# Open-Source_Control_V2_R3.net
KiCad netlist of a schematic drawn in EAGLE
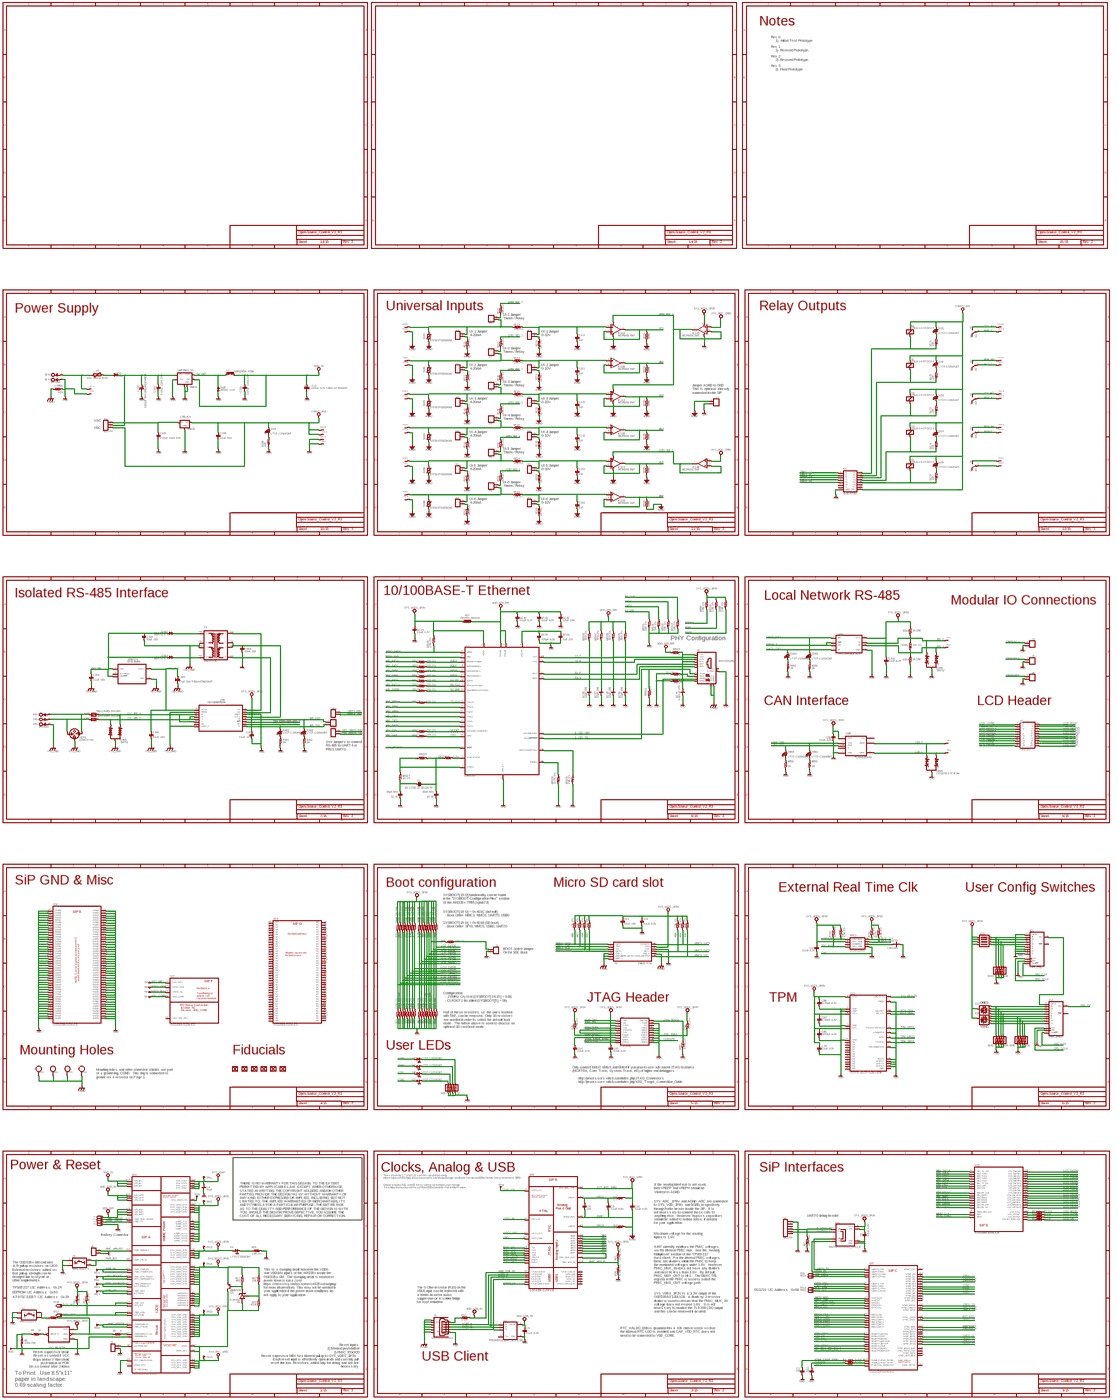
[diagram p0: schematic, sheet 1, overview]
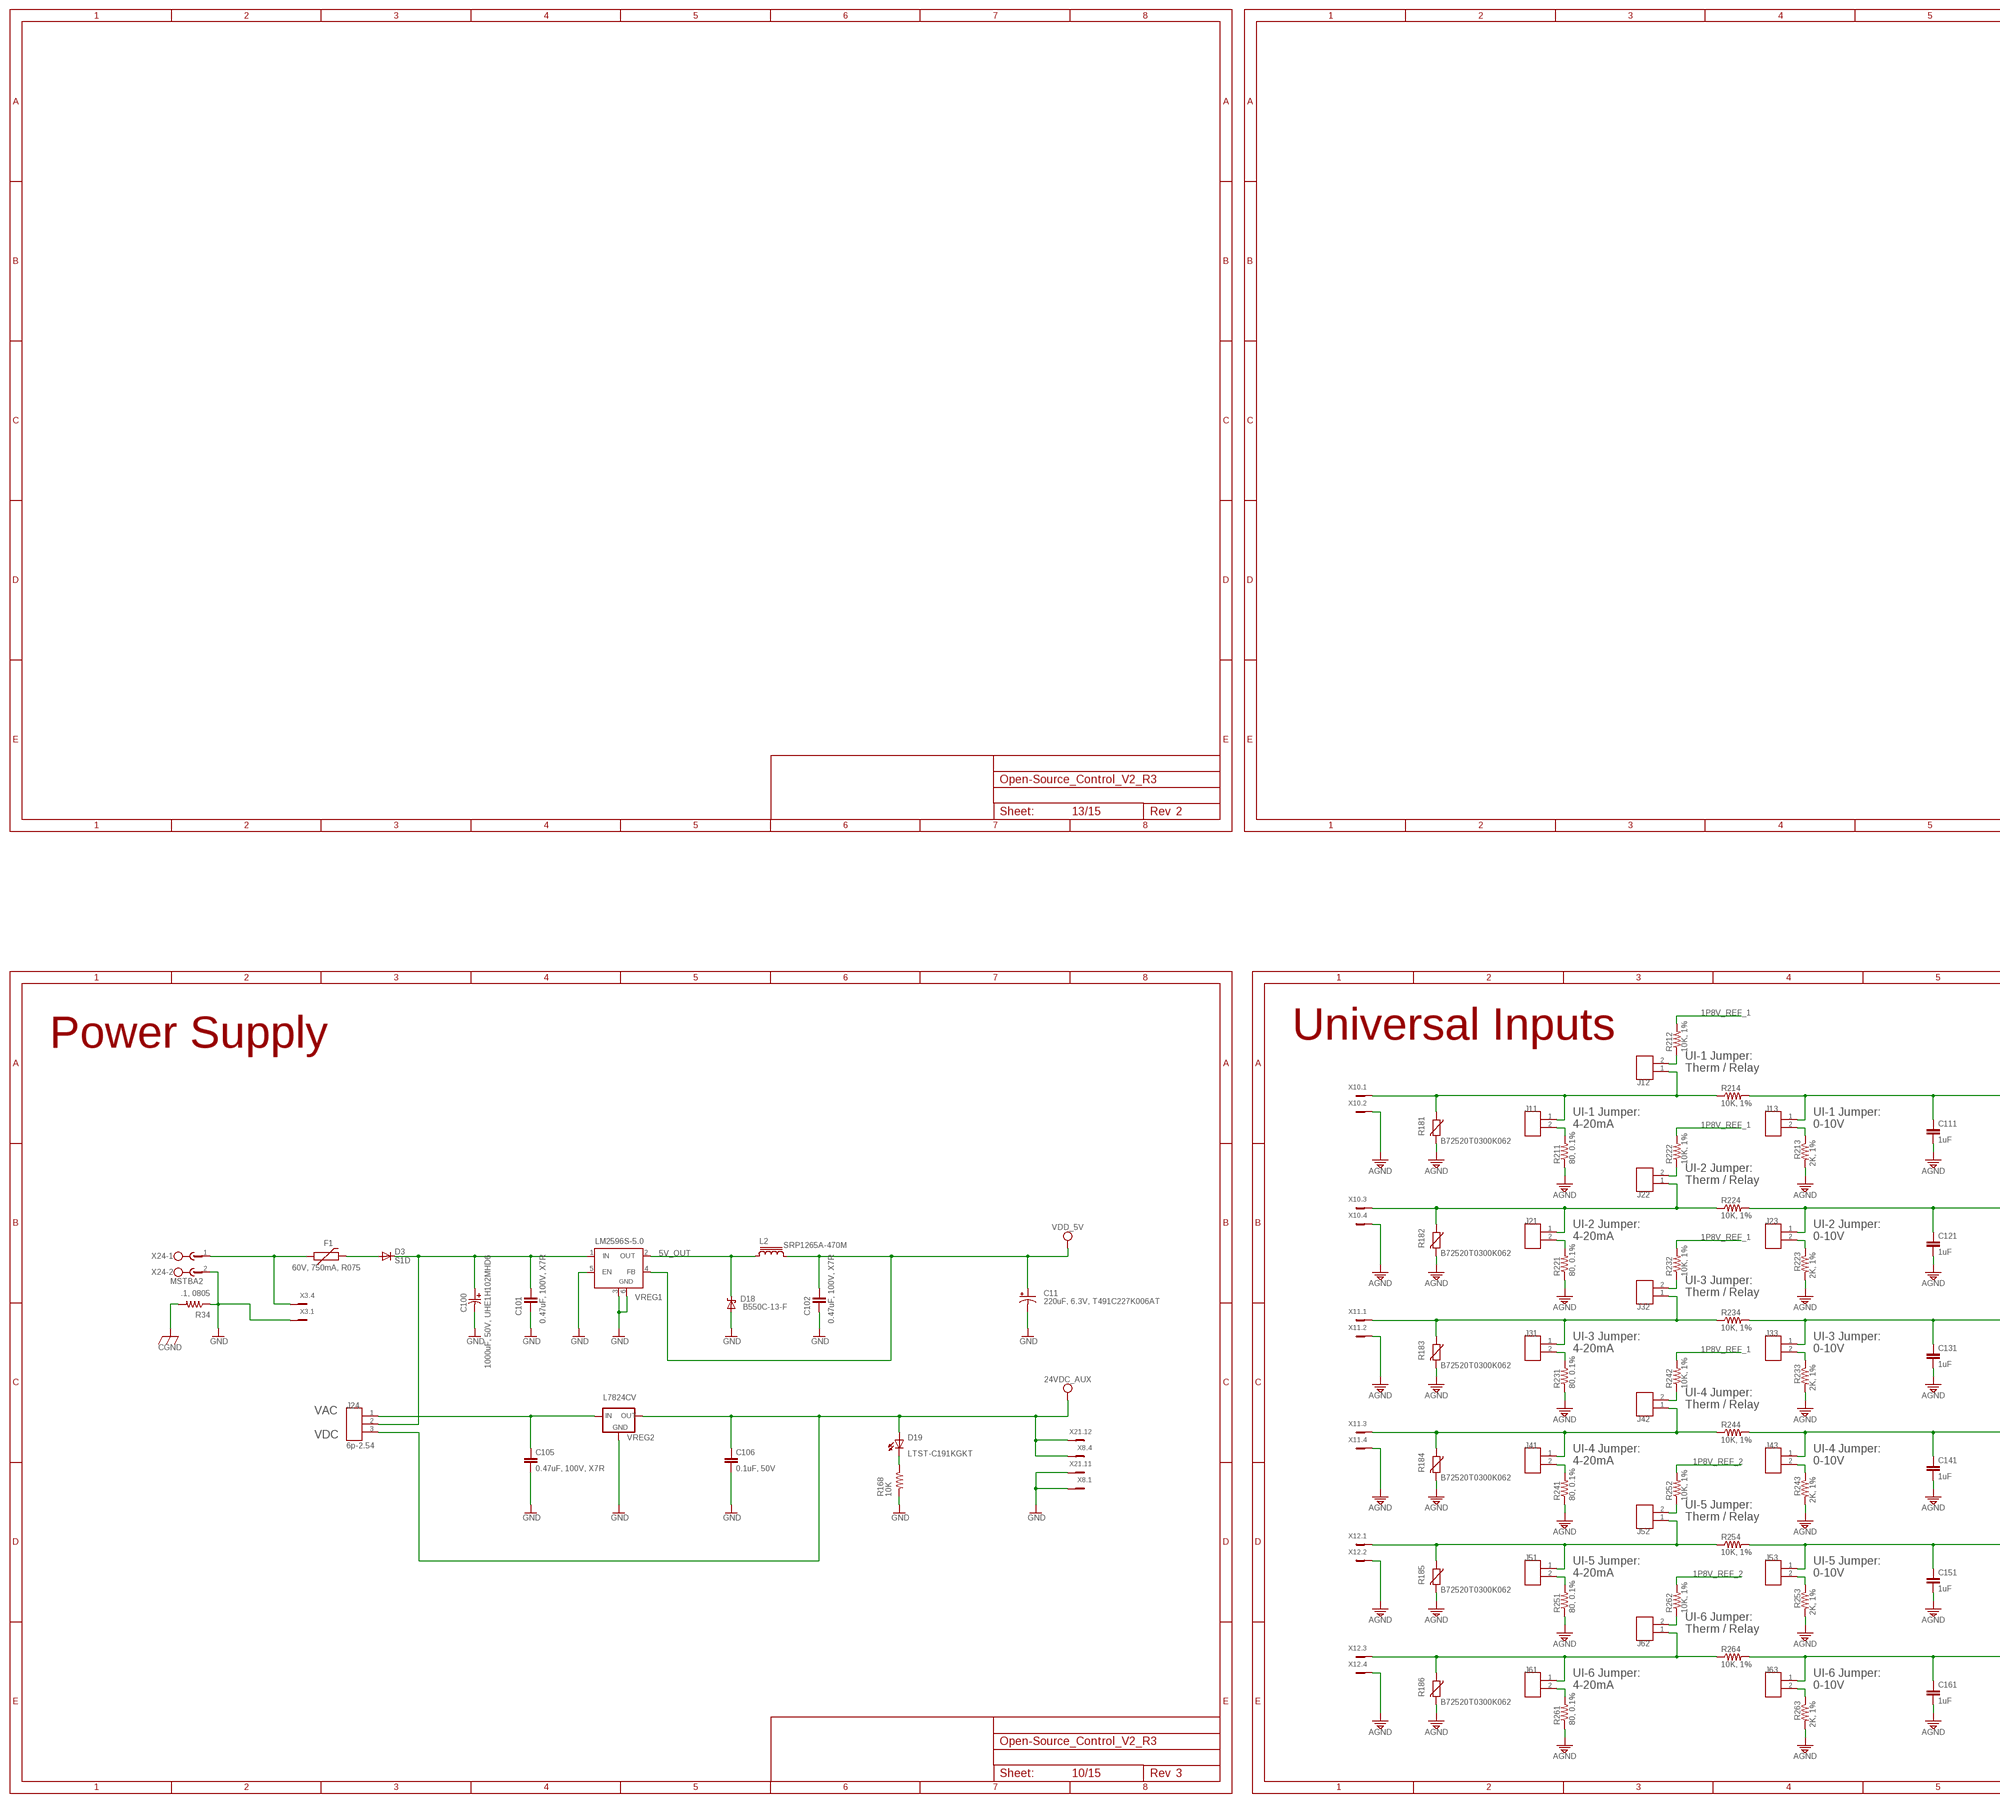
[diagram p1: schematic, sheet 1, part 1 of 6]
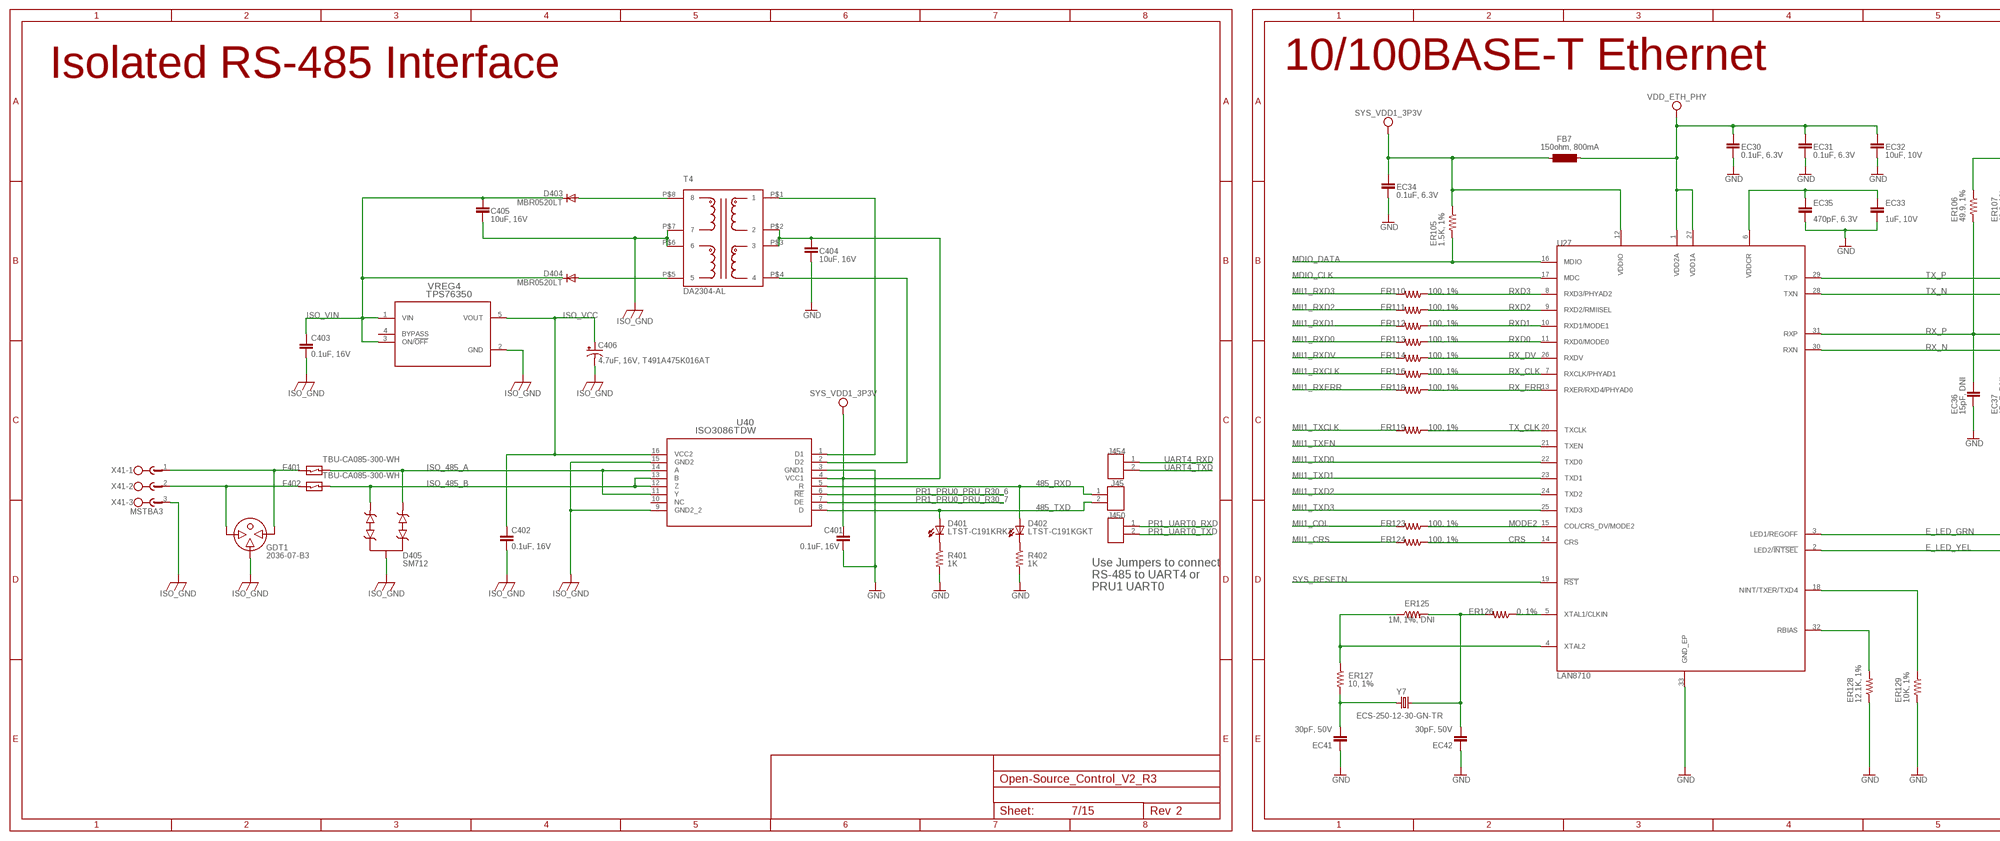
[diagram p2: schematic, sheet 1, part 2 of 6]
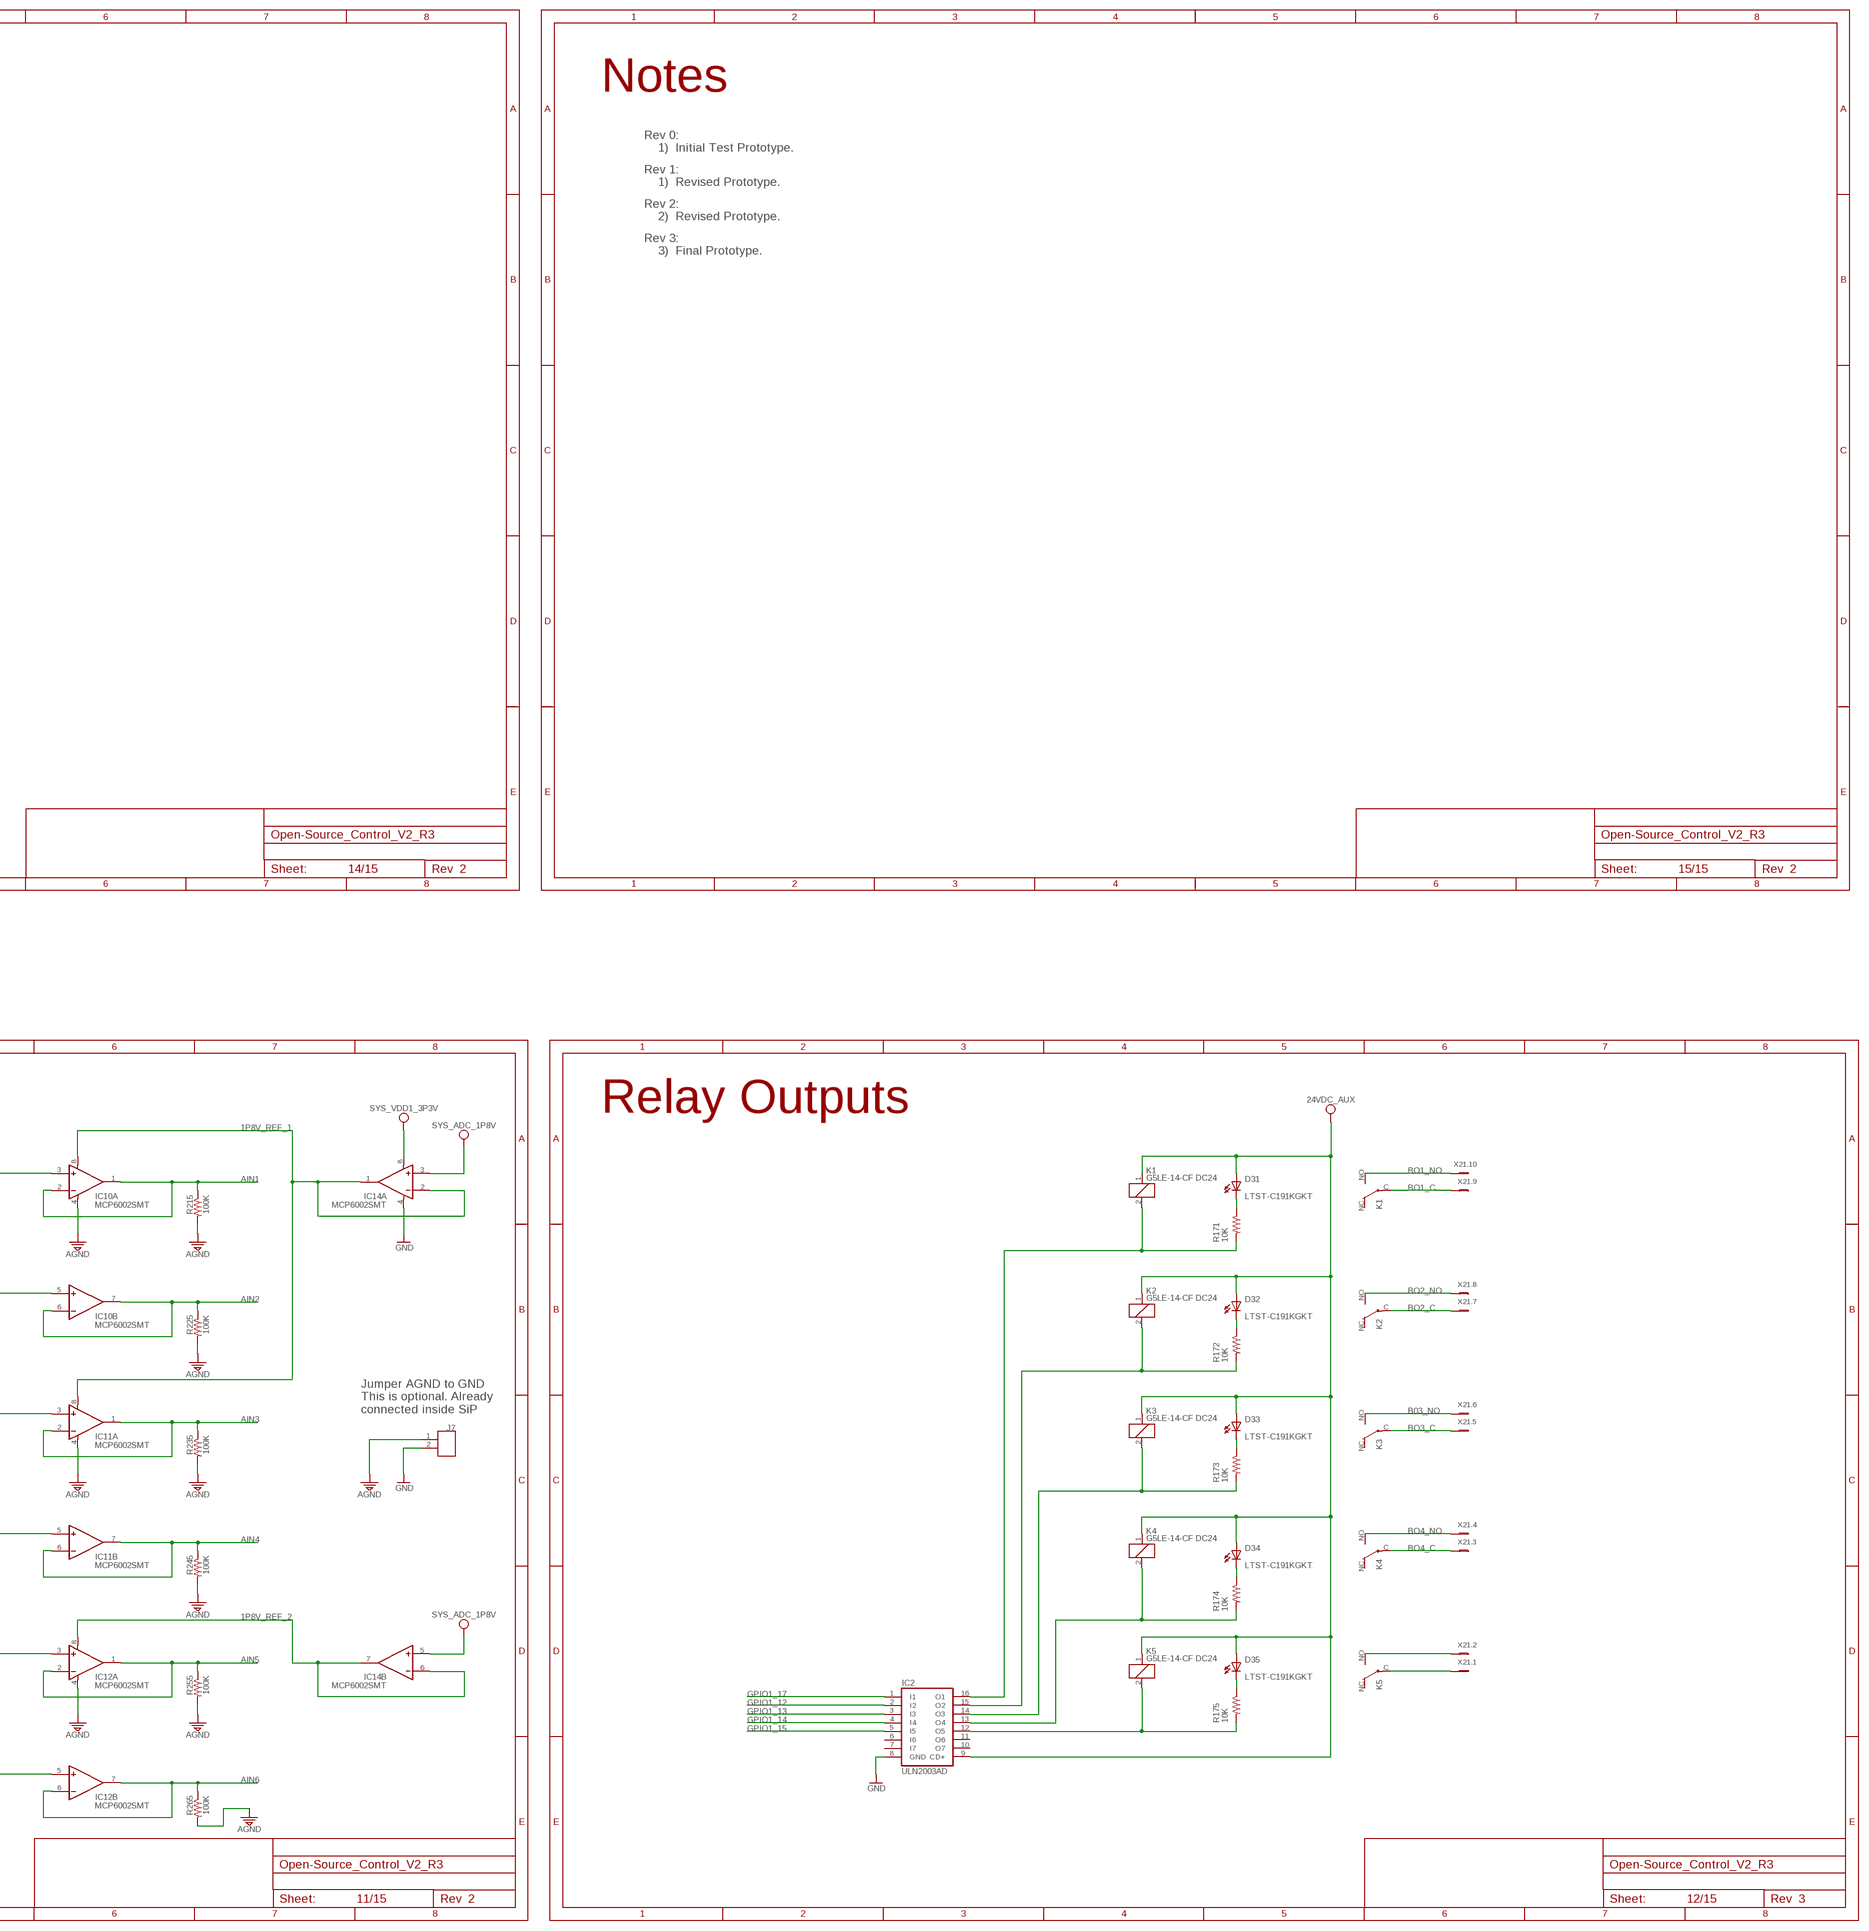
[diagram p3: schematic, sheet 1, part 3 of 6]
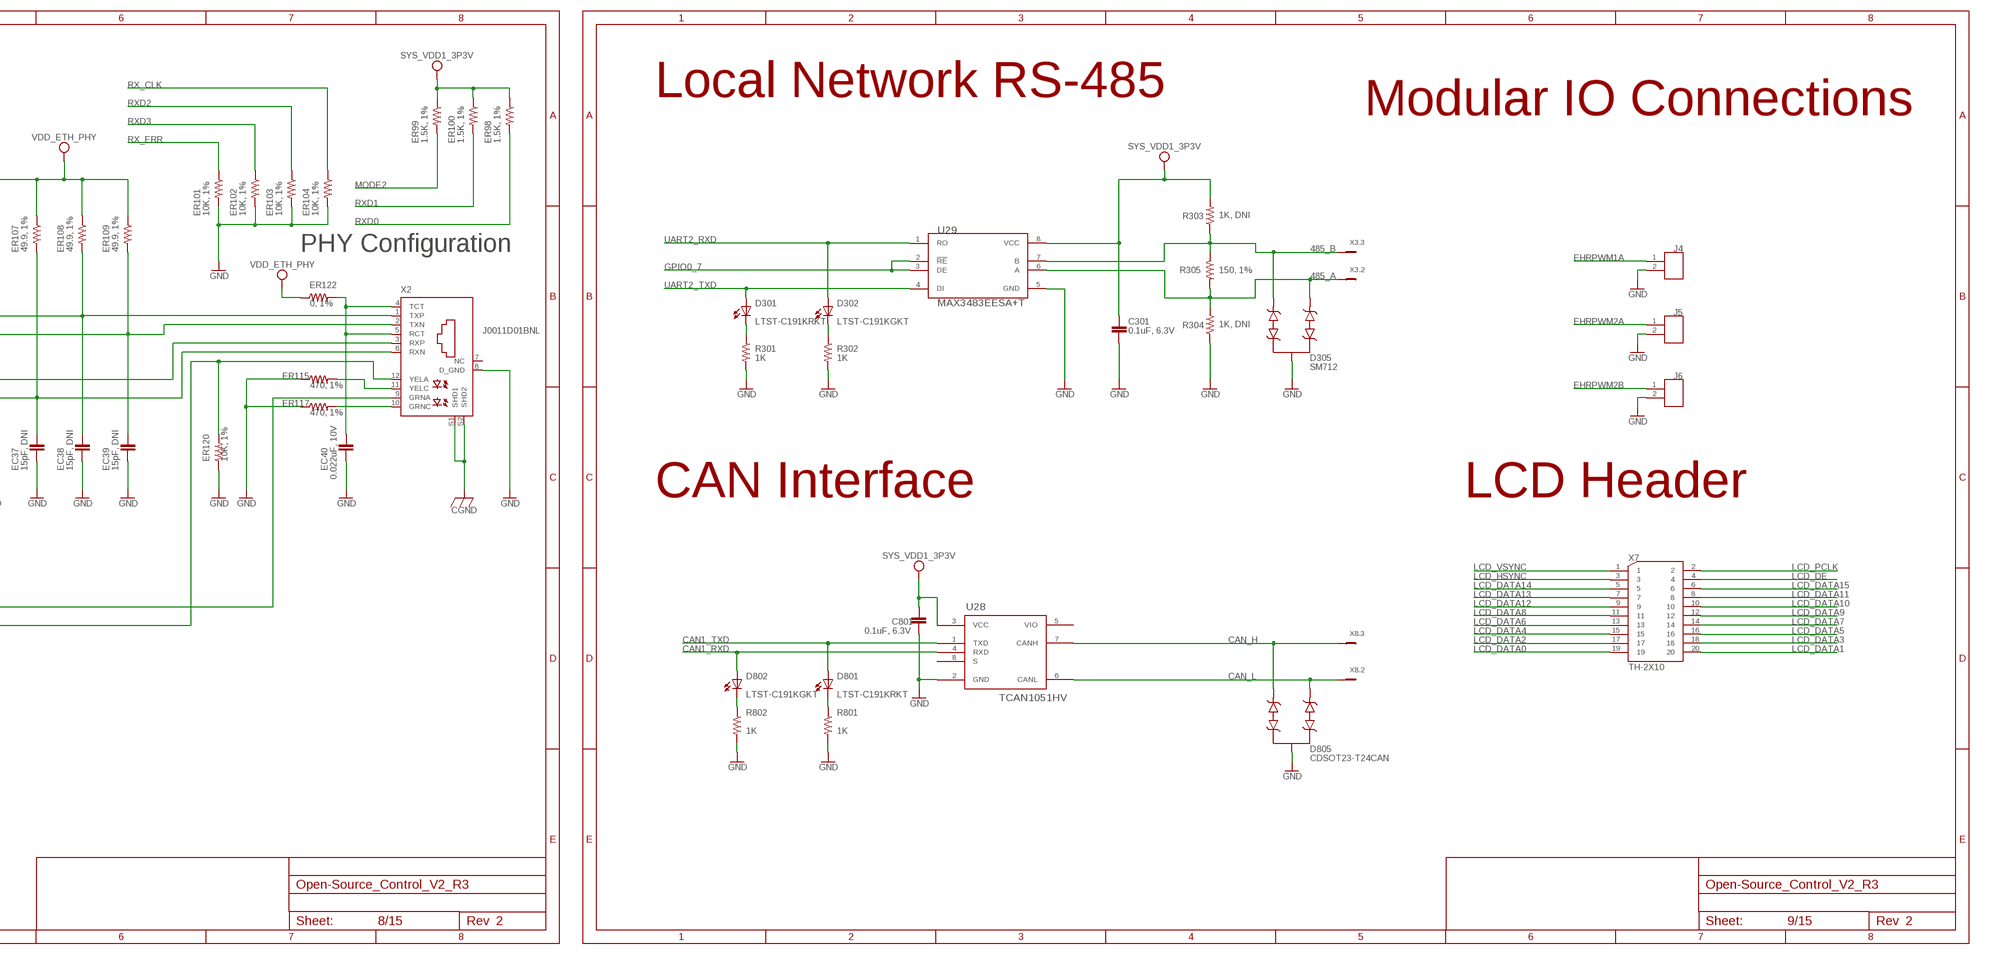
[diagram p4: schematic, sheet 1, part 4 of 6]
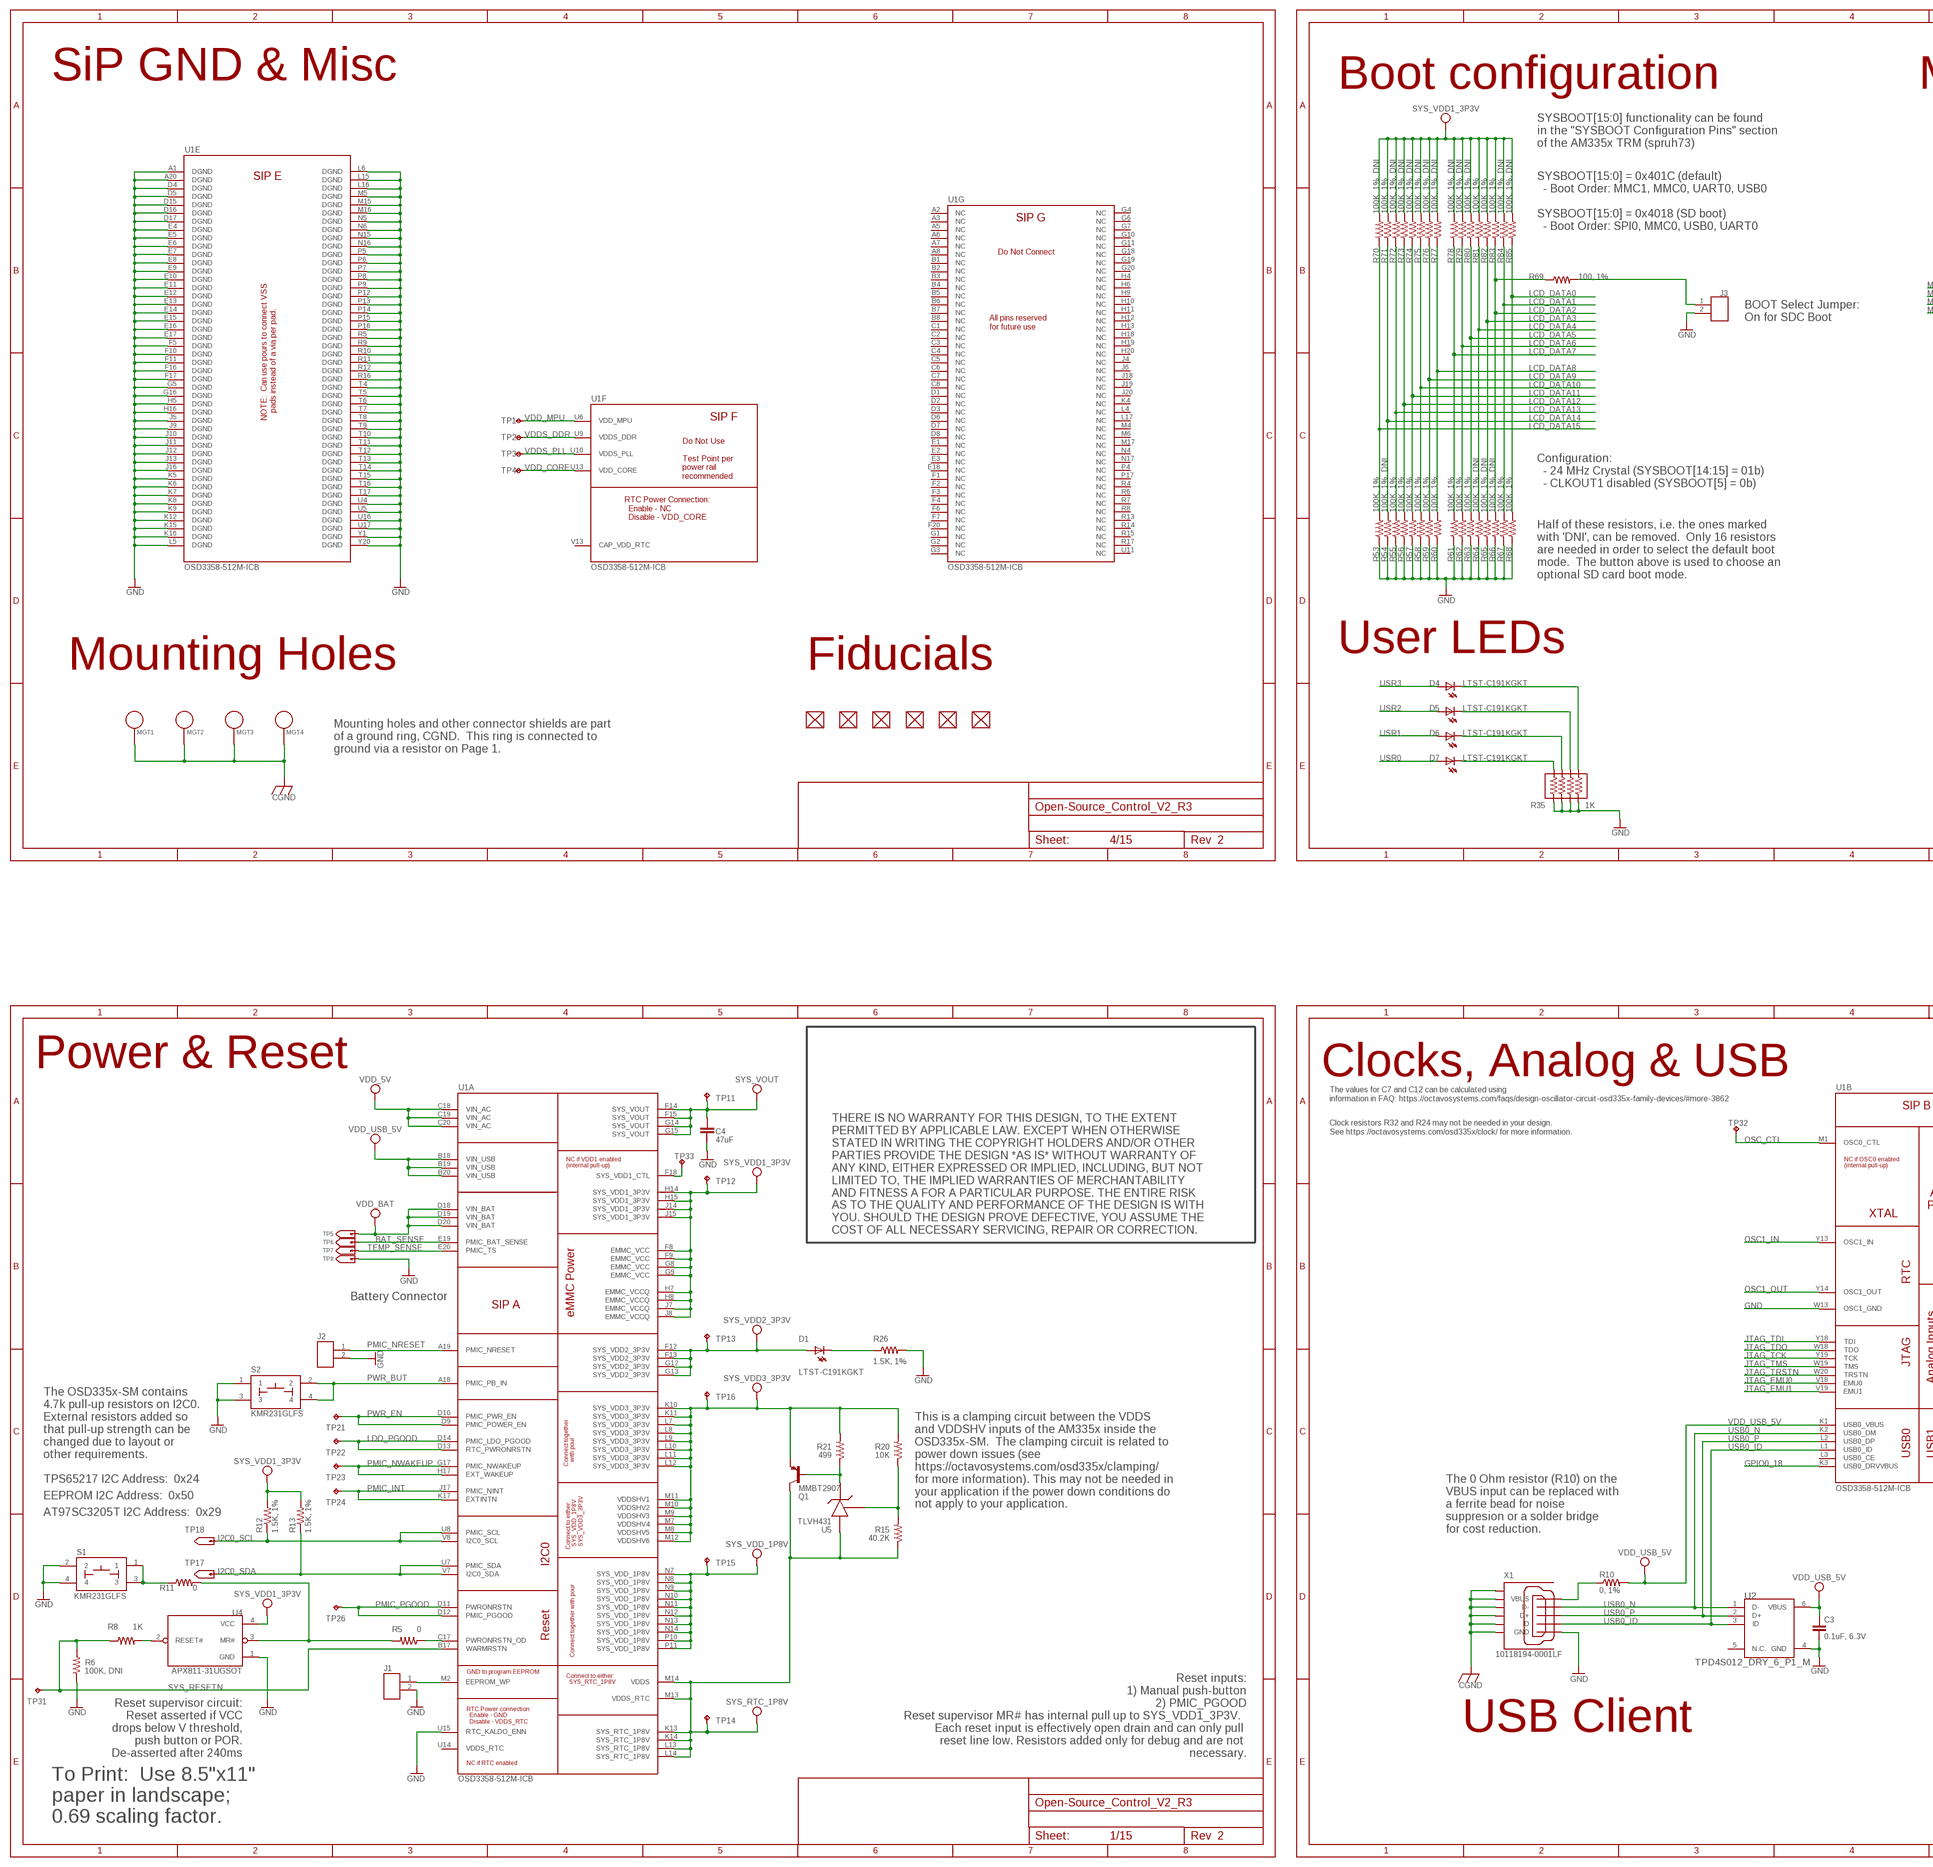
[diagram p5: schematic, sheet 1, part 5 of 6]
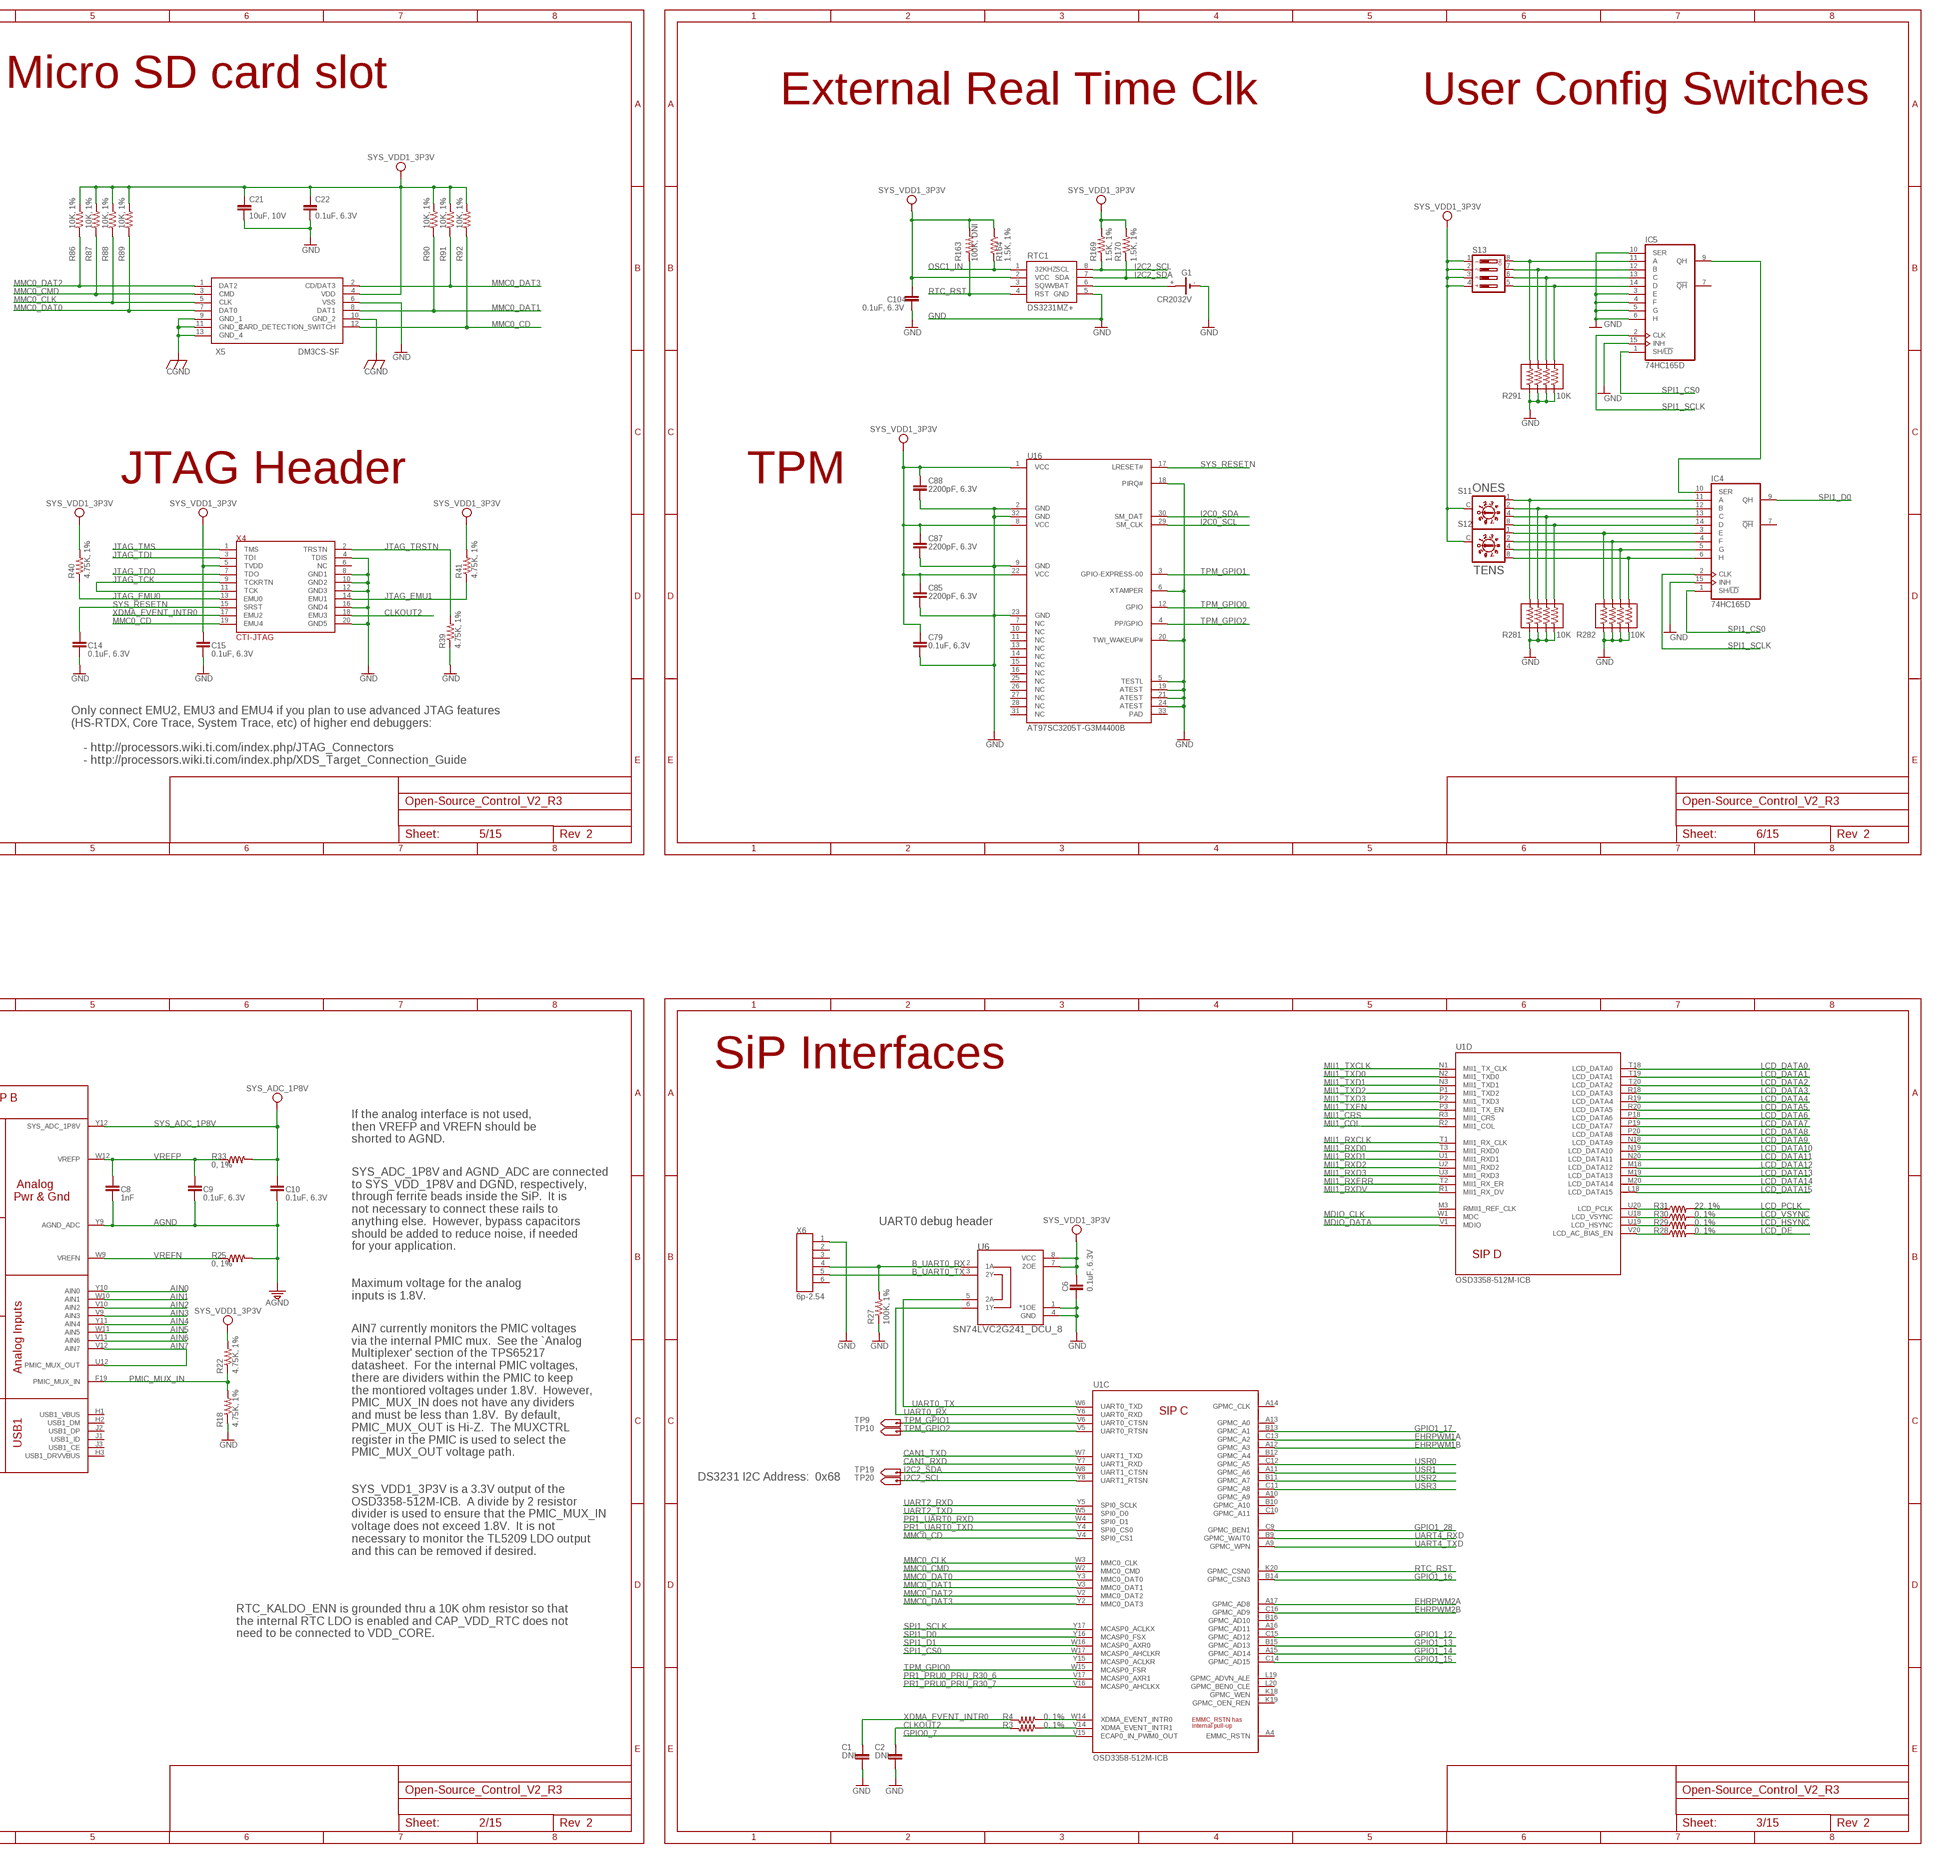
[diagram p6: schematic, sheet 1, part 6 of 6]

(export (version "E")
  (design (tool "Eeschema 10.0.6"))
  (components
    (comp (ref "C1")
      (value "DNI")
      (footprint "eagle-import:C0603")
      (libsource (lib "eagle-import") (part "CC0603"))
    )
    (comp (ref "C2")
      (value "DNI")
      (footprint "eagle-import:C0603")
      (libsource (lib "eagle-import") (part "CC0603"))
    )
    (comp (ref "C3")
      (value "0.1uF, 6.3V")
      (footprint "eagle-import:C0402")
      (libsource (lib "eagle-import") (part "CC0402"))
    )
    (comp (ref "C4")
      (value "47uF")
      (footprint "eagle-import:C0805")
      (libsource (lib "eagle-import") (part "CC0805"))
    )
    (comp (ref "C6")
      (value "0.1uF, 6.3V")
      (footprint "eagle-import:C0402")
      (libsource (lib "eagle-import") (part "CC0402"))
    )
    (comp (ref "C8")
      (value "1nF")
      (footprint "eagle-import:C0402")
      (libsource (lib "eagle-import") (part "CC0402"))
    )
    (comp (ref "C9")
      (value "0.1uF, 6.3V")
      (footprint "eagle-import:C0402")
      (libsource (lib "eagle-import") (part "CC0402"))
    )
    (comp (ref "C10")
      (value "0.1uF, 6.3V")
      (footprint "eagle-import:C0402")
      (libsource (lib "eagle-import") (part "CC0402"))
    )
    (comp (ref "C11")
      (value "220uF, 6.3V, T491C227K006AT")
      (footprint "eagle-import:C_6032-28R")
      (libsource (lib "eagle-import") (part "CPOL-USC/6032-28R"))
    )
    (comp (ref "C14")
      (value "0.1uF, 6.3V")
      (footprint "eagle-import:C0402")
      (libsource (lib "eagle-import") (part "CC0402"))
    )
    (comp (ref "C15")
      (value "0.1uF, 6.3V")
      (footprint "eagle-import:C0402")
      (libsource (lib "eagle-import") (part "CC0402"))
    )
    (comp (ref "C21")
      (value "10uF, 10V")
      (footprint "eagle-import:C0805")
      (libsource (lib "eagle-import") (part "CC0805"))
    )
    (comp (ref "C22")
      (value "0.1uF, 6.3V")
      (footprint "eagle-import:C0402")
      (libsource (lib "eagle-import") (part "CC0402"))
    )
    (comp (ref "C79")
      (value "0.1uF, 6.3V")
      (footprint "eagle-import:C0402")
      (libsource (lib "eagle-import") (part "CC0402"))
    )
    (comp (ref "C85")
      (value "2200pF, 6.3V")
      (footprint "eagle-import:C0402")
      (libsource (lib "eagle-import") (part "CC0402"))
    )
    (comp (ref "C87")
      (value "2200pF, 6.3V")
      (footprint "eagle-import:C0402")
      (libsource (lib "eagle-import") (part "CC0402"))
    )
    (comp (ref "C88")
      (value "2200pF, 6.3V")
      (footprint "eagle-import:C0402")
      (libsource (lib "eagle-import") (part "CC0402"))
    )
    (comp (ref "C100")
      (value "1000uF, 50V, UHE1H102MHD6")
      (footprint "eagle-import:PCAP_16X25-THRU-ELECT")
      (fields (field (name "MANUFACTURER_PART_NUMBER") "UHE1H102MHD6"))
      (libsource (lib "eagle-import") (part "UHE1H102MHD6"))
    )
    (comp (ref "C101")
      (value "0.47uF, 100V, X7R")
      (footprint "eagle-import:1206")
      (libsource (lib "eagle-import") (part "4.7UF-1206-16V-(+80/-20%)"))
    )
    (comp (ref "C102")
      (value "0.47uF, 100V, X7R")
      (footprint "eagle-import:1206")
      (libsource (lib "eagle-import") (part "4.7UF-1206-16V-(+80/-20%)"))
    )
    (comp (ref "C104")
      (value "0.1uF, 6.3V")
      (footprint "eagle-import:C0402")
      (libsource (lib "eagle-import") (part "CC0402"))
    )
    (comp (ref "C105")
      (value "0.47uF, 100V, X7R")
      (footprint "eagle-import:1206")
      (libsource (lib "eagle-import") (part "4.7UF-1206-16V-(+80/-20%)"))
    )
    (comp (ref "C106")
      (value "0.1uF, 50V")
      (footprint "eagle-import:1206")
      (libsource (lib "eagle-import") (part "4.7UF-1206-16V-(+80/-20%)"))
    )
    (comp (ref "C111")
      (value "1uF")
      (footprint "eagle-import:C0805")
      (libsource (lib "eagle-import") (part "CC0805"))
    )
    (comp (ref "C121")
      (value "1uF")
      (footprint "eagle-import:C0805")
      (libsource (lib "eagle-import") (part "CC0805"))
    )
    (comp (ref "C131")
      (value "1uF")
      (footprint "eagle-import:C0805")
      (libsource (lib "eagle-import") (part "CC0805"))
    )
    (comp (ref "C141")
      (value "1uF")
      (footprint "eagle-import:C0805")
      (libsource (lib "eagle-import") (part "CC0805"))
    )
    (comp (ref "C151")
      (value "1uF")
      (footprint "eagle-import:C0805")
      (libsource (lib "eagle-import") (part "CC0805"))
    )
    (comp (ref "C161")
      (value "1uF")
      (footprint "eagle-import:C0805")
      (libsource (lib "eagle-import") (part "CC0805"))
    )
    (comp (ref "C301")
      (value "0.1uF, 6.3V")
      (footprint "eagle-import:C0402")
      (libsource (lib "eagle-import") (part "CC0402"))
    )
    (comp (ref "C401")
      (value "0.1uF, 16V")
      (footprint "eagle-import:C0402")
      (libsource (lib "eagle-import") (part "CC0402"))
    )
    (comp (ref "C402")
      (value "0.1uF, 16V")
      (footprint "eagle-import:C0402")
      (libsource (lib "eagle-import") (part "CC0402"))
    )
    (comp (ref "C403")
      (value "0.1uF, 16V")
      (footprint "eagle-import:C0402")
      (libsource (lib "eagle-import") (part "CC0402"))
    )
    (comp (ref "C404")
      (value "10uF, 16V")
      (footprint "eagle-import:C0805")
      (libsource (lib "eagle-import") (part "CC0805"))
    )
    (comp (ref "C405")
      (value "10uF, 16V")
      (footprint "eagle-import:C0805")
      (libsource (lib "eagle-import") (part "CC0805"))
    )
    (comp (ref "C406")
      (value "4.7uF, 16V, T491A475K016AT")
      (footprint "eagle-import:A_3216-18R")
      (libsource (lib "eagle-import") (part "CPOL-USA/3216-18R"))
    )
    (comp (ref "C801")
      (value "0.1uF, 6.3V")
      (footprint "eagle-import:C0402")
      (libsource (lib "eagle-import") (part "CC0402"))
    )
    (comp (ref "D1")
      (value "LTST-C191KGKT")
      (footprint "eagle-import:EIA-STD")
      (libsource (lib "eagle-import") (part "Open-Source_Control_V2_R2_LTST-C191KGKTLED_EIA-STD"))
    )
    (comp (ref "D3")
      (value "S1D")
      (footprint "eagle-import:SMA")
      (libsource (lib "eagle-import") (part "S1M"))
    )
    (comp (ref "D4")
      (value "LTST-C191KGKT")
      (footprint "eagle-import:EIA-STD")
      (libsource (lib "eagle-import") (part "LTST-C191KGKTLED_EIA-STD"))
    )
    (comp (ref "D5")
      (value "LTST-C191KGKT")
      (footprint "eagle-import:EIA-STD")
      (libsource (lib "eagle-import") (part "LTST-C191KGKTLED_EIA-STD"))
    )
    (comp (ref "D6")
      (value "LTST-C191KGKT")
      (footprint "eagle-import:EIA-STD")
      (libsource (lib "eagle-import") (part "LTST-C191KGKTLED_EIA-STD"))
    )
    (comp (ref "D7")
      (value "LTST-C191KGKT")
      (footprint "eagle-import:EIA-STD")
      (libsource (lib "eagle-import") (part "LTST-C191KGKTLED_EIA-STD"))
    )
    (comp (ref "D18")
      (value "B550C-13-F")
      (footprint "eagle-import:SMC")
      (libsource (lib "eagle-import") (part "B520C-13-F"))
    )
    (comp (ref "D19")
      (value "LTST-C191KGKT")
      (footprint "eagle-import:EIA-STD")
      (libsource (lib "eagle-import") (part "Open-Source_Control_V2_R2_LTST-C191KGKTLED_EIA-STD"))
    )
    (comp (ref "D31")
      (value "LTST-C191KGKT")
      (footprint "eagle-import:EIA-STD")
      (libsource (lib "eagle-import") (part "LTST-C191KGKTLED_EIA-STD"))
    )
    (comp (ref "D32")
      (value "LTST-C191KGKT")
      (footprint "eagle-import:EIA-STD")
      (libsource (lib "eagle-import") (part "LTST-C191KGKTLED_EIA-STD"))
    )
    (comp (ref "D33")
      (value "LTST-C191KGKT")
      (footprint "eagle-import:EIA-STD")
      (libsource (lib "eagle-import") (part "LTST-C191KGKTLED_EIA-STD"))
    )
    (comp (ref "D34")
      (value "LTST-C191KGKT")
      (footprint "eagle-import:EIA-STD")
      (libsource (lib "eagle-import") (part "LTST-C191KGKTLED_EIA-STD"))
    )
    (comp (ref "D35")
      (value "LTST-C191KGKT")
      (footprint "eagle-import:EIA-STD")
      (libsource (lib "eagle-import") (part "LTST-C191KGKTLED_EIA-STD"))
    )
    (comp (ref "D301")
      (value "LTST-C191KRKT")
      (footprint "eagle-import:EIA-STD")
      (libsource (lib "eagle-import") (part "LTST-C191KGKTLED_EIA-STD"))
    )
    (comp (ref "D302")
      (value "LTST-C191KGKT")
      (footprint "eagle-import:EIA-STD")
      (libsource (lib "eagle-import") (part "LTST-C191KRKTLED_EIA-STD"))
    )
    (comp (ref "D305")
      (value "SM712")
      (footprint "eagle-import:SOT23-3")
      (libsource (lib "eagle-import") (part "SM712"))
    )
    (comp (ref "D401")
      (value "LTST-C191KRKT")
      (footprint "eagle-import:EIA-STD")
      (libsource (lib "eagle-import") (part "LTST-C191KRKTLED_EIA-STD"))
    )
    (comp (ref "D402")
      (value "LTST-C191KGKT")
      (footprint "eagle-import:EIA-STD")
      (libsource (lib "eagle-import") (part "LTST-C191KGKTLED_EIA-STD"))
    )
    (comp (ref "D403")
      (value "MBR0520LT")
      (footprint "eagle-import:SOD123")
      (libsource (lib "eagle-import") (part "MBR0520LT"))
    )
    (comp (ref "D404")
      (value "MBR0520LT")
      (footprint "eagle-import:SOD123")
      (libsource (lib "eagle-import") (part "MBR0520LT"))
    )
    (comp (ref "D405")
      (value "SM712")
      (footprint "eagle-import:SOT23-3")
      (libsource (lib "eagle-import") (part "SM712"))
    )
    (comp (ref "D801")
      (value "LTST-C191KRKT")
      (footprint "eagle-import:EIA-STD")
      (libsource (lib "eagle-import") (part "LTST-C191KRKTLED_EIA-STD"))
    )
    (comp (ref "D802")
      (value "LTST-C191KGKT")
      (footprint "eagle-import:EIA-STD")
      (libsource (lib "eagle-import") (part "LTST-C191KGKTLED_EIA-STD"))
    )
    (comp (ref "D805")
      (value "CDSOT23-T24CAN")
      (footprint "eagle-import:SOT23-3")
      (libsource (lib "eagle-import") (part "CDSOT23-T24CAN"))
    )
    (comp (ref "EC30")
      (value "0.1uF, 6.3V")
      (footprint "eagle-import:C0402")
      (libsource (lib "eagle-import") (part "CC0402"))
    )
    (comp (ref "EC31")
      (value "0.1uF, 6.3V")
      (footprint "eagle-import:C0402")
      (libsource (lib "eagle-import") (part "CC0402"))
    )
    (comp (ref "EC32")
      (value "10uF, 10V")
      (footprint "eagle-import:C0805")
      (libsource (lib "eagle-import") (part "CC0805"))
    )
    (comp (ref "EC33")
      (value "1uF, 10V")
      (footprint "eagle-import:C0402")
      (libsource (lib "eagle-import") (part "CC0402"))
    )
    (comp (ref "EC34")
      (value "0.1uF, 6.3V")
      (footprint "eagle-import:C0402")
      (libsource (lib "eagle-import") (part "CC0402"))
    )
    (comp (ref "EC35")
      (value "470pF, 6.3V")
      (footprint "eagle-import:C0402")
      (libsource (lib "eagle-import") (part "CC0402"))
    )
    (comp (ref "EC36")
      (value "15pF, DNI")
      (footprint "eagle-import:C0402")
      (libsource (lib "eagle-import") (part "CC0402"))
    )
    (comp (ref "EC37")
      (value "15pF, DNI")
      (footprint "eagle-import:C0402")
      (libsource (lib "eagle-import") (part "CC0402"))
    )
    (comp (ref "EC38")
      (value "15pF, DNI")
      (footprint "eagle-import:C0402")
      (libsource (lib "eagle-import") (part "CC0402"))
    )
    (comp (ref "EC39")
      (value "15pF, DNI")
      (footprint "eagle-import:C0402")
      (libsource (lib "eagle-import") (part "CC0402"))
    )
    (comp (ref "EC40")
      (value "0.022uF, 10V")
      (footprint "eagle-import:C0402")
      (libsource (lib "eagle-import") (part "CC0402"))
    )
    (comp (ref "EC41")
      (value "30pF, 50V")
      (footprint "eagle-import:C0402")
      (libsource (lib "eagle-import") (part "CC0402"))
    )
    (comp (ref "EC42")
      (value "30pF, 50V")
      (footprint "eagle-import:C0402")
      (libsource (lib "eagle-import") (part "CC0402"))
    )
    (comp (ref "ER98")
      (value "1.5K, 1%")
      (footprint "eagle-import:R0402")
      (libsource (lib "eagle-import") (part "OSD3358-SM-RED Platform_R-US_R0402"))
    )
    (comp (ref "ER99")
      (value "1.5K, 1%")
      (footprint "eagle-import:R0402")
      (libsource (lib "eagle-import") (part "OSD3358-SM-RED Platform_R-US_R0402"))
    )
    (comp (ref "ER100")
      (value "1.5K, 1%")
      (footprint "eagle-import:R0402")
      (libsource (lib "eagle-import") (part "OSD3358-SM-RED Platform_R-US_R0402"))
    )
    (comp (ref "ER101")
      (value "10K, 1%")
      (footprint "eagle-import:R0402")
      (libsource (lib "eagle-import") (part "OSD3358-SM-RED Platform_R-US_R0402"))
    )
    (comp (ref "ER102")
      (value "10K, 1%")
      (footprint "eagle-import:R0402")
      (libsource (lib "eagle-import") (part "OSD3358-SM-RED Platform_R-US_R0402"))
    )
    (comp (ref "ER103")
      (value "10K, 1%")
      (footprint "eagle-import:R0402")
      (libsource (lib "eagle-import") (part "OSD3358-SM-RED Platform_R-US_R0402"))
    )
    (comp (ref "ER104")
      (value "10K, 1%")
      (footprint "eagle-import:R0402")
      (libsource (lib "eagle-import") (part "OSD3358-SM-RED Platform_R-US_R0402"))
    )
    (comp (ref "ER105")
      (value "1.5K, 1%")
      (footprint "eagle-import:R0402")
      (libsource (lib "eagle-import") (part "OSD3358-SM-RED Platform_R-US_R0402"))
    )
    (comp (ref "ER106")
      (value "49.9, 1%")
      (footprint "eagle-import:R0402")
      (libsource (lib "eagle-import") (part "OSD3358-SM-RED Platform_R-US_R0402"))
    )
    (comp (ref "ER107")
      (value "49.9, 1%")
      (footprint "eagle-import:R0402")
      (libsource (lib "eagle-import") (part "OSD3358-SM-RED Platform_R-US_R0402"))
    )
    (comp (ref "ER108")
      (value "49.9, 1%")
      (footprint "eagle-import:R0402")
      (libsource (lib "eagle-import") (part "OSD3358-SM-RED Platform_R-US_R0402"))
    )
    (comp (ref "ER109")
      (value "49.9, 1%")
      (footprint "eagle-import:R0402")
      (libsource (lib "eagle-import") (part "OSD3358-SM-RED Platform_R-US_R0402"))
    )
    (comp (ref "ER110")
      (value "100, 1%")
      (footprint "eagle-import:R0402")
      (libsource (lib "eagle-import") (part "OSD3358-SM-RED Platform_R-US_R0402"))
    )
    (comp (ref "ER111")
      (value "100, 1%")
      (footprint "eagle-import:R0402")
      (libsource (lib "eagle-import") (part "OSD3358-SM-RED Platform_R-US_R0402"))
    )
    (comp (ref "ER112")
      (value "100, 1%")
      (footprint "eagle-import:R0402")
      (libsource (lib "eagle-import") (part "OSD3358-SM-RED Platform_R-US_R0402"))
    )
    (comp (ref "ER113")
      (value "100, 1%")
      (footprint "eagle-import:R0402")
      (libsource (lib "eagle-import") (part "OSD3358-SM-RED Platform_R-US_R0402"))
    )
    (comp (ref "ER114")
      (value "100, 1%")
      (footprint "eagle-import:R0402")
      (libsource (lib "eagle-import") (part "OSD3358-SM-RED Platform_R-US_R0402"))
    )
    (comp (ref "ER115")
      (value "470, 1%")
      (footprint "eagle-import:R0402")
      (libsource (lib "eagle-import") (part "OSD3358-SM-RED Platform_R-US_R0402"))
    )
    (comp (ref "ER116")
      (value "100, 1%")
      (footprint "eagle-import:R0402")
      (libsource (lib "eagle-import") (part "OSD3358-SM-RED Platform_R-US_R0402"))
    )
    (comp (ref "ER117")
      (value "470, 1%")
      (footprint "eagle-import:R0402")
      (libsource (lib "eagle-import") (part "OSD3358-SM-RED Platform_R-US_R0402"))
    )
    (comp (ref "ER118")
      (value "100, 1%")
      (footprint "eagle-import:R0402")
      (libsource (lib "eagle-import") (part "OSD3358-SM-RED Platform_R-US_R0402"))
    )
    (comp (ref "ER119")
      (value "100, 1%")
      (footprint "eagle-import:R0402")
      (libsource (lib "eagle-import") (part "OSD3358-SM-RED Platform_R-US_R0402"))
    )
    (comp (ref "ER120")
      (value "10K, 1%")
      (footprint "eagle-import:R0402")
      (libsource (lib "eagle-import") (part "OSD3358-SM-RED Platform_R-US_R0402"))
    )
    (comp (ref "ER122")
      (value "0, 1%")
      (footprint "eagle-import:R0402")
      (libsource (lib "eagle-import") (part "OSD3358-SM-RED Platform_R-US_R0402"))
    )
    (comp (ref "ER123")
      (value "100, 1%")
      (footprint "eagle-import:R0402")
      (libsource (lib "eagle-import") (part "OSD3358-SM-RED Platform_R-US_R0402"))
    )
    (comp (ref "ER124")
      (value "100, 1%")
      (footprint "eagle-import:R0402")
      (libsource (lib "eagle-import") (part "OSD3358-SM-RED Platform_R-US_R0402"))
    )
    (comp (ref "ER125")
      (value "1M, 1%, DNI")
      (footprint "eagle-import:R0402")
      (libsource (lib "eagle-import") (part "OSD3358-SM-RED Platform_R-US_R0402"))
    )
    (comp (ref "ER126")
      (value "0, 1%")
      (footprint "eagle-import:R0402")
      (libsource (lib "eagle-import") (part "OSD3358-SM-RED Platform_R-US_R0402"))
    )
    (comp (ref "ER127")
      (value "10, 1%")
      (footprint "eagle-import:R0402")
      (libsource (lib "eagle-import") (part "OSD3358-SM-RED Platform_R-US_R0402"))
    )
    (comp (ref "ER128")
      (value "12.1K, 1%")
      (footprint "eagle-import:R0402")
      (libsource (lib "eagle-import") (part "OSD3358-SM-RED Platform_R-US_R0402"))
    )
    (comp (ref "ER129")
      (value "10K, 1%")
      (footprint "eagle-import:R0402")
      (libsource (lib "eagle-import") (part "OSD3358-SM-RED Platform_R-US_R0402"))
    )
    (comp (ref "F1")
      (value "60V, 750mA, R075")
      (footprint "eagle-import:PTH")
      (libsource (lib "eagle-import") (part "PPTC_PTH"))
    )
    (comp (ref "F401")
      (value "TBU-CA085-300-WH")
      (footprint "eagle-import:TBU-CA")
      (libsource (lib "eagle-import") (part "TBU-CA085-300-WH"))
    )
    (comp (ref "F402")
      (value "TBU-CA085-300-WH")
      (footprint "eagle-import:TBU-CA")
      (libsource (lib "eagle-import") (part "TBU-CA085-300-WH"))
    )
    (comp (ref "FB7")
      (value "150ohm, 800mA")
      (footprint "eagle-import:C0805")
      (libsource (lib "eagle-import") (part "BLM21AG151SN1DFB_0805"))
    )
    (comp (ref "FUD1")
      (value "FIDUCIAL")
      (footprint "eagle-import:FIDUCIAL_40MIL")
      (libsource (lib "eagle-import") (part "FIDUCIAL"))
    )
    (comp (ref "FUD2")
      (value "FIDUCIAL")
      (footprint "eagle-import:FIDUCIAL_40MIL")
      (libsource (lib "eagle-import") (part "FIDUCIAL"))
    )
    (comp (ref "FUD3")
      (value "FIDUCIAL")
      (footprint "eagle-import:FIDUCIAL_40MIL")
      (libsource (lib "eagle-import") (part "FIDUCIAL"))
    )
    (comp (ref "FUD4")
      (value "FIDUCIAL")
      (footprint "eagle-import:FIDUCIAL_40MIL")
      (libsource (lib "eagle-import") (part "FIDUCIAL"))
    )
    (comp (ref "FUD5")
      (value "FIDUCIAL")
      (footprint "eagle-import:FIDUCIAL_40MIL")
      (libsource (lib "eagle-import") (part "FIDUCIAL"))
    )
    (comp (ref "FUD6")
      (value "FIDUCIAL")
      (footprint "eagle-import:FIDUCIAL_40MIL")
      (libsource (lib "eagle-import") (part "FIDUCIAL"))
    )
    (comp (ref "G1")
      (value "CR2032V")
      (footprint "eagle-import:CR2032V")
      (libsource (lib "eagle-import") (part "CR2032V"))
    )
    (comp (ref "GDT1")
      (value "2036-07-B3")
      (footprint "eagle-import:2036-XX-B3")
      (libsource (lib "eagle-import") (part "2036-09-B3"))
    )
    (comp (ref "IC2")
      (value "ULN2003AD")
      (footprint "eagle-import:SO16")
      (libsource (lib "eagle-import") (part "ULN2003AD"))
    )
    (comp (ref "IC4")
      (value "74HC165D")
      (footprint "eagle-import:SO16")
      (libsource (lib "eagle-import") (part "74165DHC"))
    )
    (comp (ref "IC5")
      (value "74HC165D")
      (footprint "eagle-import:SO16")
      (libsource (lib "eagle-import") (part "74165DHC"))
    )
    (comp (ref "IC10")
      (value "MCP6002SMT")
      (footprint "eagle-import:SOIC8")
      (libsource (lib "eagle-import") (part "MCP6002SMT"))
    )
    (comp (ref "IC11")
      (value "MCP6002SMT")
      (footprint "eagle-import:SOIC8")
      (libsource (lib "eagle-import") (part "MCP6002SMT"))
    )
    (comp (ref "IC12")
      (value "MCP6002SMT")
      (footprint "eagle-import:SOIC8")
      (libsource (lib "eagle-import") (part "MCP6002SMT"))
    )
    (comp (ref "IC14")
      (value "MCP6002SMT")
      (footprint "eagle-import:SOIC8")
      (libsource (lib "eagle-import") (part "MCP6002SMT"))
    )
    (comp (ref "J1")
      (value "826646-2")
      (footprint "eagle-import:H2-2.54")
      (libsource (lib "eagle-import") (part "826646-2"))
    )
    (comp (ref "J2")
      (value "826646-2")
      (footprint "eagle-import:H2-2.54")
      (libsource (lib "eagle-import") (part "OSD3358-SM-RED Platform_826646-2"))
    )
    (comp (ref "J3")
      (value "826646-2")
      (footprint "eagle-import:H2-2.54")
      (libsource (lib "eagle-import") (part "OSD3358-SM-RED Platform_826646-2"))
    )
    (comp (ref "J4")
      (value "826646-2")
      (footprint "eagle-import:H2-2.54")
      (libsource (lib "eagle-import") (part "OSD3358-SM-RED Platform_826646-2"))
    )
    (comp (ref "J5")
      (value "826646-2")
      (footprint "eagle-import:H2-2.54")
      (libsource (lib "eagle-import") (part "OSD3358-SM-RED Platform_826646-2"))
    )
    (comp (ref "J6")
      (value "826646-2")
      (footprint "eagle-import:H2-2.54")
      (libsource (lib "eagle-import") (part "OSD3358-SM-RED Platform_826646-2"))
    )
    (comp (ref "J7")
      (value "826646-2")
      (footprint "eagle-import:H2-2.54")
      (libsource (lib "eagle-import") (part "OSD3358-SM-RED Platform_826646-2"))
    )
    (comp (ref "J11")
      (value "826646-2")
      (footprint "eagle-import:H2-2.54")
      (libsource (lib "eagle-import") (part "OSD3358-SM-RED Platform_826646-2"))
    )
    (comp (ref "J12")
      (value "826646-2")
      (footprint "eagle-import:H2-2.54")
      (libsource (lib "eagle-import") (part "OSD3358-SM-RED Platform_826646-2"))
    )
    (comp (ref "J13")
      (value "826646-2")
      (footprint "eagle-import:H2-2.54")
      (libsource (lib "eagle-import") (part "OSD3358-SM-RED Platform_826646-2"))
    )
    (comp (ref "J21")
      (value "826646-2")
      (footprint "eagle-import:H2-2.54")
      (libsource (lib "eagle-import") (part "OSD3358-SM-RED Platform_826646-2"))
    )
    (comp (ref "J22")
      (value "826646-2")
      (footprint "eagle-import:H2-2.54")
      (libsource (lib "eagle-import") (part "OSD3358-SM-RED Platform_826646-2"))
    )
    (comp (ref "J23")
      (value "826646-2")
      (footprint "eagle-import:H2-2.54")
      (libsource (lib "eagle-import") (part "OSD3358-SM-RED Platform_826646-2"))
    )
    (comp (ref "J24")
      (value "6p-2.54")
      (footprint "eagle-import:H3-2.54")
      (fields (field (name "MPN") "P125-1106A1BS116A1"))
      (libsource (lib "eagle-import") (part "826646-3"))
    )
    (comp (ref "J31")
      (value "826646-2")
      (footprint "eagle-import:H2-2.54")
      (libsource (lib "eagle-import") (part "OSD3358-SM-RED Platform_826646-2"))
    )
    (comp (ref "J32")
      (value "826646-2")
      (footprint "eagle-import:H2-2.54")
      (libsource (lib "eagle-import") (part "OSD3358-SM-RED Platform_826646-2"))
    )
    (comp (ref "J33")
      (value "826646-2")
      (footprint "eagle-import:H2-2.54")
      (libsource (lib "eagle-import") (part "OSD3358-SM-RED Platform_826646-2"))
    )
    (comp (ref "J41")
      (value "826646-2")
      (footprint "eagle-import:H2-2.54")
      (libsource (lib "eagle-import") (part "OSD3358-SM-RED Platform_826646-2"))
    )
    (comp (ref "J42")
      (value "826646-2")
      (footprint "eagle-import:H2-2.54")
      (libsource (lib "eagle-import") (part "OSD3358-SM-RED Platform_826646-2"))
    )
    (comp (ref "J43")
      (value "826646-2")
      (footprint "eagle-import:H2-2.54")
      (libsource (lib "eagle-import") (part "OSD3358-SM-RED Platform_826646-2"))
    )
    (comp (ref "J45")
      (value "826646-2")
      (footprint "eagle-import:H2-2.54")
      (libsource (lib "eagle-import") (part "OSD3358-SM-RED Platform_826646-2"))
    )
    (comp (ref "J51")
      (value "826646-2")
      (footprint "eagle-import:H2-2.54")
      (libsource (lib "eagle-import") (part "OSD3358-SM-RED Platform_826646-2"))
    )
    (comp (ref "J52")
      (value "826646-2")
      (footprint "eagle-import:H2-2.54")
      (libsource (lib "eagle-import") (part "OSD3358-SM-RED Platform_826646-2"))
    )
    (comp (ref "J53")
      (value "826646-2")
      (footprint "eagle-import:H2-2.54")
      (libsource (lib "eagle-import") (part "OSD3358-SM-RED Platform_826646-2"))
    )
    (comp (ref "J61")
      (value "826646-2")
      (footprint "eagle-import:H2-2.54")
      (libsource (lib "eagle-import") (part "OSD3358-SM-RED Platform_826646-2"))
    )
    (comp (ref "J62")
      (value "826646-2")
      (footprint "eagle-import:H2-2.54")
      (libsource (lib "eagle-import") (part "OSD3358-SM-RED Platform_826646-2"))
    )
    (comp (ref "J63")
      (value "826646-2")
      (footprint "eagle-import:H2-2.54")
      (libsource (lib "eagle-import") (part "OSD3358-SM-RED Platform_826646-2"))
    )
    (comp (ref "J450")
      (value "826646-2")
      (footprint "eagle-import:H2-2.54")
      (libsource (lib "eagle-import") (part "OSD3358-SM-RED Platform_826646-2"))
    )
    (comp (ref "J454")
      (value "826646-2")
      (footprint "eagle-import:H2-2.54")
      (libsource (lib "eagle-import") (part "OSD3358-SM-RED Platform_826646-2"))
    )
    (comp (ref "K1")
      (value "G5LE-14-CF DC24")
      (footprint "eagle-import:JS-M")
      (libsource (lib "eagle-import") (part "G5LE-14-CF"))
    )
    (comp (ref "K2")
      (value "G5LE-14-CF DC24")
      (footprint "eagle-import:JS-M")
      (libsource (lib "eagle-import") (part "G5LE-14-CF"))
    )
    (comp (ref "K3")
      (value "G5LE-14-CF DC24")
      (footprint "eagle-import:JS-M")
      (libsource (lib "eagle-import") (part "G5LE-14-CF"))
    )
    (comp (ref "K4")
      (value "G5LE-14-CF DC24")
      (footprint "eagle-import:JS-M")
      (libsource (lib "eagle-import") (part "G5LE-14-CF"))
    )
    (comp (ref "K5")
      (value "G5LE-14-CF DC24")
      (footprint "eagle-import:JS-M")
      (libsource (lib "eagle-import") (part "G5LE-14-CF"))
    )
    (comp (ref "L2")
      (value "SRP1265A-470M")
      (footprint "eagle-import:SRP1265")
      (libsource (lib "eagle-import") (part "SRP1265"))
    )
    (comp (ref "MGT1")
      (value "MOUNTING_HOLE")
      (footprint "eagle-import:MOUNTING_HOLE")
      (libsource (lib "eagle-import") (part "MOUNTING_HOLE"))
    )
    (comp (ref "MGT2")
      (value "MOUNTING_HOLE")
      (footprint "eagle-import:MOUNTING_HOLE")
      (libsource (lib "eagle-import") (part "MOUNTING_HOLE"))
    )
    (comp (ref "MGT3")
      (value "MOUNTING_HOLE")
      (footprint "eagle-import:MOUNTING_HOLE")
      (libsource (lib "eagle-import") (part "MOUNTING_HOLE"))
    )
    (comp (ref "MGT4")
      (value "MOUNTING_HOLE")
      (footprint "eagle-import:MOUNTING_HOLE")
      (libsource (lib "eagle-import") (part "MOUNTING_HOLE"))
    )
    (comp (ref "Q1")
      (value "MMBT2907")
      (footprint "eagle-import:SOT23-BEC")
      (libsource (lib "eagle-import") (part "MMBT2907SMD"))
    )
    (comp (ref "R3")
      (value "0, 1%")
      (footprint "eagle-import:R0402")
      (libsource (lib "eagle-import") (part "OSD3358-SM-RED Platform_R-US_R0402"))
    )
    (comp (ref "R4")
      (value "0, 1%")
      (footprint "eagle-import:R0402")
      (libsource (lib "eagle-import") (part "OSD3358-SM-RED Platform_R-US_R0402"))
    )
    (comp (ref "R5")
      (value "0")
      (footprint "eagle-import:R0402")
      (libsource (lib "eagle-import") (part "R-US_R0402"))
    )
    (comp (ref "R6")
      (value "100K, DNI")
      (footprint "eagle-import:R0402")
      (libsource (lib "eagle-import") (part "R-US_R0402"))
    )
    (comp (ref "R8")
      (value "1K")
      (footprint "eagle-import:R0402")
      (libsource (lib "eagle-import") (part "R-US_R0402"))
    )
    (comp (ref "R10")
      (value "0, 1%")
      (footprint "eagle-import:R0805")
      (libsource (lib "eagle-import") (part "OSD3358-SM-RED Platform_R-US_R0805"))
    )
    (comp (ref "R11")
      (value "0")
      (footprint "eagle-import:R0402")
      (libsource (lib "eagle-import") (part "R-US_R0402"))
    )
    (comp (ref "R12")
      (value "1.5K, 1%")
      (footprint "eagle-import:R0402")
      (libsource (lib "eagle-import") (part "OSD3358-SM-RED Platform_R-US_R0402"))
    )
    (comp (ref "R13")
      (value "1.5K, 1%")
      (footprint "eagle-import:R0402")
      (libsource (lib "eagle-import") (part "OSD3358-SM-RED Platform_R-US_R0402"))
    )
    (comp (ref "R15")
      (value "40.2K")
      (footprint "eagle-import:R0402")
      (libsource (lib "eagle-import") (part "R-US_R0402"))
    )
    (comp (ref "R18")
      (value "4.75K, 1%")
      (footprint "eagle-import:R0402")
      (libsource (lib "eagle-import") (part "OSD3358-SM-RED Platform_R-US_R0402"))
    )
    (comp (ref "R20")
      (value "10K")
      (footprint "eagle-import:R0402")
      (libsource (lib "eagle-import") (part "R-US_R0402"))
    )
    (comp (ref "R21")
      (value "499")
      (footprint "eagle-import:R0402")
      (libsource (lib "eagle-import") (part "R-US_R0402"))
    )
    (comp (ref "R22")
      (value "4.75K, 1%")
      (footprint "eagle-import:R0402")
      (libsource (lib "eagle-import") (part "OSD3358-SM-RED Platform_R-US_R0402"))
    )
    (comp (ref "R25")
      (value "0, 1%")
      (footprint "eagle-import:R0402")
      (libsource (lib "eagle-import") (part "OSD3358-SM-RED Platform_R-US_R0402"))
    )
    (comp (ref "R26")
      (value "1.5K, 1%")
      (footprint "eagle-import:R0402")
      (libsource (lib "eagle-import") (part "OSD3358-SM-RED Platform_R-US_R0402"))
    )
    (comp (ref "R27")
      (value "100K, 1%")
      (footprint "eagle-import:R0402")
      (libsource (lib "eagle-import") (part "OSD3358-SM-RED Platform_R-US_R0402"))
    )
    (comp (ref "R28")
      (value "0, 1%")
      (footprint "eagle-import:R0402")
      (libsource (lib "eagle-import") (part "OSD3358-SM-RED Platform_R-US_R0402"))
    )
    (comp (ref "R29")
      (value "0, 1%")
      (footprint "eagle-import:R0402")
      (libsource (lib "eagle-import") (part "OSD3358-SM-RED Platform_R-US_R0402"))
    )
    (comp (ref "R30")
      (value "0, 1%")
      (footprint "eagle-import:R0402")
      (libsource (lib "eagle-import") (part "OSD3358-SM-RED Platform_R-US_R0402"))
    )
    (comp (ref "R31")
      (value "22, 1%")
      (footprint "eagle-import:R0402")
      (libsource (lib "eagle-import") (part "OSD3358-SM-RED Platform_R-US_R0402"))
    )
    (comp (ref "R33")
      (value "0, 1%")
      (footprint "eagle-import:R0402")
      (libsource (lib "eagle-import") (part "OSD3358-SM-RED Platform_R-US_R0402"))
    )
    (comp (ref "R34")
      (value ".1, 0805")
      (footprint "eagle-import:R0805")
      (libsource (lib "eagle-import") (part "OSD3358-SM-RED Platform_R-US_R0805"))
    )
    (comp (ref "R35")
      (value "1K")
      (footprint "eagle-import:RN0804")
      (libsource (lib "eagle-import") (part "RESISTOR.NETWORK-(4)"))
    )
    (comp (ref "R39")
      (value "4.75K, 1%")
      (footprint "eagle-import:R0402")
      (libsource (lib "eagle-import") (part "OSD3358-SM-RED Platform_R-US_R0402"))
    )
    (comp (ref "R40")
      (value "4.75K, 1%")
      (footprint "eagle-import:R0402")
      (libsource (lib "eagle-import") (part "OSD3358-SM-RED Platform_R-US_R0402"))
    )
    (comp (ref "R41")
      (value "4.75K, 1%")
      (footprint "eagle-import:R0402")
      (libsource (lib "eagle-import") (part "OSD3358-SM-RED Platform_R-US_R0402"))
    )
    (comp (ref "R53")
      (value "100K, 1%")
      (footprint "eagle-import:R0402")
      (libsource (lib "eagle-import") (part "OSD3358-SM-RED Platform_R-US_R0402"))
    )
    (comp (ref "R54")
      (value "100K, 1%, DNI")
      (footprint "eagle-import:R0402")
      (libsource (lib "eagle-import") (part "OSD3358-SM-RED Platform_R-US_R0402"))
    )
    (comp (ref "R55")
      (value "100K, 1%")
      (footprint "eagle-import:R0402")
      (libsource (lib "eagle-import") (part "OSD3358-SM-RED Platform_R-US_R0402"))
    )
    (comp (ref "R56")
      (value "100K, 1%")
      (footprint "eagle-import:R0402")
      (libsource (lib "eagle-import") (part "OSD3358-SM-RED Platform_R-US_R0402"))
    )
    (comp (ref "R57")
      (value "100K, 1%")
      (footprint "eagle-import:R0402")
      (libsource (lib "eagle-import") (part "OSD3358-SM-RED Platform_R-US_R0402"))
    )
    (comp (ref "R58")
      (value "100K, 1%")
      (footprint "eagle-import:R0402")
      (libsource (lib "eagle-import") (part "OSD3358-SM-RED Platform_R-US_R0402"))
    )
    (comp (ref "R59")
      (value "100K, 1%")
      (footprint "eagle-import:R0402")
      (libsource (lib "eagle-import") (part "OSD3358-SM-RED Platform_R-US_R0402"))
    )
    (comp (ref "R60")
      (value "100K, 1%")
      (footprint "eagle-import:R0402")
      (libsource (lib "eagle-import") (part "OSD3358-SM-RED Platform_R-US_R0402"))
    )
    (comp (ref "R61")
      (value "100K, 1%")
      (footprint "eagle-import:R0402")
      (libsource (lib "eagle-import") (part "OSD3358-SM-RED Platform_R-US_R0402"))
    )
    (comp (ref "R62")
      (value "100K, 1%")
      (footprint "eagle-import:R0402")
      (libsource (lib "eagle-import") (part "OSD3358-SM-RED Platform_R-US_R0402"))
    )
    (comp (ref "R63")
      (value "100K, 1%")
      (footprint "eagle-import:R0402")
      (libsource (lib "eagle-import") (part "OSD3358-SM-RED Platform_R-US_R0402"))
    )
    (comp (ref "R64")
      (value "100K, 1%, DNI")
      (footprint "eagle-import:R0402")
      (libsource (lib "eagle-import") (part "OSD3358-SM-RED Platform_R-US_R0402"))
    )
    (comp (ref "R65")
      (value "100K, 1%, DNI")
      (footprint "eagle-import:R0402")
      (libsource (lib "eagle-import") (part "OSD3358-SM-RED Platform_R-US_R0402"))
    )
    (comp (ref "R66")
      (value "100K, 1%, DNI")
      (footprint "eagle-import:R0402")
      (libsource (lib "eagle-import") (part "OSD3358-SM-RED Platform_R-US_R0402"))
    )
    (comp (ref "R67")
      (value "100K, 1%")
      (footprint "eagle-import:R0402")
      (libsource (lib "eagle-import") (part "OSD3358-SM-RED Platform_R-US_R0402"))
    )
    (comp (ref "R68")
      (value "100K, 1%")
      (footprint "eagle-import:R0402")
      (libsource (lib "eagle-import") (part "OSD3358-SM-RED Platform_R-US_R0402"))
    )
    (comp (ref "R69")
      (value "100, 1%")
      (footprint "eagle-import:R0402")
      (libsource (lib "eagle-import") (part "OSD3358-SM-RED Platform_R-US_R0402"))
    )
    (comp (ref "R70")
      (value "100K, 1%, DNI")
      (footprint "eagle-import:R0402")
      (libsource (lib "eagle-import") (part "OSD3358-SM-RED Platform_R-US_R0402"))
    )
    (comp (ref "R71")
      (value "100K, 1%")
      (footprint "eagle-import:R0402")
      (libsource (lib "eagle-import") (part "OSD3358-SM-RED Platform_R-US_R0402"))
    )
    (comp (ref "R72")
      (value "100K, 1%, DNI")
      (footprint "eagle-import:R0402")
      (libsource (lib "eagle-import") (part "OSD3358-SM-RED Platform_R-US_R0402"))
    )
    (comp (ref "R73")
      (value "100K, 1%, DNI")
      (footprint "eagle-import:R0402")
      (libsource (lib "eagle-import") (part "OSD3358-SM-RED Platform_R-US_R0402"))
    )
    (comp (ref "R74")
      (value "100K, 1%, DNI")
      (footprint "eagle-import:R0402")
      (libsource (lib "eagle-import") (part "OSD3358-SM-RED Platform_R-US_R0402"))
    )
    (comp (ref "R75")
      (value "100K, 1%, DNI")
      (footprint "eagle-import:R0402")
      (libsource (lib "eagle-import") (part "OSD3358-SM-RED Platform_R-US_R0402"))
    )
    (comp (ref "R76")
      (value "100K, 1%, DNI")
      (footprint "eagle-import:R0402")
      (libsource (lib "eagle-import") (part "OSD3358-SM-RED Platform_R-US_R0402"))
    )
    (comp (ref "R77")
      (value "100K, 1%, DNI")
      (footprint "eagle-import:R0402")
      (libsource (lib "eagle-import") (part "OSD3358-SM-RED Platform_R-US_R0402"))
    )
    (comp (ref "R78")
      (value "100K, 1%, DNI")
      (footprint "eagle-import:R0402")
      (libsource (lib "eagle-import") (part "OSD3358-SM-RED Platform_R-US_R0402"))
    )
    (comp (ref "R79")
      (value "100K, 1%, DNI")
      (footprint "eagle-import:R0402")
      (libsource (lib "eagle-import") (part "OSD3358-SM-RED Platform_R-US_R0402"))
    )
    (comp (ref "R80")
      (value "100K, 1%, DNI")
      (footprint "eagle-import:R0402")
      (libsource (lib "eagle-import") (part "OSD3358-SM-RED Platform_R-US_R0402"))
    )
    (comp (ref "R81")
      (value "100K, 1%")
      (footprint "eagle-import:R0402")
      (libsource (lib "eagle-import") (part "OSD3358-SM-RED Platform_R-US_R0402"))
    )
    (comp (ref "R82")
      (value "100K, 1%")
      (footprint "eagle-import:R0402")
      (libsource (lib "eagle-import") (part "OSD3358-SM-RED Platform_R-US_R0402"))
    )
    (comp (ref "R83")
      (value "100K, 1%")
      (footprint "eagle-import:R0402")
      (libsource (lib "eagle-import") (part "OSD3358-SM-RED Platform_R-US_R0402"))
    )
    (comp (ref "R84")
      (value "100K, 1%, DNI")
      (footprint "eagle-import:R0402")
      (libsource (lib "eagle-import") (part "OSD3358-SM-RED Platform_R-US_R0402"))
    )
    (comp (ref "R85")
      (value "100K, 1%, DNI")
      (footprint "eagle-import:R0402")
      (libsource (lib "eagle-import") (part "OSD3358-SM-RED Platform_R-US_R0402"))
    )
    (comp (ref "R86")
      (value "10K, 1%")
      (footprint "eagle-import:R0402")
      (libsource (lib "eagle-import") (part "OSD3358-SM-RED Platform_R-US_R0402"))
    )
    (comp (ref "R87")
      (value "10K, 1%")
      (footprint "eagle-import:R0402")
      (libsource (lib "eagle-import") (part "OSD3358-SM-RED Platform_R-US_R0402"))
    )
    (comp (ref "R88")
      (value "10K, 1%")
      (footprint "eagle-import:R0402")
      (libsource (lib "eagle-import") (part "OSD3358-SM-RED Platform_R-US_R0402"))
    )
    (comp (ref "R89")
      (value "10K, 1%")
      (footprint "eagle-import:R0402")
      (libsource (lib "eagle-import") (part "OSD3358-SM-RED Platform_R-US_R0402"))
    )
    (comp (ref "R90")
      (value "10K, 1%")
      (footprint "eagle-import:R0402")
      (libsource (lib "eagle-import") (part "OSD3358-SM-RED Platform_R-US_R0402"))
    )
    (comp (ref "R91")
      (value "10K, 1%")
      (footprint "eagle-import:R0402")
      (libsource (lib "eagle-import") (part "OSD3358-SM-RED Platform_R-US_R0402"))
    )
    (comp (ref "R92")
      (value "10K, 1%")
      (footprint "eagle-import:R0402")
      (libsource (lib "eagle-import") (part "OSD3358-SM-RED Platform_R-US_R0402"))
    )
    (comp (ref "R163")
      (value "100K, DNI")
      (footprint "eagle-import:R0402")
      (libsource (lib "eagle-import") (part "OSD3358-SM-RED Platform_R-US_R0402"))
    )
    (comp (ref "R164")
      (value "1.5K, 1%")
      (footprint "eagle-import:R0402")
      (libsource (lib "eagle-import") (part "OSD3358-SM-RED Platform_R-US_R0402"))
    )
    (comp (ref "R168")
      (value "10K")
      (footprint "eagle-import:R0402")
      (libsource (lib "eagle-import") (part "OSD3358-SM-RED Platform_R-US_R0402"))
    )
    (comp (ref "R169")
      (value "1.5K, 1%")
      (footprint "eagle-import:R0402")
      (libsource (lib "eagle-import") (part "OSD3358-SM-RED Platform_R-US_R0402"))
    )
    (comp (ref "R170")
      (value "1.5K, 1%")
      (footprint "eagle-import:R0402")
      (libsource (lib "eagle-import") (part "OSD3358-SM-RED Platform_R-US_R0402"))
    )
    (comp (ref "R171")
      (value "10K")
      (footprint "eagle-import:R0402")
      (libsource (lib "eagle-import") (part "OSD3358-SM-RED Platform_R-US_R0402"))
    )
    (comp (ref "R172")
      (value "10K")
      (footprint "eagle-import:R0402")
      (libsource (lib "eagle-import") (part "OSD3358-SM-RED Platform_R-US_R0402"))
    )
    (comp (ref "R173")
      (value "10K")
      (footprint "eagle-import:R0402")
      (libsource (lib "eagle-import") (part "OSD3358-SM-RED Platform_R-US_R0402"))
    )
    (comp (ref "R174")
      (value "10K")
      (footprint "eagle-import:R0402")
      (libsource (lib "eagle-import") (part "OSD3358-SM-RED Platform_R-US_R0402"))
    )
    (comp (ref "R175")
      (value "10K")
      (footprint "eagle-import:R0402")
      (libsource (lib "eagle-import") (part "OSD3358-SM-RED Platform_R-US_R0402"))
    )
    (comp (ref "R181")
      (value "B72520T0300K062")
      (footprint "eagle-import:CT_CN1206")
      (libsource (lib "eagle-import") (part "VARISTORCN1206"))
    )
    (comp (ref "R182")
      (value "B72520T0300K062")
      (footprint "eagle-import:CT_CN1206")
      (libsource (lib "eagle-import") (part "VARISTORCN1206"))
    )
    (comp (ref "R183")
      (value "B72520T0300K062")
      (footprint "eagle-import:CT_CN1206")
      (libsource (lib "eagle-import") (part "VARISTORCN1206"))
    )
    (comp (ref "R184")
      (value "B72520T0300K062")
      (footprint "eagle-import:CT_CN1206")
      (libsource (lib "eagle-import") (part "VARISTORCN1206"))
    )
    (comp (ref "R185")
      (value "B72520T0300K062")
      (footprint "eagle-import:CT_CN1206")
      (libsource (lib "eagle-import") (part "VARISTORCN1206"))
    )
    (comp (ref "R186")
      (value "B72520T0300K062")
      (footprint "eagle-import:CT_CN1206")
      (libsource (lib "eagle-import") (part "VARISTORCN1206"))
    )
    (comp (ref "R211")
      (value "80, 0.1%")
      (footprint "eagle-import:0309_12")
      (libsource (lib "eagle-import") (part "resistor_348_R-US_0309/12"))
    )
    (comp (ref "R212")
      (value "10K, 1%")
      (footprint "eagle-import:R0805")
      (libsource (lib "eagle-import") (part "OSD3358-SM-RED Platform_R-US_R0805"))
    )
    (comp (ref "R213")
      (value "2K, 1%")
      (footprint "eagle-import:R0805")
      (libsource (lib "eagle-import") (part "OSD3358-SM-RED Platform_R-US_R0805"))
    )
    (comp (ref "R214")
      (value "10K, 1%")
      (footprint "eagle-import:R0805")
      (libsource (lib "eagle-import") (part "OSD3358-SM-RED Platform_R-US_R0805"))
    )
    (comp (ref "R215")
      (value "100K")
      (footprint "eagle-import:R0805")
      (libsource (lib "eagle-import") (part "OSD3358-SM-RED Platform_R-US_R0805"))
    )
    (comp (ref "R221")
      (value "80, 0.1%")
      (footprint "eagle-import:0309_12")
      (libsource (lib "eagle-import") (part "resistor_348_R-US_0309/12"))
    )
    (comp (ref "R222")
      (value "10K, 1%")
      (footprint "eagle-import:R0805")
      (libsource (lib "eagle-import") (part "OSD3358-SM-RED Platform_R-US_R0805"))
    )
    (comp (ref "R223")
      (value "2K, 1%")
      (footprint "eagle-import:R0805")
      (libsource (lib "eagle-import") (part "OSD3358-SM-RED Platform_R-US_R0805"))
    )
    (comp (ref "R224")
      (value "10K, 1%")
      (footprint "eagle-import:R0805")
      (libsource (lib "eagle-import") (part "OSD3358-SM-RED Platform_R-US_R0805"))
    )
    (comp (ref "R225")
      (value "100K")
      (footprint "eagle-import:R0805")
      (libsource (lib "eagle-import") (part "OSD3358-SM-RED Platform_R-US_R0805"))
    )
    (comp (ref "R231")
      (value "80, 0.1%")
      (footprint "eagle-import:0309_12")
      (libsource (lib "eagle-import") (part "resistor_348_R-US_0309/12"))
    )
    (comp (ref "R232")
      (value "10K, 1%")
      (footprint "eagle-import:R0805")
      (libsource (lib "eagle-import") (part "OSD3358-SM-RED Platform_R-US_R0805"))
    )
    (comp (ref "R233")
      (value "2K, 1%")
      (footprint "eagle-import:R0805")
      (libsource (lib "eagle-import") (part "OSD3358-SM-RED Platform_R-US_R0805"))
    )
    (comp (ref "R234")
      (value "10K, 1%")
      (footprint "eagle-import:R0805")
      (libsource (lib "eagle-import") (part "OSD3358-SM-RED Platform_R-US_R0805"))
    )
    (comp (ref "R235")
      (value "100K")
      (footprint "eagle-import:R0805")
      (libsource (lib "eagle-import") (part "OSD3358-SM-RED Platform_R-US_R0805"))
    )
    (comp (ref "R241")
      (value "80, 0.1%")
      (footprint "eagle-import:0309_12")
      (libsource (lib "eagle-import") (part "resistor_348_R-US_0309/12"))
    )
    (comp (ref "R242")
      (value "10K, 1%")
      (footprint "eagle-import:R0805")
      (libsource (lib "eagle-import") (part "OSD3358-SM-RED Platform_R-US_R0805"))
    )
    (comp (ref "R243")
      (value "2K, 1%")
      (footprint "eagle-import:R0805")
      (libsource (lib "eagle-import") (part "OSD3358-SM-RED Platform_R-US_R0805"))
    )
    (comp (ref "R244")
      (value "10K, 1%")
      (footprint "eagle-import:R0805")
      (libsource (lib "eagle-import") (part "OSD3358-SM-RED Platform_R-US_R0805"))
    )
    (comp (ref "R245")
      (value "100K")
      (footprint "eagle-import:R0805")
      (libsource (lib "eagle-import") (part "OSD3358-SM-RED Platform_R-US_R0805"))
    )
    (comp (ref "R251")
      (value "80, 0.1%")
      (footprint "eagle-import:0309_12")
      (libsource (lib "eagle-import") (part "resistor_348_R-US_0309/12"))
    )
    (comp (ref "R252")
      (value "10K, 1%")
      (footprint "eagle-import:R0805")
      (libsource (lib "eagle-import") (part "OSD3358-SM-RED Platform_R-US_R0805"))
    )
    (comp (ref "R253")
      (value "2K, 1%")
      (footprint "eagle-import:R0805")
      (libsource (lib "eagle-import") (part "OSD3358-SM-RED Platform_R-US_R0805"))
    )
    (comp (ref "R254")
      (value "10K, 1%")
      (footprint "eagle-import:R0805")
      (libsource (lib "eagle-import") (part "OSD3358-SM-RED Platform_R-US_R0805"))
    )
    (comp (ref "R255")
      (value "100K")
      (footprint "eagle-import:R0805")
      (libsource (lib "eagle-import") (part "OSD3358-SM-RED Platform_R-US_R0805"))
    )
    (comp (ref "R261")
      (value "80, 0.1%")
      (footprint "eagle-import:0309_12")
      (libsource (lib "eagle-import") (part "resistor_348_R-US_0309/12"))
    )
    (comp (ref "R262")
      (value "10K, 1%")
      (footprint "eagle-import:R0805")
      (libsource (lib "eagle-import") (part "OSD3358-SM-RED Platform_R-US_R0805"))
    )
    (comp (ref "R263")
      (value "2K, 1%")
      (footprint "eagle-import:R0805")
      (libsource (lib "eagle-import") (part "OSD3358-SM-RED Platform_R-US_R0805"))
    )
    (comp (ref "R264")
      (value "10K, 1%")
      (footprint "eagle-import:R0805")
      (libsource (lib "eagle-import") (part "OSD3358-SM-RED Platform_R-US_R0805"))
    )
    (comp (ref "R265")
      (value "100K")
      (footprint "eagle-import:R0805")
      (libsource (lib "eagle-import") (part "OSD3358-SM-RED Platform_R-US_R0805"))
    )
    (comp (ref "R281")
      (value "10K")
      (footprint "eagle-import:RN0804")
      (libsource (lib "eagle-import") (part "RESISTOR.NETWORK-(4)"))
    )
    (comp (ref "R282")
      (value "10K")
      (footprint "eagle-import:RN0804")
      (libsource (lib "eagle-import") (part "RESISTOR.NETWORK-(4)"))
    )
    (comp (ref "R291")
      (value "10K")
      (footprint "eagle-import:RN0804")
      (libsource (lib "eagle-import") (part "RESISTOR.NETWORK-(4)"))
    )
    (comp (ref "R301")
      (value "1K")
      (footprint "eagle-import:R0402")
      (libsource (lib "eagle-import") (part "OSD3358-SM-RED Platform_R-US_R0402"))
    )
    (comp (ref "R302")
      (value "1K")
      (footprint "eagle-import:R0402")
      (libsource (lib "eagle-import") (part "OSD3358-SM-RED Platform_R-US_R0402"))
    )
    (comp (ref "R303")
      (value "1K, DNI")
      (footprint "eagle-import:R0402")
      (libsource (lib "eagle-import") (part "OSD3358-SM-RED Platform_R-US_R0402"))
    )
    (comp (ref "R304")
      (value "1K, DNI")
      (footprint "eagle-import:R0402")
      (libsource (lib "eagle-import") (part "OSD3358-SM-RED Platform_R-US_R0402"))
    )
    (comp (ref "R305")
      (value "150, 1%")
      (footprint "eagle-import:R0805")
      (libsource (lib "eagle-import") (part "OSD3358-SM-RED Platform_R-US_R0805"))
    )
    (comp (ref "R401")
      (value "1K")
      (footprint "eagle-import:R0402")
      (libsource (lib "eagle-import") (part "OSD3358-SM-RED Platform_R-US_R0402"))
    )
    (comp (ref "R402")
      (value "1K")
      (footprint "eagle-import:R0402")
      (libsource (lib "eagle-import") (part "OSD3358-SM-RED Platform_R-US_R0402"))
    )
    (comp (ref "R801")
      (value "1K")
      (footprint "eagle-import:R0402")
      (libsource (lib "eagle-import") (part "OSD3358-SM-RED Platform_R-US_R0402"))
    )
    (comp (ref "R802")
      (value "1K")
      (footprint "eagle-import:R0402")
      (libsource (lib "eagle-import") (part "OSD3358-SM-RED Platform_R-US_R0402"))
    )
    (comp (ref "RTC1")
      (value "DS3231MZ+")
      (footprint "eagle-import:SO08")
      (libsource (lib "eagle-import") (part "DS3231M"))
    )
    (comp (ref "S1")
      (value "KMR231GLFS")
      (footprint "eagle-import:SW4SMD_63X161LS")
      (libsource (lib "eagle-import") (part "KMR231GLFS"))
    )
    (comp (ref "S2")
      (value "KMR231GLFS")
      (footprint "eagle-import:SW4SMD_63X161LS")
      (libsource (lib "eagle-import") (part "OSD3358-SM-RED Platform_KMR231GLFS"))
    )
    (comp (ref "S11")
      (value "P101")
      (footprint "eagle-import:P101")
      (libsource (lib "eagle-import") (part "P101"))
    )
    (comp (ref "S12")
      (value "P101")
      (footprint "eagle-import:P101")
      (libsource (lib "eagle-import") (part "P101"))
    )
    (comp (ref "S13")
      (value "DS04")
      (footprint "eagle-import:DS-04")
      (libsource (lib "eagle-import") (part "DS04"))
    )
    (comp (ref "T4")
      (value "DA2304-AL")
      (footprint "eagle-import:DA230X-AL")
      (libsource (lib "eagle-import") (part "DA2304-AL"))
    )
    (comp (ref "TP1")
      (value "TPB0,65")
      (footprint "eagle-import:TP_B0,65")
      (libsource (lib "eagle-import") (part "OSD3358-SM-RED Platform_TPB0,65"))
    )
    (comp (ref "TP2")
      (value "TPB0,65")
      (footprint "eagle-import:TP_B0,65")
      (libsource (lib "eagle-import") (part "OSD3358-SM-RED Platform_TPB0,65"))
    )
    (comp (ref "TP3")
      (value "TPB0,65")
      (footprint "eagle-import:TP_B0,65")
      (libsource (lib "eagle-import") (part "OSD3358-SM-RED Platform_TPB0,65"))
    )
    (comp (ref "TP4")
      (value "TPB0,65")
      (footprint "eagle-import:TP_B0,65")
      (libsource (lib "eagle-import") (part "OSD3358-SM-RED Platform_TPB0,65"))
    )
    (comp (ref "TP5")
      (value "TESTPAD/W_HOLE_1X1")
      (footprint "eagle-import:TESTPAD_W_HOLE_1X1")
      (libsource (lib "eagle-import") (part "TESTPAD/W_HOLE_1X1"))
    )
    (comp (ref "TP6")
      (value "TESTPAD/W_HOLE_1X1")
      (footprint "eagle-import:TESTPAD_W_HOLE_1X1")
      (libsource (lib "eagle-import") (part "TESTPAD/W_HOLE_1X1"))
    )
    (comp (ref "TP7")
      (value "TESTPAD/W_HOLE_1X1")
      (footprint "eagle-import:TESTPAD_W_HOLE_1X1")
      (libsource (lib "eagle-import") (part "TESTPAD/W_HOLE_1X1"))
    )
    (comp (ref "TP8")
      (value "TESTPAD/W_HOLE_1X1")
      (footprint "eagle-import:TESTPAD_W_HOLE_1X1")
      (libsource (lib "eagle-import") (part "TESTPAD/W_HOLE_1X1"))
    )
    (comp (ref "TP9")
      (value "TESTPAD/W_HOLE_1X1")
      (footprint "eagle-import:TESTPAD_W_HOLE_1X1")
      (libsource (lib "eagle-import") (part "TESTPAD/W_HOLE_1X1"))
    )
    (comp (ref "TP10")
      (value "TESTPAD/W_HOLE_1X1")
      (footprint "eagle-import:TESTPAD_W_HOLE_1X1")
      (libsource (lib "eagle-import") (part "TESTPAD/W_HOLE_1X1"))
    )
    (comp (ref "TP11")
      (value "TPB0,65")
      (footprint "eagle-import:TP_B0,65")
      (libsource (lib "eagle-import") (part "OSD3358-SM-RED Platform_TPB0,65"))
    )
    (comp (ref "TP12")
      (value "TPB0,65")
      (footprint "eagle-import:TP_B0,65")
      (libsource (lib "eagle-import") (part "OSD3358-SM-RED Platform_TPB0,65"))
    )
    (comp (ref "TP13")
      (value "TPB0,65")
      (footprint "eagle-import:TP_B0,65")
      (libsource (lib "eagle-import") (part "OSD3358-SM-RED Platform_TPB0,65"))
    )
    (comp (ref "TP14")
      (value "TPB0,65")
      (footprint "eagle-import:TP_B0,65")
      (libsource (lib "eagle-import") (part "OSD3358-SM-RED Platform_TPB0,65"))
    )
    (comp (ref "TP15")
      (value "TPB0,65")
      (footprint "eagle-import:TP_B0,65")
      (libsource (lib "eagle-import") (part "OSD3358-SM-RED Platform_TPB0,65"))
    )
    (comp (ref "TP16")
      (value "TPB0,65")
      (footprint "eagle-import:TP_B0,65")
      (libsource (lib "eagle-import") (part "OSD3358-SM-RED Platform_TPB0,65"))
    )
    (comp (ref "TP17")
      (value "TESTPAD/W_HOLE_1X1")
      (footprint "eagle-import:TESTPAD_W_HOLE_1X1")
      (libsource (lib "eagle-import") (part "TESTPAD/W_HOLE_1X1"))
    )
    (comp (ref "TP18")
      (value "TESTPAD/W_HOLE_1X1")
      (footprint "eagle-import:TESTPAD_W_HOLE_1X1")
      (libsource (lib "eagle-import") (part "TESTPAD/W_HOLE_1X1"))
    )
    (comp (ref "TP19")
      (value "TESTPAD/W_HOLE_1X1")
      (footprint "eagle-import:TESTPAD_W_HOLE_1X1")
      (libsource (lib "eagle-import") (part "TESTPAD/W_HOLE_1X1"))
    )
    (comp (ref "TP20")
      (value "TESTPAD/W_HOLE_1X1")
      (footprint "eagle-import:TESTPAD_W_HOLE_1X1")
      (libsource (lib "eagle-import") (part "TESTPAD/W_HOLE_1X1"))
    )
    (comp (ref "TP21")
      (value "TPB0,65")
      (footprint "eagle-import:TP_B0,65")
      (libsource (lib "eagle-import") (part "OSD3358-SM-RED Platform_TPB0,65"))
    )
    (comp (ref "TP22")
      (value "TPB0,65")
      (footprint "eagle-import:TP_B0,65")
      (libsource (lib "eagle-import") (part "OSD3358-SM-RED Platform_TPB0,65"))
    )
    (comp (ref "TP23")
      (value "TPB0,65")
      (footprint "eagle-import:TP_B0,65")
      (libsource (lib "eagle-import") (part "OSD3358-SM-RED Platform_TPB0,65"))
    )
    (comp (ref "TP24")
      (value "TPB0,65")
      (footprint "eagle-import:TP_B0,65")
      (libsource (lib "eagle-import") (part "OSD3358-SM-RED Platform_TPB0,65"))
    )
    (comp (ref "TP26")
      (value "TPB0,65")
      (footprint "eagle-import:TP_B0,65")
      (libsource (lib "eagle-import") (part "TPB0,65"))
    )
    (comp (ref "TP31")
      (value "TPB0,65")
      (footprint "eagle-import:TP_B0,65")
      (libsource (lib "eagle-import") (part "TPB0,65"))
    )
    (comp (ref "TP32")
      (value "TPB0,65")
      (footprint "eagle-import:TP_B0,65")
      (libsource (lib "eagle-import") (part "OSD3358-SM-RED Platform_TPB0,65"))
    )
    (comp (ref "TP33")
      (value "TPB0,65")
      (footprint "eagle-import:TP_B0,65")
      (libsource (lib "eagle-import") (part "OSD3358-SM-RED Platform_TPB0,65"))
    )
    (comp (ref "U1")
      (value "OSD3358-512M-ICB")
      (footprint "eagle-import:OSD335X-BGA-400")
      (libsource (lib "eagle-import") (part "OSD3358-512M-ICB"))
    )
    (comp (ref "U2")
      (value "TPD4S012_DRY_6_P1_M")
      (footprint "eagle-import:DRY6")
      (fields
        (field (name "GENERIC_PART_NUMBER") "TPD4S012")
        (field (name "MANUFACTURER") "Texas Instruments")
        (field (name "MANUFACTURER_PART_NUMBER") "tpd4s012_dry_6")
      )
      (libsource (lib "eagle-import") (part "TPD4S012_DRY_6_P1_M"))
    )
    (comp (ref "U4")
      (value "APX811-31UGSOT")
      (footprint "eagle-import:SOT143-R")
      (libsource (lib "eagle-import") (part "APX811-31UGSOT"))
    )
    (comp (ref "U5")
      (value "TLVH431")
      (footprint "eagle-import:SOT23-3")
      (libsource (lib "eagle-import") (part "TLVH431"))
    )
    (comp (ref "U6")
      (value "SN74LVC2G241_DCU_8")
      (footprint "eagle-import:DCU8")
      (fields
        (field (name "GENERIC_PART_NUMBER") "SN74LVC2G241")
        (field (name "MANUFACTURER") "Texas Instruments")
        (field (name "MANUFACTURER_PART_NUMBER") "sn74lvc2g241_dcu_8")
      )
      (libsource (lib "eagle-import") (part "SN74LVC2G241_DCU_8"))
    )
    (comp (ref "U16")
      (value "AT97SC3205T-G3M4400B")
      (footprint "eagle-import:QFN32-0.4-4X4MM")
      (libsource (lib "eagle-import") (part "AT97SC3205T-G3M4400B"))
    )
    (comp (ref "U27")
      (value "LAN8710")
      (footprint "eagle-import:LAN8710A-QFN32")
      (libsource (lib "eagle-import") (part "LAN8710"))
    )
    (comp (ref "U28")
      (value "TCAN1051HV")
      (footprint "eagle-import:BEAGLEBONE_BLUE_D8")
      (fields
        (field (name "MANUFACTURER") "Texas Instruments")
        (field (name "MANUFACTURER_PART_NUMBER") "TCAN1051HVD")
      )
      (libsource (lib "eagle-import") (part "TCAN1051HV"))
    )
    (comp (ref "U29")
      (value "MAX3483EESA+T")
      (footprint "eagle-import:21-0041B_8")
      (libsource (lib "eagle-import") (part "MAX3483EESA+T"))
    )
    (comp (ref "U40")
      (value "ISO3086TDW")
      (footprint "eagle-import:DW16")
      (libsource (lib "eagle-import") (part "ISO3086TDW"))
    )
    (comp (ref "VREG1")
      (value "LM2596S-5.0")
      (footprint "eagle-import:TO263-5")
      (libsource (lib "eagle-import") (part "LM2596S"))
    )
    (comp (ref "VREG2")
      (value "L7824CV")
      (footprint "eagle-import:78XXL")
      (libsource (lib "eagle-import") (part "78XXL"))
    )
    (comp (ref "VREG4")
      (value "TPS76350")
      (footprint "eagle-import:DBV5")
      (fields (field (name "MANUFACTURER_PART_NUMBER") "LP2985A33DBVR"))
      (libsource (lib "eagle-import") (part "LP2985A-33DBVR"))
    )
    (comp (ref "X1")
      (value "10118194-0001LF")
      (footprint "eagle-import:10118194-0001LF(MICRO-USB-B-AMPHENOL-FCI)")
      (libsource (lib "eagle-import") (part "10118194-0001LF"))
    )
    (comp (ref "X2")
      (value "J0011D01BNL")
      (footprint "eagle-import:J0011D01BNL")
      (libsource (lib "eagle-import") (part "J0011D01BNL"))
    )
    (comp (ref "X3")
      (value "MC4")
      (footprint "eagle-import:MC4")
      (libsource (lib "eagle-import") (part "MC4"))
    )
    (comp (ref "X4")
      (value "CTI-JTAG")
      (footprint "eagle-import:CTI-JTAG")
      (libsource (lib "eagle-import") (part "CTI-JTAG"))
    )
    (comp (ref "X5")
      (value "DM3CS-SF")
      (footprint "eagle-import:DM3CS-SF")
      (fields (field (name "MOUSER_PART_NUMBER") "798-DM3CSSF"))
      (libsource (lib "eagle-import") (part "DM3CS-SF"))
    )
    (comp (ref "X6")
      (value "6p-2.54")
      (footprint "eagle-import:H6-2.54")
      (fields (field (name "MPN") "P125-1106A1BS116A1"))
      (libsource (lib "eagle-import") (part "826646-6"))
    )
    (comp (ref "X7")
      (value "TH-2X10")
      (footprint "eagle-import:H2X10-2.54")
      (libsource (lib "eagle-import") (part "TH-2X10"))
    )
    (comp (ref "X8")
      (value "MC4")
      (footprint "eagle-import:MC4")
      (libsource (lib "eagle-import") (part "MC4"))
    )
    (comp (ref "X10")
      (value "MC4")
      (footprint "eagle-import:MC4")
      (libsource (lib "eagle-import") (part "MC4"))
    )
    (comp (ref "X11")
      (value "MC4")
      (footprint "eagle-import:MC4")
      (libsource (lib "eagle-import") (part "MC4"))
    )
    (comp (ref "X12")
      (value "MC4")
      (footprint "eagle-import:MC4")
      (libsource (lib "eagle-import") (part "MC4"))
    )
    (comp (ref "X21")
      (value "MC12")
      (footprint "eagle-import:MC12")
      (libsource (lib "eagle-import") (part "MC12"))
    )
    (comp (ref "X24")
      (value "MSTBA2")
      (footprint "eagle-import:MSTBA2")
      (fields (field (name "MF") "FARNELL") (field (name "MPN") "1757242"))
      (libsource (lib "eagle-import") (part "MSTBA2"))
    )
    (comp (ref "X41")
      (value "MSTBA3")
      (footprint "eagle-import:MSTBA3")
      (fields (field (name "MF") "FARNELL") (field (name "MPN") "1757255"))
      (libsource (lib "eagle-import") (part "MSTBA3"))
    )
    (comp (ref "Y7")
      (value "ECS-250-12-30-GN-TR")
      (footprint "eagle-import:XTAL_2-SMD(5X3.2MM)")
      (libsource (lib "eagle-import") (part "CRYSTAL-2-SMD"))
    )
  )
  (nets
    (net (code "1") (name "/1P8V_REF_1") (class "Default")
      (node (ref "IC10") (pin "8") (pinfunction "V+_8") (pintype "power_in"))
      (node (ref "IC11") (pin "8") (pinfunction "V+_8") (pintype "power_in"))
      (node (ref "IC14") (pin "1") (pinfunction "OUT_1") (pintype "output"))
      (node (ref "IC14") (pin "2") (pinfunction "-IN_2") (pintype "input"))
      (node (ref "R212") (pin "2") (pinfunction "2_2") (pintype "passive"))
      (node (ref "R222") (pin "2") (pinfunction "2_2") (pintype "passive"))
      (node (ref "R232") (pin "2") (pinfunction "2_2") (pintype "passive"))
      (node (ref "R242") (pin "2") (pinfunction "2_2") (pintype "passive"))
    )
    (net (code "2") (name "/1P8V_REF_2") (class "Default")
      (node (ref "IC12") (pin "8") (pinfunction "V+_8") (pintype "power_in"))
      (node (ref "IC14") (pin "6") (pinfunction "-IN_6") (pintype "input"))
      (node (ref "IC14") (pin "7") (pinfunction "OUT_7") (pintype "output"))
      (node (ref "R252") (pin "2") (pinfunction "2_2") (pintype "passive"))
      (node (ref "R262") (pin "2") (pinfunction "2_2") (pintype "passive"))
    )
    (net (code "3") (name "/5V_OUT") (class "Default")
      (node (ref "D18") (pin "C") (pinfunction "C_C") (pintype "passive"))
      (node (ref "L2") (pin "1") (pinfunction "1_1") (pintype "passive"))
      (node (ref "VREG1") (pin "2") (pinfunction "OUT_2") (pintype "output"))
    )
    (net (code "4") (name "/485_A") (class "Default")
      (node (ref "D305") (pin "1") (pinfunction "1_1") (pintype "passive"))
      (node (ref "R304") (pin "2") (pinfunction "2_2") (pintype "passive"))
      (node (ref "R305") (pin "2") (pinfunction "2_2") (pintype "passive"))
      (node (ref "U29") (pin "6") (pinfunction "A_6") (pintype "bidirectional"))
      (node (ref "X3") (pin "2") (pinfunction "SK_2") (pintype "passive"))
    )
    (net (code "5") (name "/485_B") (class "Default")
      (node (ref "D305") (pin "2") (pinfunction "2_2") (pintype "passive"))
      (node (ref "R303") (pin "1") (pinfunction "1_1") (pintype "passive"))
      (node (ref "R305") (pin "1") (pinfunction "1_1") (pintype "passive"))
      (node (ref "U29") (pin "7") (pinfunction "B_7") (pintype "bidirectional"))
      (node (ref "X3") (pin "3") (pinfunction "SK_3") (pintype "passive"))
    )
    (net (code "6") (name "/485_RXD") (class "Default")
      (node (ref "D402") (pin "1") (pinfunction "A_1") (pintype "passive"))
      (node (ref "J45") (pin "1") (pinfunction "1_1") (pintype "bidirectional"))
      (node (ref "U40") (pin "5") (pinfunction "R_5") (pintype "passive"))
    )
    (net (code "7") (name "/485_TXD") (class "Default")
      (node (ref "D401") (pin "1") (pinfunction "A_1") (pintype "passive"))
      (node (ref "J45") (pin "2") (pinfunction "2_2") (pintype "bidirectional"))
      (node (ref "U40") (pin "8") (pinfunction "D_8") (pintype "passive"))
    )
    (net (code "8") (name "/AIN0") (class "Default")
      (node (ref "U1") (pin "Y10") (pinfunction "AIN0_Y10") (pintype "bidirectional"))
    )
    (net (code "9") (name "/AIN1") (class "Default")
      (node (ref "IC10") (pin "1") (pinfunction "OUT_1") (pintype "output"))
      (node (ref "IC10") (pin "2") (pinfunction "-IN_2") (pintype "input"))
      (node (ref "R215") (pin "1") (pinfunction "1_1") (pintype "passive"))
      (node (ref "U1") (pin "W10") (pinfunction "AIN1_W10") (pintype "bidirectional"))
    )
    (net (code "10") (name "/AIN2") (class "Default")
      (node (ref "IC10") (pin "6") (pinfunction "-IN_6") (pintype "input"))
      (node (ref "IC10") (pin "7") (pinfunction "OUT_7") (pintype "output"))
      (node (ref "R225") (pin "1") (pinfunction "1_1") (pintype "passive"))
      (node (ref "U1") (pin "V10") (pinfunction "AIN2_V10") (pintype "bidirectional"))
    )
    (net (code "11") (name "/AIN3") (class "Default")
      (node (ref "IC11") (pin "1") (pinfunction "OUT_1") (pintype "output"))
      (node (ref "IC11") (pin "2") (pinfunction "-IN_2") (pintype "input"))
      (node (ref "R235") (pin "1") (pinfunction "1_1") (pintype "passive"))
      (node (ref "U1") (pin "V9") (pinfunction "AIN3_V9") (pintype "bidirectional"))
    )
    (net (code "12") (name "/AIN4") (class "Default")
      (node (ref "IC11") (pin "6") (pinfunction "-IN_6") (pintype "input"))
      (node (ref "IC11") (pin "7") (pinfunction "OUT_7") (pintype "output"))
      (node (ref "R245") (pin "1") (pinfunction "1_1") (pintype "passive"))
      (node (ref "U1") (pin "Y11") (pinfunction "AIN4_Y11") (pintype "bidirectional"))
    )
    (net (code "13") (name "/AIN5") (class "Default")
      (node (ref "IC12") (pin "1") (pinfunction "OUT_1") (pintype "output"))
      (node (ref "IC12") (pin "2") (pinfunction "-IN_2") (pintype "input"))
      (node (ref "R255") (pin "1") (pinfunction "1_1") (pintype "passive"))
      (node (ref "U1") (pin "W11") (pinfunction "AIN5_W11") (pintype "bidirectional"))
    )
    (net (code "14") (name "/AIN6") (class "Default")
      (node (ref "IC12") (pin "6") (pinfunction "-IN_6") (pintype "input"))
      (node (ref "IC12") (pin "7") (pinfunction "OUT_7") (pintype "output"))
      (node (ref "R265") (pin "1") (pinfunction "1_1") (pintype "passive"))
      (node (ref "U1") (pin "V11") (pinfunction "AIN6_V11") (pintype "bidirectional"))
    )
    (net (code "15") (name "/AIN7") (class "Default")
      (node (ref "U1") (pin "U12") (pinfunction "PMIC_MUX_OUT_U12") (pintype "bidirectional"))
      (node (ref "U1") (pin "V12") (pinfunction "AIN7_V12") (pintype "bidirectional"))
    )
    (net (code "16") (name "/B03_NO") (class "Default")
      (node (ref "K3") (pin "NO") (pinfunction "S_NO") (pintype "passive"))
      (node (ref "X21") (pin "6") (pinfunction "SK_6") (pintype "passive"))
    )
    (net (code "17") (name "/BAT_SENSE") (class "Default")
      (node (ref "TP6") (pin "P$1") (pinfunction "TP_P$1") (pintype "bidirectional"))
      (node (ref "U1") (pin "E19") (pinfunction "PMIC_BAT_SENSE_E19") (pintype "bidirectional"))
    )
    (net (code "18") (name "/BO1_C") (class "Default")
      (node (ref "K1") (pin "C") (pinfunction "P_C") (pintype "passive"))
      (node (ref "X21") (pin "9") (pinfunction "SK_9") (pintype "passive"))
    )
    (net (code "19") (name "/BO1_NO") (class "Default")
      (node (ref "K1") (pin "NO") (pinfunction "S_NO") (pintype "passive"))
      (node (ref "X21") (pin "10") (pinfunction "SK_10") (pintype "passive"))
    )
    (net (code "20") (name "/BO2_C") (class "Default")
      (node (ref "K2") (pin "C") (pinfunction "P_C") (pintype "passive"))
      (node (ref "X21") (pin "7") (pinfunction "SK_7") (pintype "passive"))
    )
    (net (code "21") (name "/BO2_NO") (class "Default")
      (node (ref "K2") (pin "NO") (pinfunction "S_NO") (pintype "passive"))
      (node (ref "X21") (pin "8") (pinfunction "SK_8") (pintype "passive"))
    )
    (net (code "22") (name "/BO3_C") (class "Default")
      (node (ref "K3") (pin "C") (pinfunction "P_C") (pintype "passive"))
      (node (ref "X21") (pin "5") (pinfunction "SK_5") (pintype "passive"))
    )
    (net (code "23") (name "/BO4_C") (class "Default")
      (node (ref "K4") (pin "C") (pinfunction "P_C") (pintype "passive"))
      (node (ref "X21") (pin "3") (pinfunction "SK_3") (pintype "passive"))
    )
    (net (code "24") (name "/BO4_NO") (class "Default")
      (node (ref "K4") (pin "NO") (pinfunction "S_NO") (pintype "passive"))
      (node (ref "X21") (pin "4") (pinfunction "SK_4") (pintype "passive"))
    )
    (net (code "25") (name "/B_UART0_RX") (class "Default")
      (node (ref "R27") (pin "2") (pinfunction "2_2") (pintype "passive"))
      (node (ref "U6") (pin "2") (pinfunction "1A_2") (pintype "input"))
      (node (ref "X6") (pin "4") (pinfunction "4_4") (pintype "bidirectional"))
    )
    (net (code "26") (name "/B_UART0_TX") (class "Default")
      (node (ref "U6") (pin "3") (pinfunction "2Y_3") (pintype "output"))
      (node (ref "X6") (pin "5") (pinfunction "5_5") (pintype "bidirectional"))
    )
    (net (code "27") (name "/CAN1_RXD") (class "Default")
      (node (ref "D802") (pin "1") (pinfunction "A_1") (pintype "passive"))
      (node (ref "U1") (pin "Y7") (pinfunction "UART1_RXD_Y7") (pintype "bidirectional"))
      (node (ref "U28") (pin "4") (pinfunction "RXD_4") (pintype "output"))
    )
    (net (code "28") (name "/CAN1_TXD") (class "Default")
      (node (ref "D801") (pin "1") (pinfunction "A_1") (pintype "passive"))
      (node (ref "U1") (pin "W7") (pinfunction "UART1_TXD_W7") (pintype "bidirectional"))
      (node (ref "U28") (pin "1") (pinfunction "TXD_1") (pintype "input"))
    )
    (net (code "29") (name "/CAN_H") (class "Default")
      (node (ref "D805") (pin "2") (pinfunction "2_2") (pintype "passive"))
      (node (ref "U28") (pin "7") (pinfunction "CANH_7") (pintype "bidirectional"))
      (node (ref "X8") (pin "3") (pinfunction "SK_3") (pintype "passive"))
    )
    (net (code "30") (name "/CAN_L") (class "Default")
      (node (ref "D805") (pin "1") (pinfunction "1_1") (pintype "passive"))
      (node (ref "U28") (pin "6") (pinfunction "CANL_6") (pintype "bidirectional"))
      (node (ref "X8") (pin "2") (pinfunction "SK_2") (pintype "passive"))
    )
    (net (code "31") (name "/CLKOUT2") (class "Default")
      (node (ref "C2") (pin "2") (pinfunction "2_2") (pintype "passive"))
      (node (ref "R3") (pin "2") (pinfunction "2_2") (pintype "passive"))
      (node (ref "X4") (pin "18") (pinfunction "EMU3_18") (pintype "bidirectional"))
    )
    (net (code "32") (name "/CRS") (class "Default")
      (node (ref "ER124") (pin "1") (pinfunction "1_1") (pintype "passive"))
      (node (ref "U27") (pin "14") (pinfunction "CRS_14") (pintype "bidirectional"))
    )
    (net (code "33") (name "/EHRPWM1A") (class "Default")
      (node (ref "J4") (pin "1") (pinfunction "1_1") (pintype "bidirectional"))
      (node (ref "U1") (pin "C13") (pinfunction "GPMC_A2_C13") (pintype "bidirectional"))
    )
    (net (code "34") (name "/EHRPWM1B") (class "Default")
      (node (ref "U1") (pin "A12") (pinfunction "GPMC_A3_A12") (pintype "bidirectional"))
    )
    (net (code "35") (name "/EHRPWM2A") (class "Default")
      (node (ref "J5") (pin "1") (pinfunction "1_1") (pintype "bidirectional"))
      (node (ref "U1") (pin "A17") (pinfunction "GPMC_AD8_A17") (pintype "bidirectional"))
    )
    (net (code "36") (name "/EHRPWM2B") (class "Default")
      (node (ref "J6") (pin "1") (pinfunction "1_1") (pintype "bidirectional"))
      (node (ref "U1") (pin "C16") (pinfunction "GPMC_AD9_C16") (pintype "bidirectional"))
    )
    (net (code "37") (name "/E_LED_GRN") (class "Default")
      (node (ref "U27") (pin "3") (pinfunction "LED1/REGOFF_3") (pintype "bidirectional"))
      (node (ref "X2") (pin "9") (pinfunction "GRNA_9") (pintype "passive"))
    )
    (net (code "38") (name "/E_LED_YEL") (class "Default")
      (node (ref "ER120") (pin "2") (pinfunction "2_2") (pintype "passive"))
      (node (ref "U27") (pin "2") (pinfunction "LED2/~{INTSEL}_2") (pintype "bidirectional"))
      (node (ref "X2") (pin "12") (pinfunction "YELA_12") (pintype "passive"))
    )
    (net (code "39") (name "/GPIO0_7") (class "Default")
      (node (ref "U1") (pin "V15") (pinfunction "ECAP0_IN_PWM0_OUT_V15") (pintype "bidirectional"))
      (node (ref "U29") (pin "2") (pinfunction "~{RE}_2") (pintype "input"))
      (node (ref "U29") (pin "3") (pinfunction "DE_3") (pintype "input"))
    )
    (net (code "40") (name "/GPIO0_18") (class "Default")
      (node (ref "U1") (pin "K3") (pinfunction "USB0_DRVVBUS_K3") (pintype "bidirectional"))
    )
    (net (code "41") (name "/GPIO1_12") (class "Default")
      (node (ref "IC2") (pin "2") (pinfunction "I2_2") (pintype "input"))
      (node (ref "U1") (pin "C15") (pinfunction "GPMC_AD12_C15") (pintype "bidirectional"))
    )
    (net (code "42") (name "/GPIO1_13") (class "Default")
      (node (ref "IC2") (pin "3") (pinfunction "I3_3") (pintype "input"))
      (node (ref "U1") (pin "B15") (pinfunction "GPMC_AD13_B15") (pintype "bidirectional"))
    )
    (net (code "43") (name "/GPIO1_14") (class "Default")
      (node (ref "IC2") (pin "4") (pinfunction "I4_4") (pintype "input"))
      (node (ref "U1") (pin "A15") (pinfunction "GPMC_AD14_A15") (pintype "bidirectional"))
    )
    (net (code "44") (name "/GPIO1_15") (class "Default")
      (node (ref "IC2") (pin "5") (pinfunction "I5_5") (pintype "input"))
      (node (ref "U1") (pin "C14") (pinfunction "GPMC_AD15_C14") (pintype "bidirectional"))
    )
    (net (code "45") (name "/GPIO1_16") (class "Default")
      (node (ref "U1") (pin "B14") (pinfunction "GPMC_CSN3_B14") (pintype "bidirectional"))
    )
    (net (code "46") (name "/GPIO1_17") (class "Default")
      (node (ref "IC2") (pin "1") (pinfunction "I1_1") (pintype "input"))
      (node (ref "U1") (pin "B13") (pinfunction "GPMC_A1_B13") (pintype "bidirectional"))
    )
    (net (code "47") (name "/GPIO1_28") (class "Default")
      (node (ref "U1") (pin "C9") (pinfunction "GPMC_BEN1_C9") (pintype "bidirectional"))
    )
    (net (code "48") (name "/I2C0_SCL") (class "Default")
      (node (ref "R12") (pin "1") (pinfunction "1_1") (pintype "passive"))
      (node (ref "TP18") (pin "P$1") (pinfunction "TP_P$1") (pintype "bidirectional"))
      (node (ref "U1") (pin "U8") (pinfunction "PMIC_SCL_U8") (pintype "bidirectional"))
      (node (ref "U1") (pin "V8") (pinfunction "I2C0_SCL_V8") (pintype "bidirectional"))
      (node (ref "U16") (pin "29") (pinfunction "SM_CLK_29") (pintype "bidirectional"))
    )
    (net (code "49") (name "/I2C0_SDA") (class "Default")
      (node (ref "R13") (pin "1") (pinfunction "1_1") (pintype "passive"))
      (node (ref "TP17") (pin "P$1") (pinfunction "TP_P$1") (pintype "bidirectional"))
      (node (ref "U1") (pin "U7") (pinfunction "PMIC_SDA_U7") (pintype "bidirectional"))
      (node (ref "U1") (pin "V7") (pinfunction "I2C0_SDA_V7") (pintype "bidirectional"))
      (node (ref "U16") (pin "30") (pinfunction "SM_DAT_30") (pintype "bidirectional"))
    )
    (net (code "50") (name "/I2C2_SCL") (class "Default")
      (node (ref "R169") (pin "1") (pinfunction "1_1") (pintype "passive"))
      (node (ref "RTC1") (pin "8") (pinfunction "SCL_8") (pintype "bidirectional"))
      (node (ref "TP20") (pin "P$1") (pinfunction "TP_P$1") (pintype "bidirectional"))
      (node (ref "U1") (pin "Y8") (pinfunction "UART1_RTSN_Y8") (pintype "bidirectional"))
    )
    (net (code "51") (name "/I2C2_SDA") (class "Default")
      (node (ref "R170") (pin "1") (pinfunction "1_1") (pintype "passive"))
      (node (ref "RTC1") (pin "7") (pinfunction "SDA_7") (pintype "bidirectional"))
      (node (ref "TP19") (pin "P$1") (pinfunction "TP_P$1") (pintype "bidirectional"))
      (node (ref "U1") (pin "W8") (pinfunction "UART1_CTSN_W8") (pintype "bidirectional"))
    )
    (net (code "52") (name "/ISO_485_A") (class "Default")
      (node (ref "D405") (pin "1") (pinfunction "1_1") (pintype "passive"))
      (node (ref "F401") (pin "3") (pinfunction "3_3") (pintype "passive"))
      (node (ref "U40") (pin "11") (pinfunction "Y_11") (pintype "passive"))
      (node (ref "U40") (pin "14") (pinfunction "A_14") (pintype "passive"))
    )
    (net (code "53") (name "/ISO_485_B") (class "Default")
      (node (ref "D405") (pin "2") (pinfunction "2_2") (pintype "passive"))
      (node (ref "F402") (pin "3") (pinfunction "3_3") (pintype "passive"))
      (node (ref "U40") (pin "12") (pinfunction "Z_12") (pintype "passive"))
      (node (ref "U40") (pin "13") (pinfunction "B_13") (pintype "passive"))
    )
    (net (code "54") (name "/ISO_VCC") (class "Default")
      (node (ref "C402") (pin "1") (pinfunction "1_1") (pintype "passive"))
      (node (ref "C406") (pin "+") (pinfunction "+_+") (pintype "passive"))
      (node (ref "U40") (pin "16") (pinfunction "VCC2_16") (pintype "power_in"))
      (node (ref "VREG4") (pin "5") (pinfunction "VOUT_5") (pintype "output"))
    )
    (net (code "55") (name "/ISO_VIN") (class "Default")
      (node (ref "C403") (pin "1") (pinfunction "1_1") (pintype "passive"))
      (node (ref "C405") (pin "1") (pinfunction "1_1") (pintype "passive"))
      (node (ref "D403") (pin "C") (pinfunction "C_C") (pintype "passive"))
      (node (ref "D404") (pin "C") (pinfunction "C_C") (pintype "passive"))
      (node (ref "VREG4") (pin "1") (pinfunction "VIN_1") (pintype "input"))
      (node (ref "VREG4") (pin "3") (pinfunction "ON/~{OFF}_3") (pintype "passive"))
    )
    (net (code "56") (name "/JTAG_EMU0") (class "Default")
      (node (ref "R40") (pin "1") (pinfunction "1_1") (pintype "passive"))
      (node (ref "U1") (pin "V18") (pinfunction "EMU0_V18") (pintype "bidirectional"))
      (node (ref "X4") (pin "13") (pinfunction "EMU0_13") (pintype "bidirectional"))
    )
    (net (code "57") (name "/JTAG_EMU1") (class "Default")
      (node (ref "R41") (pin "1") (pinfunction "1_1") (pintype "passive"))
      (node (ref "U1") (pin "V19") (pinfunction "EMU1_V19") (pintype "bidirectional"))
      (node (ref "X4") (pin "14") (pinfunction "EMU1_14") (pintype "bidirectional"))
    )
    (net (code "58") (name "/JTAG_TCK") (class "Default")
      (node (ref "U1") (pin "Y19") (pinfunction "TCK_Y19") (pintype "bidirectional"))
      (node (ref "X4") (pin "11") (pinfunction "TCK_11") (pintype "bidirectional"))
      (node (ref "X4") (pin "9") (pinfunction "TCKRTN_9") (pintype "bidirectional"))
    )
    (net (code "59") (name "/JTAG_TDI") (class "Default")
      (node (ref "U1") (pin "Y18") (pinfunction "TDI_Y18") (pintype "bidirectional"))
      (node (ref "X4") (pin "3") (pinfunction "TDI_3") (pintype "bidirectional"))
    )
    (net (code "60") (name "/JTAG_TDO") (class "Default")
      (node (ref "U1") (pin "W18") (pinfunction "TDO_W18") (pintype "bidirectional"))
      (node (ref "X4") (pin "7") (pinfunction "TDO_7") (pintype "bidirectional"))
    )
    (net (code "61") (name "/JTAG_TMS") (class "Default")
      (node (ref "U1") (pin "W19") (pinfunction "TMS_W19") (pintype "bidirectional"))
      (node (ref "X4") (pin "1") (pinfunction "TMS_1") (pintype "bidirectional"))
    )
    (net (code "62") (name "/JTAG_TRSTN") (class "Default")
      (node (ref "R39") (pin "2") (pinfunction "2_2") (pintype "passive"))
      (node (ref "U1") (pin "W20") (pinfunction "TRSTN_W20") (pintype "bidirectional"))
      (node (ref "X4") (pin "2") (pinfunction "TRSTN_2") (pintype "bidirectional"))
    )
    (net (code "63") (name "/LCD_DATA0") (class "Default")
      (node (ref "R68") (pin "2") (pinfunction "2_2") (pintype "passive"))
      (node (ref "R85") (pin "1") (pinfunction "1_1") (pintype "passive"))
      (node (ref "U1") (pin "T18") (pinfunction "LCD_DATA0_T18") (pintype "bidirectional"))
      (node (ref "X7") (pin "19") (pinfunction "19_19") (pintype "bidirectional"))
    )
    (net (code "64") (name "/LCD_DATA1") (class "Default")
      (node (ref "R67") (pin "2") (pinfunction "2_2") (pintype "passive"))
      (node (ref "R84") (pin "1") (pinfunction "1_1") (pintype "passive"))
      (node (ref "U1") (pin "T19") (pinfunction "LCD_DATA1_T19") (pintype "bidirectional"))
      (node (ref "X7") (pin "20") (pinfunction "20_20") (pintype "bidirectional"))
    )
    (net (code "65") (name "/LCD_DATA2") (class "Default")
      (node (ref "R66") (pin "2") (pinfunction "2_2") (pintype "passive"))
      (node (ref "R69") (pin "1") (pinfunction "1_1") (pintype "passive"))
      (node (ref "R83") (pin "1") (pinfunction "1_1") (pintype "passive"))
      (node (ref "U1") (pin "T20") (pinfunction "LCD_DATA2_T20") (pintype "bidirectional"))
      (node (ref "X7") (pin "17") (pinfunction "17_17") (pintype "bidirectional"))
    )
    (net (code "66") (name "/LCD_DATA3") (class "Default")
      (node (ref "R65") (pin "2") (pinfunction "2_2") (pintype "passive"))
      (node (ref "R82") (pin "1") (pinfunction "1_1") (pintype "passive"))
      (node (ref "U1") (pin "R18") (pinfunction "LCD_DATA3_R18") (pintype "bidirectional"))
      (node (ref "X7") (pin "18") (pinfunction "18_18") (pintype "bidirectional"))
    )
    (net (code "67") (name "/LCD_DATA4") (class "Default")
      (node (ref "R64") (pin "2") (pinfunction "2_2") (pintype "passive"))
      (node (ref "R81") (pin "1") (pinfunction "1_1") (pintype "passive"))
      (node (ref "U1") (pin "R19") (pinfunction "LCD_DATA4_R19") (pintype "bidirectional"))
      (node (ref "X7") (pin "15") (pinfunction "15_15") (pintype "bidirectional"))
    )
    (net (code "68") (name "/LCD_DATA5") (class "Default")
      (node (ref "R63") (pin "2") (pinfunction "2_2") (pintype "passive"))
      (node (ref "R80") (pin "1") (pinfunction "1_1") (pintype "passive"))
      (node (ref "U1") (pin "R20") (pinfunction "LCD_DATA5_R20") (pintype "bidirectional"))
      (node (ref "X7") (pin "16") (pinfunction "16_16") (pintype "bidirectional"))
    )
    (net (code "69") (name "/LCD_DATA6") (class "Default")
      (node (ref "R62") (pin "2") (pinfunction "2_2") (pintype "passive"))
      (node (ref "R79") (pin "1") (pinfunction "1_1") (pintype "passive"))
      (node (ref "U1") (pin "P18") (pinfunction "LCD_DATA6_P18") (pintype "bidirectional"))
      (node (ref "X7") (pin "13") (pinfunction "13_13") (pintype "bidirectional"))
    )
    (net (code "70") (name "/LCD_DATA7") (class "Default")
      (node (ref "R61") (pin "2") (pinfunction "2_2") (pintype "passive"))
      (node (ref "R78") (pin "1") (pinfunction "1_1") (pintype "passive"))
      (node (ref "U1") (pin "P19") (pinfunction "LCD_DATA7_P19") (pintype "bidirectional"))
      (node (ref "X7") (pin "14") (pinfunction "14_14") (pintype "bidirectional"))
    )
    (net (code "71") (name "/LCD_DATA8") (class "Default")
      (node (ref "R60") (pin "2") (pinfunction "2_2") (pintype "passive"))
      (node (ref "R77") (pin "1") (pinfunction "1_1") (pintype "passive"))
      (node (ref "U1") (pin "P20") (pinfunction "LCD_DATA8_P20") (pintype "bidirectional"))
      (node (ref "X7") (pin "11") (pinfunction "11_11") (pintype "bidirectional"))
    )
    (net (code "72") (name "/LCD_DATA9") (class "Default")
      (node (ref "R59") (pin "2") (pinfunction "2_2") (pintype "passive"))
      (node (ref "R76") (pin "1") (pinfunction "1_1") (pintype "passive"))
      (node (ref "U1") (pin "N18") (pinfunction "LCD_DATA9_N18") (pintype "bidirectional"))
      (node (ref "X7") (pin "12") (pinfunction "12_12") (pintype "bidirectional"))
    )
    (net (code "73") (name "/LCD_DATA10") (class "Default")
      (node (ref "R58") (pin "2") (pinfunction "2_2") (pintype "passive"))
      (node (ref "R75") (pin "1") (pinfunction "1_1") (pintype "passive"))
      (node (ref "U1") (pin "N19") (pinfunction "LCD_DATA10_N19") (pintype "bidirectional"))
      (node (ref "X7") (pin "10") (pinfunction "10_10") (pintype "bidirectional"))
    )
    (net (code "74") (name "/LCD_DATA11") (class "Default")
      (node (ref "R57") (pin "2") (pinfunction "2_2") (pintype "passive"))
      (node (ref "R74") (pin "1") (pinfunction "1_1") (pintype "passive"))
      (node (ref "U1") (pin "N20") (pinfunction "LCD_DATA11_N20") (pintype "bidirectional"))
      (node (ref "X7") (pin "8") (pinfunction "8_8") (pintype "bidirectional"))
    )
    (net (code "75") (name "/LCD_DATA12") (class "Default")
      (node (ref "R56") (pin "2") (pinfunction "2_2") (pintype "passive"))
      (node (ref "R73") (pin "1") (pinfunction "1_1") (pintype "passive"))
      (node (ref "U1") (pin "M18") (pinfunction "LCD_DATA12_M18") (pintype "bidirectional"))
      (node (ref "X7") (pin "9") (pinfunction "9_9") (pintype "bidirectional"))
    )
    (net (code "76") (name "/LCD_DATA13") (class "Default")
      (node (ref "R55") (pin "2") (pinfunction "2_2") (pintype "passive"))
      (node (ref "R72") (pin "1") (pinfunction "1_1") (pintype "passive"))
      (node (ref "U1") (pin "M19") (pinfunction "LCD_DATA13_M19") (pintype "bidirectional"))
      (node (ref "X7") (pin "7") (pinfunction "7_7") (pintype "bidirectional"))
    )
    (net (code "77") (name "/LCD_DATA14") (class "Default")
      (node (ref "R54") (pin "2") (pinfunction "2_2") (pintype "passive"))
      (node (ref "R71") (pin "1") (pinfunction "1_1") (pintype "passive"))
      (node (ref "U1") (pin "M20") (pinfunction "LCD_DATA14_M20") (pintype "bidirectional"))
      (node (ref "X7") (pin "5") (pinfunction "5_5") (pintype "bidirectional"))
    )
    (net (code "78") (name "/LCD_DATA15") (class "Default")
      (node (ref "R53") (pin "2") (pinfunction "2_2") (pintype "passive"))
      (node (ref "R70") (pin "1") (pinfunction "1_1") (pintype "passive"))
      (node (ref "U1") (pin "L18") (pinfunction "LCD_DATA15_L18") (pintype "bidirectional"))
      (node (ref "X7") (pin "6") (pinfunction "6_6") (pintype "bidirectional"))
    )
    (net (code "79") (name "/LCD_DE") (class "Default")
      (node (ref "R28") (pin "2") (pinfunction "2_2") (pintype "passive"))
      (node (ref "X7") (pin "4") (pinfunction "4_4") (pintype "bidirectional"))
    )
    (net (code "80") (name "/LCD_HSYNC") (class "Default")
      (node (ref "R29") (pin "2") (pinfunction "2_2") (pintype "passive"))
      (node (ref "X7") (pin "3") (pinfunction "3_3") (pintype "bidirectional"))
    )
    (net (code "81") (name "/LCD_PCLK") (class "Default")
      (node (ref "R31") (pin "2") (pinfunction "2_2") (pintype "passive"))
      (node (ref "X7") (pin "2") (pinfunction "2_2") (pintype "bidirectional"))
    )
    (net (code "82") (name "/LCD_VSYNC") (class "Default")
      (node (ref "R30") (pin "2") (pinfunction "2_2") (pintype "passive"))
      (node (ref "X7") (pin "1") (pinfunction "1_1") (pintype "bidirectional"))
    )
    (net (code "83") (name "/LDO_PGOOD") (class "Default")
      (node (ref "TP22") (pin "TP") (pinfunction "TP_TP") (pintype "input"))
      (node (ref "U1") (pin "D13") (pinfunction "RTC_PWRONRSTN_D13") (pintype "bidirectional"))
      (node (ref "U1") (pin "D14") (pinfunction "PMIC_LDO_PGOOD_D14") (pintype "output"))
    )
    (net (code "84") (name "/MDIO_CLK") (class "Default")
      (node (ref "U1") (pin "W1") (pinfunction "MDC_W1") (pintype "bidirectional"))
      (node (ref "U27") (pin "17") (pinfunction "MDC_17") (pintype "input"))
    )
    (net (code "85") (name "/MDIO_DATA") (class "Default")
      (node (ref "ER105") (pin "2") (pinfunction "2_2") (pintype "passive"))
      (node (ref "U1") (pin "V1") (pinfunction "MDIO_V1") (pintype "bidirectional"))
      (node (ref "U27") (pin "16") (pinfunction "MDIO_16") (pintype "bidirectional"))
    )
    (net (code "86") (name "/MII1_COL") (class "Default")
      (node (ref "ER123") (pin "2") (pinfunction "2_2") (pintype "passive"))
      (node (ref "U1") (pin "R2") (pinfunction "MII1_COL_R2") (pintype "bidirectional"))
    )
    (net (code "87") (name "/MII1_CRS") (class "Default")
      (node (ref "ER124") (pin "2") (pinfunction "2_2") (pintype "passive"))
      (node (ref "U1") (pin "R3") (pinfunction "MII1_CRS_R3") (pintype "bidirectional"))
    )
    (net (code "88") (name "/MII1_RXCLK") (class "Default")
      (node (ref "ER116") (pin "2") (pinfunction "2_2") (pintype "passive"))
      (node (ref "U1") (pin "T1") (pinfunction "MII1_RX_CLK_T1") (pintype "bidirectional"))
    )
    (net (code "89") (name "/MII1_RXD0") (class "Default")
      (node (ref "ER113") (pin "2") (pinfunction "2_2") (pintype "passive"))
      (node (ref "U1") (pin "T3") (pinfunction "MII1_RXD0_T3") (pintype "bidirectional"))
    )
    (net (code "90") (name "/MII1_RXD1") (class "Default")
      (node (ref "ER112") (pin "2") (pinfunction "2_2") (pintype "passive"))
      (node (ref "U1") (pin "U1") (pinfunction "MII1_RXD1_U1") (pintype "bidirectional"))
    )
    (net (code "91") (name "/MII1_RXD2") (class "Default")
      (node (ref "ER111") (pin "2") (pinfunction "2_2") (pintype "passive"))
      (node (ref "U1") (pin "U2") (pinfunction "MII1_RXD2_U2") (pintype "bidirectional"))
    )
    (net (code "92") (name "/MII1_RXD3") (class "Default")
      (node (ref "ER110") (pin "2") (pinfunction "2_2") (pintype "passive"))
      (node (ref "U1") (pin "U3") (pinfunction "MII1_RXD3_U3") (pintype "bidirectional"))
    )
    (net (code "93") (name "/MII1_RXDV") (class "Default")
      (node (ref "ER114") (pin "2") (pinfunction "2_2") (pintype "passive"))
      (node (ref "U1") (pin "R1") (pinfunction "MII1_RX_DV_R1") (pintype "bidirectional"))
    )
    (net (code "94") (name "/MII1_RXERR") (class "Default")
      (node (ref "ER118") (pin "2") (pinfunction "2_2") (pintype "passive"))
      (node (ref "U1") (pin "T2") (pinfunction "MII1_RX_ER_T2") (pintype "bidirectional"))
    )
    (net (code "95") (name "/MII1_TXCLK") (class "Default")
      (node (ref "ER119") (pin "2") (pinfunction "2_2") (pintype "passive"))
      (node (ref "U1") (pin "N1") (pinfunction "MII1_TX_CLK_N1") (pintype "bidirectional"))
    )
    (net (code "96") (name "/MII1_TXD0") (class "Default")
      (node (ref "U1") (pin "N2") (pinfunction "MII1_TXD0_N2") (pintype "bidirectional"))
      (node (ref "U27") (pin "22") (pinfunction "TXD0_22") (pintype "input"))
    )
    (net (code "97") (name "/MII1_TXD1") (class "Default")
      (node (ref "U1") (pin "N3") (pinfunction "MII1_TXD1_N3") (pintype "bidirectional"))
      (node (ref "U27") (pin "23") (pinfunction "TXD1_23") (pintype "input"))
    )
    (net (code "98") (name "/MII1_TXD2") (class "Default")
      (node (ref "U1") (pin "P1") (pinfunction "MII1_TXD2_P1") (pintype "bidirectional"))
      (node (ref "U27") (pin "24") (pinfunction "TXD2_24") (pintype "input"))
    )
    (net (code "99") (name "/MII1_TXD3") (class "Default")
      (node (ref "U1") (pin "P2") (pinfunction "MII1_TXD3_P2") (pintype "bidirectional"))
      (node (ref "U27") (pin "25") (pinfunction "TXD3_25") (pintype "input"))
    )
    (net (code "100") (name "/MII1_TXEN") (class "Default")
      (node (ref "U1") (pin "P3") (pinfunction "MII1_TX_EN_P3") (pintype "bidirectional"))
      (node (ref "U27") (pin "21") (pinfunction "TXEN_21") (pintype "input"))
    )
    (net (code "101") (name "/MMC0_CD") (class "Default")
      (node (ref "R92") (pin "1") (pinfunction "1_1") (pintype "passive"))
      (node (ref "U1") (pin "V4") (pinfunction "SPI0_CS1_V4") (pintype "bidirectional"))
      (node (ref "X4") (pin "19") (pinfunction "EMU4_19") (pintype "bidirectional"))
      (node (ref "X5") (pin "12") (pinfunction "CARD_DETECTION_SWITCH_12") (pintype "bidirectional"))
    )
    (net (code "102") (name "/MMC0_CLK") (class "Default")
      (node (ref "R88") (pin "1") (pinfunction "1_1") (pintype "passive"))
      (node (ref "U1") (pin "W3") (pinfunction "MMC0_CLK_W3") (pintype "bidirectional"))
      (node (ref "X5") (pin "5") (pinfunction "CLK_5") (pintype "bidirectional"))
    )
    (net (code "103") (name "/MMC0_CMD") (class "Default")
      (node (ref "R87") (pin "1") (pinfunction "1_1") (pintype "passive"))
      (node (ref "U1") (pin "W2") (pinfunction "MMC0_CMD_W2") (pintype "bidirectional"))
      (node (ref "X5") (pin "3") (pinfunction "CMD_3") (pintype "bidirectional"))
    )
    (net (code "104") (name "/MMC0_DAT0") (class "Default")
      (node (ref "R89") (pin "1") (pinfunction "1_1") (pintype "passive"))
      (node (ref "U1") (pin "Y3") (pinfunction "MMC0_DAT0_Y3") (pintype "bidirectional"))
      (node (ref "X5") (pin "7") (pinfunction "DAT0_7") (pintype "bidirectional"))
    )
    (net (code "105") (name "/MMC0_DAT1") (class "Default")
      (node (ref "R90") (pin "1") (pinfunction "1_1") (pintype "passive"))
      (node (ref "U1") (pin "V3") (pinfunction "MMC0_DAT1_V3") (pintype "bidirectional"))
      (node (ref "X5") (pin "8") (pinfunction "DAT1_8") (pintype "bidirectional"))
    )
    (net (code "106") (name "/MMC0_DAT2") (class "Default")
      (node (ref "R86") (pin "1") (pinfunction "1_1") (pintype "passive"))
      (node (ref "U1") (pin "V2") (pinfunction "MMC0_DAT2_V2") (pintype "bidirectional"))
      (node (ref "X5") (pin "1") (pinfunction "DAT2_1") (pintype "bidirectional"))
    )
    (net (code "107") (name "/MMC0_DAT3") (class "Default")
      (node (ref "R91") (pin "1") (pinfunction "1_1") (pintype "passive"))
      (node (ref "U1") (pin "Y2") (pinfunction "MMC0_DAT3_Y2") (pintype "bidirectional"))
      (node (ref "X5") (pin "2") (pinfunction "CD/DAT3_2") (pintype "bidirectional"))
    )
    (net (code "108") (name "/MODE2") (class "Default")
      (node (ref "ER123") (pin "1") (pinfunction "1_1") (pintype "passive"))
      (node (ref "ER99") (pin "2") (pinfunction "2_2") (pintype "passive"))
      (node (ref "U27") (pin "15") (pinfunction "COL/CRS_DV/MODE2_15") (pintype "bidirectional"))
    )
    (net (code "109") (name "/OSC1_IN") (class "Default")
      (node (ref "R164") (pin "2") (pinfunction "2_2") (pintype "passive"))
      (node (ref "RTC1") (pin "1") (pinfunction "32KHZ_1") (pintype "output"))
      (node (ref "U1") (pin "Y13") (pinfunction "OSC1_IN_Y13") (pintype "bidirectional"))
    )
    (net (code "110") (name "/OSC1_OUT") (class "Default")
      (node (ref "U1") (pin "Y14") (pinfunction "OSC1_OUT_Y14") (pintype "bidirectional"))
    )
    (net (code "111") (name "/OSC_CTL") (class "Default")
      (node (ref "TP32") (pin "TP") (pinfunction "TP_TP") (pintype "input"))
      (node (ref "U1") (pin "M1") (pinfunction "OSC0_CTL_M1") (pintype "bidirectional"))
    )
    (net (code "112") (name "/PMIC_INT") (class "Default")
      (node (ref "TP24") (pin "TP") (pinfunction "TP_TP") (pintype "input"))
      (node (ref "U1") (pin "J17") (pinfunction "PMIC_NINT_J17") (pintype "output"))
      (node (ref "U1") (pin "K17") (pinfunction "EXTINTN_K17") (pintype "bidirectional"))
    )
    (net (code "113") (name "/PMIC_MUX_IN") (class "Default")
      (node (ref "R18") (pin "2") (pinfunction "2_2") (pintype "passive"))
      (node (ref "R22") (pin "1") (pinfunction "1_1") (pintype "passive"))
      (node (ref "U1") (pin "F19") (pinfunction "PMIC_MUX_IN_F19") (pintype "bidirectional"))
    )
    (net (code "114") (name "/PMIC_NRESET") (class "Default")
      (node (ref "J2") (pin "1") (pinfunction "1_1") (pintype "bidirectional"))
      (node (ref "U1") (pin "A19") (pinfunction "PMIC_NRESET_A19") (pintype "bidirectional"))
    )
    (net (code "115") (name "/PMIC_NWAKEUP") (class "Default")
      (node (ref "TP23") (pin "TP") (pinfunction "TP_TP") (pintype "input"))
      (node (ref "U1") (pin "G17") (pinfunction "PMIC_NWAKEUP_G17") (pintype "output"))
      (node (ref "U1") (pin "H17") (pinfunction "EXT_WAKEUP_H17") (pintype "bidirectional"))
    )
    (net (code "116") (name "/PMIC_PGOOD") (class "Default")
      (node (ref "TP26") (pin "TP") (pinfunction "TP_TP") (pintype "input"))
      (node (ref "U1") (pin "D11") (pinfunction "PWRONRSTN_D11") (pintype "bidirectional"))
      (node (ref "U1") (pin "D12") (pinfunction "PMIC_PGOOD_D12") (pintype "output"))
    )
    (net (code "117") (name "/PR1_PRU0_PRU_R30_6") (class "Default")
      (node (ref "U1") (pin "V17") (pinfunction "MCASP0_AXR1_V17") (pintype "bidirectional"))
      (node (ref "U40") (pin "6") (pinfunction "~{RE}_6") (pintype "passive"))
    )
    (net (code "118") (name "/PR1_PRU0_PRU_R30_7") (class "Default")
      (node (ref "U1") (pin "V16") (pinfunction "MCASP0_AHCLKX_V16") (pintype "bidirectional"))
      (node (ref "U40") (pin "7") (pinfunction "DE_7") (pintype "passive"))
    )
    (net (code "119") (name "/PR1_UART0_RXD") (class "Default")
      (node (ref "J450") (pin "1") (pinfunction "1_1") (pintype "bidirectional"))
      (node (ref "U1") (pin "W4") (pinfunction "SPI0_D1_W4") (pintype "bidirectional"))
    )
    (net (code "120") (name "/PR1_UART0_TXD") (class "Default")
      (node (ref "J450") (pin "2") (pinfunction "2_2") (pintype "bidirectional"))
      (node (ref "U1") (pin "Y4") (pinfunction "SPI0_CS0_Y4") (pintype "bidirectional"))
    )
    (net (code "121") (name "/PWR_BUT") (class "Default")
      (node (ref "S2") (pin "2") (pinfunction "2_2") (pintype "bidirectional"))
      (node (ref "S2") (pin "4") (pinfunction "4_4") (pintype "bidirectional"))
      (node (ref "U1") (pin "A18") (pinfunction "PMIC_PB_IN_A18") (pintype "bidirectional"))
    )
    (net (code "122") (name "/PWR_EN") (class "Default")
      (node (ref "TP21") (pin "TP") (pinfunction "TP_TP") (pintype "input"))
      (node (ref "U1") (pin "D10") (pinfunction "PMIC_PWR_EN_D10") (pintype "input"))
      (node (ref "U1") (pin "D9") (pinfunction "PMIC_POWER_EN_D9") (pintype "output"))
    )
    (net (code "123") (name "/RTC_RST") (class "Default")
      (node (ref "R163") (pin "1") (pinfunction "1_1") (pintype "passive"))
      (node (ref "RTC1") (pin "4") (pinfunction "RST_4") (pintype "bidirectional"))
      (node (ref "U1") (pin "K20") (pinfunction "GPMC_CSN0_K20") (pintype "bidirectional"))
    )
    (net (code "124") (name "/RXD0") (class "Default")
      (node (ref "ER113") (pin "1") (pinfunction "1_1") (pintype "passive"))
      (node (ref "ER98") (pin "2") (pinfunction "2_2") (pintype "passive"))
      (node (ref "U27") (pin "11") (pinfunction "RXD0/MODE0_11") (pintype "bidirectional"))
    )
    (net (code "125") (name "/RXD1") (class "Default")
      (node (ref "ER100") (pin "2") (pinfunction "2_2") (pintype "passive"))
      (node (ref "ER112") (pin "1") (pinfunction "1_1") (pintype "passive"))
      (node (ref "U27") (pin "10") (pinfunction "RXD1/MODE1_10") (pintype "bidirectional"))
    )
    (net (code "126") (name "/RXD2") (class "Default")
      (node (ref "ER103") (pin "1") (pinfunction "1_1") (pintype "passive"))
      (node (ref "ER111") (pin "1") (pinfunction "1_1") (pintype "passive"))
      (node (ref "U27") (pin "9") (pinfunction "RXD2/RMIISEL_9") (pintype "bidirectional"))
    )
    (net (code "127") (name "/RXD3") (class "Default")
      (node (ref "ER102") (pin "1") (pinfunction "1_1") (pintype "passive"))
      (node (ref "ER110") (pin "1") (pinfunction "1_1") (pintype "passive"))
      (node (ref "U27") (pin "8") (pinfunction "RXD3/PHYAD2_8") (pintype "bidirectional"))
    )
    (net (code "128") (name "/RX_CLK") (class "Default")
      (node (ref "ER104") (pin "1") (pinfunction "1_1") (pintype "passive"))
      (node (ref "ER116") (pin "1") (pinfunction "1_1") (pintype "passive"))
      (node (ref "U27") (pin "7") (pinfunction "RXCLK/PHYAD1_7") (pintype "bidirectional"))
    )
    (net (code "129") (name "/RX_DV") (class "Default")
      (node (ref "ER114") (pin "1") (pinfunction "1_1") (pintype "passive"))
      (node (ref "U27") (pin "26") (pinfunction "RXDV_26") (pintype "bidirectional"))
    )
    (net (code "130") (name "/RX_ERR") (class "Default")
      (node (ref "ER101") (pin "1") (pinfunction "1_1") (pintype "passive"))
      (node (ref "ER118") (pin "1") (pinfunction "1_1") (pintype "passive"))
      (node (ref "U27") (pin "13") (pinfunction "RXER/RXD4/PHYAD0_13") (pintype "bidirectional"))
    )
    (net (code "131") (name "/RX_N") (class "Default")
      (node (ref "EC37") (pin "1") (pinfunction "1_1") (pintype "passive"))
      (node (ref "ER107") (pin "2") (pinfunction "2_2") (pintype "passive"))
      (node (ref "U27") (pin "30") (pinfunction "RXN_30") (pintype "bidirectional"))
      (node (ref "X2") (pin "6") (pinfunction "RXN_6") (pintype "passive"))
    )
    (net (code "132") (name "/RX_P") (class "Default")
      (node (ref "EC36") (pin "1") (pinfunction "1_1") (pintype "passive"))
      (node (ref "ER106") (pin "2") (pinfunction "2_2") (pintype "passive"))
      (node (ref "U27") (pin "31") (pinfunction "RXP_31") (pintype "bidirectional"))
      (node (ref "X2") (pin "3") (pinfunction "RXP_3") (pintype "passive"))
    )
    (net (code "133") (name "/SPI1_CS0") (class "Default")
      (node (ref "IC4") (pin "1") (pinfunction "SH/~{LD}_1") (pintype "input"))
      (node (ref "IC5") (pin "1") (pinfunction "SH/~{LD}_1") (pintype "input"))
      (node (ref "U1") (pin "W17") (pinfunction "MCASP0_AHCLKR_W17") (pintype "bidirectional"))
    )
    (net (code "134") (name "/SPI1_D0") (class "Default")
      (node (ref "IC4") (pin "9") (pinfunction "QH_9") (pintype "output"))
      (node (ref "U1") (pin "Y16") (pinfunction "MCASP0_FSX_Y16") (pintype "bidirectional"))
    )
    (net (code "135") (name "/SPI1_D1") (class "Default")
      (node (ref "U1") (pin "W16") (pinfunction "MCASP0_AXR0_W16") (pintype "bidirectional"))
    )
    (net (code "136") (name "/SPI1_SCLK") (class "Default")
      (node (ref "IC4") (pin "2") (pinfunction "CLK_2") (pintype "input"))
      (node (ref "IC5") (pin "2") (pinfunction "CLK_2") (pintype "input"))
      (node (ref "U1") (pin "Y17") (pinfunction "MCASP0_ACLKX_Y17") (pintype "bidirectional"))
    )
    (net (code "137") (name "/SYS_RESETN") (class "Default")
      (node (ref "C14") (pin "1") (pinfunction "1_1") (pintype "passive"))
      (node (ref "R6") (pin "2") (pinfunction "2_2") (pintype "passive"))
      (node (ref "R8") (pin "1") (pinfunction "1_1") (pintype "passive"))
      (node (ref "TP31") (pin "TP") (pinfunction "TP_TP") (pintype "input"))
      (node (ref "U1") (pin "B17") (pinfunction "WARMRSTN_B17") (pintype "bidirectional"))
      (node (ref "U16") (pin "17") (pinfunction "LRESET#_17") (pintype "bidirectional"))
      (node (ref "U27") (pin "19") (pinfunction "~{RST}_19") (pintype "bidirectional"))
      (node (ref "X4") (pin "15") (pinfunction "SRST_15") (pintype "bidirectional"))
    )
    (net (code "138") (name "/TEMP_SENSE") (class "Default")
      (node (ref "TP7") (pin "P$1") (pinfunction "TP_P$1") (pintype "bidirectional"))
      (node (ref "U1") (pin "E20") (pinfunction "PMIC_TS_E20") (pintype "bidirectional"))
    )
    (net (code "139") (name "/TPM_GPIO0") (class "Default")
      (node (ref "U1") (pin "W15") (pinfunction "MCASP0_FSR_W15") (pintype "bidirectional"))
      (node (ref "U16") (pin "12") (pinfunction "GPIO_12") (pintype "bidirectional"))
    )
    (net (code "140") (name "/TPM_GPIO1") (class "Default")
      (node (ref "TP9") (pin "P$1") (pinfunction "TP_P$1") (pintype "bidirectional"))
      (node (ref "U1") (pin "V6") (pinfunction "UART0_CTSN_V6") (pintype "bidirectional"))
      (node (ref "U16") (pin "3") (pinfunction "GPIO-EXPRESS-00_3") (pintype "bidirectional"))
    )
    (net (code "141") (name "/TPM_GPIO2") (class "Default")
      (node (ref "TP10") (pin "P$1") (pinfunction "TP_P$1") (pintype "bidirectional"))
      (node (ref "U1") (pin "V5") (pinfunction "UART0_RTSN_V5") (pintype "bidirectional"))
      (node (ref "U16") (pin "4") (pinfunction "PP/GPIO_4") (pintype "bidirectional"))
    )
    (net (code "142") (name "/TX_CLK") (class "Default")
      (node (ref "ER119") (pin "1") (pinfunction "1_1") (pintype "passive"))
      (node (ref "U27") (pin "20") (pinfunction "TXCLK_20") (pintype "bidirectional"))
    )
    (net (code "143") (name "/TX_N") (class "Default")
      (node (ref "EC39") (pin "1") (pinfunction "1_1") (pintype "passive"))
      (node (ref "ER109") (pin "2") (pinfunction "2_2") (pintype "passive"))
      (node (ref "U27") (pin "28") (pinfunction "TXN_28") (pintype "bidirectional"))
      (node (ref "X2") (pin "2") (pinfunction "TXN_2") (pintype "passive"))
    )
    (net (code "144") (name "/TX_P") (class "Default")
      (node (ref "EC38") (pin "1") (pinfunction "1_1") (pintype "passive"))
      (node (ref "ER108") (pin "2") (pinfunction "2_2") (pintype "passive"))
      (node (ref "U27") (pin "29") (pinfunction "TXP_29") (pintype "bidirectional"))
      (node (ref "X2") (pin "1") (pinfunction "TXP_1") (pintype "passive"))
    )
    (net (code "145") (name "/UART0_RX") (class "Default")
      (node (ref "U1") (pin "Y6") (pinfunction "UART0_RXD_Y6") (pintype "bidirectional"))
      (node (ref "U6") (pin "6") (pinfunction "1Y_6") (pintype "output"))
    )
    (net (code "146") (name "/UART0_TX") (class "Default")
      (node (ref "U1") (pin "W6") (pinfunction "UART0_TXD_W6") (pintype "bidirectional"))
      (node (ref "U6") (pin "5") (pinfunction "2A_5") (pintype "input"))
    )
    (net (code "147") (name "/UART2_RXD") (class "Default")
      (node (ref "D302") (pin "1") (pinfunction "A_1") (pintype "passive"))
      (node (ref "U1") (pin "Y5") (pinfunction "SPI0_SCLK_Y5") (pintype "bidirectional"))
      (node (ref "U29") (pin "1") (pinfunction "RO_1") (pintype "output"))
    )
    (net (code "148") (name "/UART2_TXD") (class "Default")
      (node (ref "D301") (pin "1") (pinfunction "A_1") (pintype "passive"))
      (node (ref "U1") (pin "W5") (pinfunction "SPI0_D0_W5") (pintype "bidirectional"))
      (node (ref "U29") (pin "4") (pinfunction "DI_4") (pintype "input"))
    )
    (net (code "149") (name "/UART4_RXD") (class "Default")
      (node (ref "J454") (pin "1") (pinfunction "1_1") (pintype "bidirectional"))
      (node (ref "U1") (pin "B9") (pinfunction "GPMC_WAIT0_B9") (pintype "bidirectional"))
    )
    (net (code "150") (name "/UART4_TXD") (class "Default")
      (node (ref "J454") (pin "2") (pinfunction "2_2") (pintype "bidirectional"))
      (node (ref "U1") (pin "A9") (pinfunction "GPMC_WPN_A9") (pintype "bidirectional"))
    )
    (net (code "151") (name "/USB0_ID") (class "Default")
      (node (ref "U1") (pin "L1") (pinfunction "USB0_ID_L1") (pintype "bidirectional"))
      (node (ref "U2") (pin "3") (pinfunction "ID_3") (pintype "passive"))
      (node (ref "X1") (pin "ID") (pinfunction "ID_ID") (pintype "input"))
    )
    (net (code "152") (name "/USB0_N") (class "Default")
      (node (ref "U1") (pin "K2") (pinfunction "USB0_DM_K2") (pintype "bidirectional"))
      (node (ref "U2") (pin "1") (pinfunction "D-_1") (pintype "passive"))
      (node (ref "X1") (pin "D-") (pinfunction "D-_D-") (pintype "input"))
    )
    (net (code "153") (name "/USB0_P") (class "Default")
      (node (ref "U1") (pin "L2") (pinfunction "USB0_DP_L2") (pintype "bidirectional"))
      (node (ref "U2") (pin "2") (pinfunction "D+_2") (pintype "passive"))
      (node (ref "X1") (pin "D+") (pinfunction "D+_D+") (pintype "input"))
    )
    (net (code "154") (name "/USR0") (class "Default")
      (node (ref "D7") (pin "1") (pinfunction "A_1") (pintype "passive"))
      (node (ref "U1") (pin "C12") (pinfunction "GPMC_A5_C12") (pintype "bidirectional"))
    )
    (net (code "155") (name "/USR1") (class "Default")
      (node (ref "D6") (pin "1") (pinfunction "A_1") (pintype "passive"))
      (node (ref "U1") (pin "A11") (pinfunction "GPMC_A6_A11") (pintype "bidirectional"))
    )
    (net (code "156") (name "/USR2") (class "Default")
      (node (ref "D5") (pin "1") (pinfunction "A_1") (pintype "passive"))
      (node (ref "U1") (pin "B11") (pinfunction "GPMC_A7_B11") (pintype "bidirectional"))
    )
    (net (code "157") (name "/USR3") (class "Default")
      (node (ref "D4") (pin "1") (pinfunction "A_1") (pintype "passive"))
      (node (ref "U1") (pin "C11") (pinfunction "GPMC_A8_C11") (pintype "bidirectional"))
    )
    (net (code "158") (name "/VDDS_DDR") (class "Default")
      (node (ref "TP2") (pin "TP") (pinfunction "TP_TP") (pintype "input"))
      (node (ref "U1") (pin "U9") (pinfunction "VDDS_DDR_U9") (pintype "bidirectional"))
    )
    (net (code "159") (name "/VDDS_PLL") (class "Default")
      (node (ref "TP3") (pin "TP") (pinfunction "TP_TP") (pintype "input"))
      (node (ref "U1") (pin "U10") (pinfunction "VDDS_PLL_U10") (pintype "bidirectional"))
    )
    (net (code "160") (name "/VDD_CORE") (class "Default")
      (node (ref "TP4") (pin "TP") (pinfunction "TP_TP") (pintype "input"))
      (node (ref "U1") (pin "U13") (pinfunction "VDD_CORE_U13") (pintype "bidirectional"))
    )
    (net (code "161") (name "/VDD_MPU") (class "Default")
      (node (ref "TP1") (pin "TP") (pinfunction "TP_TP") (pintype "input"))
      (node (ref "U1") (pin "U6") (pinfunction "VDD_MPU_U6") (pintype "bidirectional"))
    )
    (net (code "162") (name "/VIO") (class "Default")
      (node (ref "U28") (pin "5") (pinfunction "VIO_5") (pintype "power_in"))
    )
    (net (code "163") (name "/VREFN") (class "Default")
      (node (ref "R25") (pin "1") (pinfunction "1_1") (pintype "passive"))
      (node (ref "U1") (pin "W9") (pinfunction "VREFN_W9") (pintype "bidirectional"))
    )
    (net (code "164") (name "/VREFP") (class "Default")
      (node (ref "C8") (pin "1") (pinfunction "1_1") (pintype "passive"))
      (node (ref "C9") (pin "1") (pinfunction "1_1") (pintype "passive"))
      (node (ref "R33") (pin "1") (pinfunction "1_1") (pintype "passive"))
      (node (ref "U1") (pin "W12") (pinfunction "VREFP_W12") (pintype "bidirectional"))
    )
    (net (code "165") (name "/XDMA_EVENT_INTR0") (class "Default")
      (node (ref "C1") (pin "2") (pinfunction "2_2") (pintype "passive"))
      (node (ref "R4") (pin "2") (pinfunction "2_2") (pintype "passive"))
      (node (ref "X4") (pin "17") (pinfunction "EMU2_17") (pintype "bidirectional"))
    )
    (net (code "166") (name "24VDC_AUX") (class "Default")
      (node (ref "C106") (pin "1") (pinfunction "1_1") (pintype "passive"))
      (node (ref "D19") (pin "1") (pinfunction "A_1") (pintype "passive"))
      (node (ref "D31") (pin "1") (pinfunction "A_1") (pintype "passive"))
      (node (ref "D32") (pin "1") (pinfunction "A_1") (pintype "passive"))
      (node (ref "D33") (pin "1") (pinfunction "A_1") (pintype "passive"))
      (node (ref "D34") (pin "1") (pinfunction "A_1") (pintype "passive"))
      (node (ref "D35") (pin "1") (pinfunction "A_1") (pintype "passive"))
      (node (ref "IC2") (pin "9") (pinfunction "CD+_9") (pintype "passive"))
      (node (ref "J24") (pin "3") (pinfunction "3_3") (pintype "bidirectional"))
      (node (ref "K1") (pin "1") (pinfunction "1_1") (pintype "passive"))
      (node (ref "K2") (pin "1") (pinfunction "1_1") (pintype "passive"))
      (node (ref "K3") (pin "1") (pinfunction "1_1") (pintype "passive"))
      (node (ref "K4") (pin "1") (pinfunction "1_1") (pintype "passive"))
      (node (ref "K5") (pin "1") (pinfunction "1_1") (pintype "passive"))
      (node (ref "VREG2") (pin "OUT") (pinfunction "OUT_OUT") (pintype "passive"))
      (node (ref "X21") (pin "12") (pinfunction "SK_12") (pintype "passive"))
      (node (ref "X8") (pin "4") (pinfunction "SK_4") (pintype "passive"))
    )
    (net (code "167") (name "AGND") (class "Default")
      (node (ref "C10") (pin "2") (pinfunction "2_2") (pintype "passive"))
      (node (ref "C111") (pin "2") (pinfunction "2_2") (pintype "passive"))
      (node (ref "C121") (pin "2") (pinfunction "2_2") (pintype "passive"))
      (node (ref "C131") (pin "2") (pinfunction "2_2") (pintype "passive"))
      (node (ref "C141") (pin "2") (pinfunction "2_2") (pintype "passive"))
      (node (ref "C151") (pin "2") (pinfunction "2_2") (pintype "passive"))
      (node (ref "C161") (pin "2") (pinfunction "2_2") (pintype "passive"))
      (node (ref "C8") (pin "2") (pinfunction "2_2") (pintype "passive"))
      (node (ref "C9") (pin "2") (pinfunction "2_2") (pintype "passive"))
      (node (ref "IC10") (pin "4") (pinfunction "V-_4") (pintype "power_in"))
      (node (ref "IC11") (pin "4") (pinfunction "V-_4") (pintype "power_in"))
      (node (ref "IC12") (pin "4") (pinfunction "V-_4") (pintype "power_in"))
      (node (ref "J7") (pin "1") (pinfunction "1_1") (pintype "bidirectional"))
      (node (ref "R181") (pin "2") (pinfunction "2_2") (pintype "passive"))
      (node (ref "R182") (pin "2") (pinfunction "2_2") (pintype "passive"))
      (node (ref "R183") (pin "2") (pinfunction "2_2") (pintype "passive"))
      (node (ref "R184") (pin "2") (pinfunction "2_2") (pintype "passive"))
      (node (ref "R185") (pin "2") (pinfunction "2_2") (pintype "passive"))
      (node (ref "R186") (pin "2") (pinfunction "2_2") (pintype "passive"))
      (node (ref "R211") (pin "1") (pinfunction "1_1") (pintype "passive"))
      (node (ref "R213") (pin "2") (pinfunction "2_2") (pintype "passive"))
      (node (ref "R215") (pin "2") (pinfunction "2_2") (pintype "passive"))
      (node (ref "R221") (pin "1") (pinfunction "1_1") (pintype "passive"))
      (node (ref "R223") (pin "2") (pinfunction "2_2") (pintype "passive"))
      (node (ref "R225") (pin "2") (pinfunction "2_2") (pintype "passive"))
      (node (ref "R231") (pin "1") (pinfunction "1_1") (pintype "passive"))
      (node (ref "R233") (pin "2") (pinfunction "2_2") (pintype "passive"))
      (node (ref "R235") (pin "2") (pinfunction "2_2") (pintype "passive"))
      (node (ref "R241") (pin "1") (pinfunction "1_1") (pintype "passive"))
      (node (ref "R243") (pin "2") (pinfunction "2_2") (pintype "passive"))
      (node (ref "R245") (pin "2") (pinfunction "2_2") (pintype "passive"))
      (node (ref "R25") (pin "2") (pinfunction "2_2") (pintype "passive"))
      (node (ref "R251") (pin "1") (pinfunction "1_1") (pintype "passive"))
      (node (ref "R253") (pin "2") (pinfunction "2_2") (pintype "passive"))
      (node (ref "R255") (pin "2") (pinfunction "2_2") (pintype "passive"))
      (node (ref "R261") (pin "1") (pinfunction "1_1") (pintype "passive"))
      (node (ref "R263") (pin "2") (pinfunction "2_2") (pintype "passive"))
      (node (ref "R265") (pin "2") (pinfunction "2_2") (pintype "passive"))
      (node (ref "U1") (pin "Y9") (pinfunction "AGND_ADC_Y9") (pintype "bidirectional"))
      (node (ref "X10") (pin "2") (pinfunction "SK_2") (pintype "passive"))
      (node (ref "X10") (pin "4") (pinfunction "SK_4") (pintype "passive"))
      (node (ref "X11") (pin "2") (pinfunction "SK_2") (pintype "passive"))
      (node (ref "X11") (pin "4") (pinfunction "SK_4") (pintype "passive"))
      (node (ref "X12") (pin "2") (pinfunction "SK_2") (pintype "passive"))
      (node (ref "X12") (pin "4") (pinfunction "SK_4") (pintype "passive"))
    )
    (net (code "168") (name "CGND") (class "Default")
      (node (ref "MGT1") (pin "P$1") (pinfunction "P$1_P$1") (pintype "bidirectional"))
      (node (ref "MGT2") (pin "P$1") (pinfunction "P$1_P$1") (pintype "bidirectional"))
      (node (ref "MGT3") (pin "P$1") (pinfunction "P$1_P$1") (pintype "bidirectional"))
      (node (ref "MGT4") (pin "P$1") (pinfunction "P$1_P$1") (pintype "bidirectional"))
      (node (ref "R34") (pin "2") (pinfunction "2_2") (pintype "passive"))
      (node (ref "X1") (pin "CGND1") (pinfunction "SGND1_CGND1") (pintype "bidirectional"))
      (node (ref "X1") (pin "CGND2") (pinfunction "SGND2_CGND2") (pintype "bidirectional"))
      (node (ref "X1") (pin "CGND3") (pinfunction "SGND3_CGND3") (pintype "bidirectional"))
      (node (ref "X1") (pin "CGND4") (pinfunction "SGND4_CGND4") (pintype "bidirectional"))
      (node (ref "X1") (pin "CGND5") (pinfunction "SGND5_CGND5") (pintype "bidirectional"))
      (node (ref "X1") (pin "CGND6") (pinfunction "SGND6_CGND6") (pintype "bidirectional"))
      (node (ref "X2") (pin "S1") (pinfunction "SHD1_S1") (pintype "passive"))
      (node (ref "X2") (pin "S2") (pinfunction "SHD2_S2") (pintype "passive"))
      (node (ref "X5") (pin "10") (pinfunction "GND_2_10") (pintype "bidirectional"))
      (node (ref "X5") (pin "11") (pinfunction "GND_3_11") (pintype "bidirectional"))
      (node (ref "X5") (pin "13") (pinfunction "GND_4_13") (pintype "bidirectional"))
      (node (ref "X5") (pin "9") (pinfunction "GND_1_9") (pintype "bidirectional"))
    )
    (net (code "169") (name "GND") (class "Default")
      (node (ref "C1") (pin "1") (pinfunction "1_1") (pintype "passive"))
      (node (ref "C100") (pin "2") (pinfunction "2_2") (pintype "passive"))
      (node (ref "C101") (pin "2") (pinfunction "2_2") (pintype "passive"))
      (node (ref "C102") (pin "2") (pinfunction "2_2") (pintype "passive"))
      (node (ref "C104") (pin "2") (pinfunction "2_2") (pintype "passive"))
      (node (ref "C105") (pin "2") (pinfunction "2_2") (pintype "passive"))
      (node (ref "C106") (pin "2") (pinfunction "2_2") (pintype "passive"))
      (node (ref "C11") (pin "-") (pinfunction "-_-") (pintype "passive"))
      (node (ref "C14") (pin "2") (pinfunction "2_2") (pintype "passive"))
      (node (ref "C15") (pin "2") (pinfunction "2_2") (pintype "passive"))
      (node (ref "C2") (pin "1") (pinfunction "1_1") (pintype "passive"))
      (node (ref "C21") (pin "2") (pinfunction "2_2") (pintype "passive"))
      (node (ref "C22") (pin "2") (pinfunction "2_2") (pintype "passive"))
      (node (ref "C3") (pin "2") (pinfunction "2_2") (pintype "passive"))
      (node (ref "C301") (pin "2") (pinfunction "2_2") (pintype "passive"))
      (node (ref "C4") (pin "2") (pinfunction "2_2") (pintype "passive"))
      (node (ref "C401") (pin "2") (pinfunction "2_2") (pintype "passive"))
      (node (ref "C404") (pin "2") (pinfunction "2_2") (pintype "passive"))
      (node (ref "C6") (pin "1") (pinfunction "1_1") (pintype "passive"))
      (node (ref "C79") (pin "2") (pinfunction "2_2") (pintype "passive"))
      (node (ref "C801") (pin "2") (pinfunction "2_2") (pintype "passive"))
      (node (ref "C85") (pin "2") (pinfunction "2_2") (pintype "passive"))
      (node (ref "C87") (pin "2") (pinfunction "2_2") (pintype "passive"))
      (node (ref "C88") (pin "2") (pinfunction "2_2") (pintype "passive"))
      (node (ref "D18") (pin "A") (pinfunction "A_A") (pintype "passive"))
      (node (ref "D305") (pin "3") (pinfunction "3_3") (pintype "passive"))
      (node (ref "D805") (pin "3") (pinfunction "3_3") (pintype "passive"))
      (node (ref "EC30") (pin "2") (pinfunction "2_2") (pintype "passive"))
      (node (ref "EC31") (pin "2") (pinfunction "2_2") (pintype "passive"))
      (node (ref "EC32") (pin "2") (pinfunction "2_2") (pintype "passive"))
      (node (ref "EC33") (pin "2") (pinfunction "2_2") (pintype "passive"))
      (node (ref "EC34") (pin "2") (pinfunction "2_2") (pintype "passive"))
      (node (ref "EC35") (pin "2") (pinfunction "2_2") (pintype "passive"))
      (node (ref "EC36") (pin "2") (pinfunction "2_2") (pintype "passive"))
      (node (ref "EC37") (pin "2") (pinfunction "2_2") (pintype "passive"))
      (node (ref "EC38") (pin "2") (pinfunction "2_2") (pintype "passive"))
      (node (ref "EC39") (pin "2") (pinfunction "2_2") (pintype "passive"))
      (node (ref "EC40") (pin "2") (pinfunction "2_2") (pintype "passive"))
      (node (ref "EC41") (pin "2") (pinfunction "2_2") (pintype "passive"))
      (node (ref "EC42") (pin "2") (pinfunction "2_2") (pintype "passive"))
      (node (ref "ER101") (pin "2") (pinfunction "2_2") (pintype "passive"))
      (node (ref "ER102") (pin "2") (pinfunction "2_2") (pintype "passive"))
      (node (ref "ER103") (pin "2") (pinfunction "2_2") (pintype "passive"))
      (node (ref "ER104") (pin "2") (pinfunction "2_2") (pintype "passive"))
      (node (ref "ER115") (pin "1") (pinfunction "1_1") (pintype "passive"))
      (node (ref "ER117") (pin "1") (pinfunction "1_1") (pintype "passive"))
      (node (ref "ER120") (pin "1") (pinfunction "1_1") (pintype "passive"))
      (node (ref "ER128") (pin "1") (pinfunction "1_1") (pintype "passive"))
      (node (ref "ER129") (pin "2") (pinfunction "2_2") (pintype "passive"))
      (node (ref "G1") (pin "-") (pinfunction "-_-") (pintype "passive"))
      (node (ref "IC14") (pin "4") (pinfunction "V-_4") (pintype "power_in"))
      (node (ref "IC2") (pin "8") (pinfunction "GND_8") (pintype "power_in"))
      (node (ref "IC4") (pin "15") (pinfunction "INH_15") (pintype "input"))
      (node (ref "IC5") (pin "10") (pinfunction "SER_10") (pintype "input"))
      (node (ref "IC5") (pin "15") (pinfunction "INH_15") (pintype "input"))
      (node (ref "IC5") (pin "3") (pinfunction "E_3") (pintype "input"))
      (node (ref "IC5") (pin "4") (pinfunction "F_4") (pintype "input"))
      (node (ref "IC5") (pin "5") (pinfunction "G_5") (pintype "input"))
      (node (ref "IC5") (pin "6") (pinfunction "H_6") (pintype "input"))
      (node (ref "J1") (pin "2") (pinfunction "2_2") (pintype "bidirectional"))
      (node (ref "J2") (pin "2") (pinfunction "2_2") (pintype "bidirectional"))
      (node (ref "J3") (pin "2") (pinfunction "2_2") (pintype "bidirectional"))
      (node (ref "J4") (pin "2") (pinfunction "2_2") (pintype "bidirectional"))
      (node (ref "J5") (pin "2") (pinfunction "2_2") (pintype "bidirectional"))
      (node (ref "J6") (pin "2") (pinfunction "2_2") (pintype "bidirectional"))
      (node (ref "J7") (pin "2") (pinfunction "2_2") (pintype "bidirectional"))
      (node (ref "R168") (pin "2") (pinfunction "2_2") (pintype "passive"))
      (node (ref "R18") (pin "1") (pinfunction "1_1") (pintype "passive"))
      (node (ref "R26") (pin "2") (pinfunction "2_2") (pintype "passive"))
      (node (ref "R27") (pin "1") (pinfunction "1_1") (pintype "passive"))
      (node (ref "R281") (pin "1") (pinfunction "1_1") (pintype "bidirectional"))
      (node (ref "R281") (pin "2") (pinfunction "2_2") (pintype "bidirectional"))
      (node (ref "R281") (pin "3") (pinfunction "3_3") (pintype "bidirectional"))
      (node (ref "R281") (pin "4") (pinfunction "4_4") (pintype "bidirectional"))
      (node (ref "R282") (pin "1") (pinfunction "1_1") (pintype "bidirectional"))
      (node (ref "R282") (pin "2") (pinfunction "2_2") (pintype "bidirectional"))
      (node (ref "R282") (pin "3") (pinfunction "3_3") (pintype "bidirectional"))
      (node (ref "R282") (pin "4") (pinfunction "4_4") (pintype "bidirectional"))
      (node (ref "R291") (pin "1") (pinfunction "1_1") (pintype "bidirectional"))
      (node (ref "R291") (pin "2") (pinfunction "2_2") (pintype "bidirectional"))
      (node (ref "R291") (pin "3") (pinfunction "3_3") (pintype "bidirectional"))
      (node (ref "R291") (pin "4") (pinfunction "4_4") (pintype "bidirectional"))
      (node (ref "R301") (pin "2") (pinfunction "2_2") (pintype "passive"))
      (node (ref "R302") (pin "2") (pinfunction "2_2") (pintype "passive"))
      (node (ref "R304") (pin "1") (pinfunction "1_1") (pintype "passive"))
      (node (ref "R34") (pin "1") (pinfunction "1_1") (pintype "passive"))
      (node (ref "R35") (pin "1") (pinfunction "1_1") (pintype "bidirectional"))
      (node (ref "R35") (pin "2") (pinfunction "2_2") (pintype "bidirectional"))
      (node (ref "R35") (pin "3") (pinfunction "3_3") (pintype "bidirectional"))
      (node (ref "R35") (pin "4") (pinfunction "4_4") (pintype "bidirectional"))
      (node (ref "R39") (pin "1") (pinfunction "1_1") (pintype "passive"))
      (node (ref "R401") (pin "2") (pinfunction "2_2") (pintype "passive"))
      (node (ref "R402") (pin "2") (pinfunction "2_2") (pintype "passive"))
      (node (ref "R53") (pin "1") (pinfunction "1_1") (pintype "passive"))
      (node (ref "R54") (pin "1") (pinfunction "1_1") (pintype "passive"))
      (node (ref "R55") (pin "1") (pinfunction "1_1") (pintype "passive"))
      (node (ref "R56") (pin "1") (pinfunction "1_1") (pintype "passive"))
      (node (ref "R57") (pin "1") (pinfunction "1_1") (pintype "passive"))
      (node (ref "R58") (pin "1") (pinfunction "1_1") (pintype "passive"))
      (node (ref "R59") (pin "1") (pinfunction "1_1") (pintype "passive"))
      (node (ref "R6") (pin "1") (pinfunction "1_1") (pintype "passive"))
      (node (ref "R60") (pin "1") (pinfunction "1_1") (pintype "passive"))
      (node (ref "R61") (pin "1") (pinfunction "1_1") (pintype "passive"))
      (node (ref "R62") (pin "1") (pinfunction "1_1") (pintype "passive"))
      (node (ref "R63") (pin "1") (pinfunction "1_1") (pintype "passive"))
      (node (ref "R64") (pin "1") (pinfunction "1_1") (pintype "passive"))
      (node (ref "R65") (pin "1") (pinfunction "1_1") (pintype "passive"))
      (node (ref "R66") (pin "1") (pinfunction "1_1") (pintype "passive"))
      (node (ref "R67") (pin "1") (pinfunction "1_1") (pintype "passive"))
      (node (ref "R68") (pin "1") (pinfunction "1_1") (pintype "passive"))
      (node (ref "R801") (pin "2") (pinfunction "2_2") (pintype "passive"))
      (node (ref "R802") (pin "2") (pinfunction "2_2") (pintype "passive"))
      (node (ref "RTC1") (pin "5") (pinfunction "GND_5") (pintype "power_in"))
      (node (ref "S1") (pin "2") (pinfunction "2_2") (pintype "bidirectional"))
      (node (ref "S1") (pin "4") (pinfunction "4_4") (pintype "bidirectional"))
      (node (ref "S2") (pin "1") (pinfunction "1_1") (pintype "bidirectional"))
      (node (ref "S2") (pin "3") (pinfunction "3_3") (pintype "bidirectional"))
      (node (ref "TP8") (pin "P$1") (pinfunction "TP_P$1") (pintype "bidirectional"))
      (node (ref "U1") (pin "A1") (pinfunction "DGND_A1") (pintype "bidirectional"))
      (node (ref "U1") (pin "A20") (pinfunction "DGND_A20") (pintype "bidirectional"))
      (node (ref "U1") (pin "D15") (pinfunction "DGND_D15") (pintype "bidirectional"))
      (node (ref "U1") (pin "D16") (pinfunction "DGND_D16") (pintype "bidirectional"))
      (node (ref "U1") (pin "D17") (pinfunction "DGND_D17") (pintype "bidirectional"))
      (node (ref "U1") (pin "D4") (pinfunction "DGND_D4") (pintype "bidirectional"))
      (node (ref "U1") (pin "D5") (pinfunction "DGND_D5") (pintype "bidirectional"))
      (node (ref "U1") (pin "E10") (pinfunction "DGND_E10") (pintype "bidirectional"))
      (node (ref "U1") (pin "E11") (pinfunction "DGND_E11") (pintype "bidirectional"))
      (node (ref "U1") (pin "E12") (pinfunction "DGND_E12") (pintype "bidirectional"))
      (node (ref "U1") (pin "E13") (pinfunction "DGND_E13") (pintype "bidirectional"))
      (node (ref "U1") (pin "E14") (pinfunction "DGND_E14") (pintype "bidirectional"))
      (node (ref "U1") (pin "E15") (pinfunction "DGND_E15") (pintype "bidirectional"))
      (node (ref "U1") (pin "E16") (pinfunction "DGND_E16") (pintype "bidirectional"))
      (node (ref "U1") (pin "E17") (pinfunction "DGND_E17") (pintype "bidirectional"))
      (node (ref "U1") (pin "E4") (pinfunction "DGND_E4") (pintype "bidirectional"))
      (node (ref "U1") (pin "E5") (pinfunction "DGND_E5") (pintype "bidirectional"))
      (node (ref "U1") (pin "E6") (pinfunction "DGND_E6") (pintype "bidirectional"))
      (node (ref "U1") (pin "E7") (pinfunction "DGND_E7") (pintype "bidirectional"))
      (node (ref "U1") (pin "E8") (pinfunction "DGND_E8") (pintype "bidirectional"))
      (node (ref "U1") (pin "E9") (pinfunction "DGND_E9") (pintype "bidirectional"))
      (node (ref "U1") (pin "F10") (pinfunction "DGND_F10") (pintype "bidirectional"))
      (node (ref "U1") (pin "F11") (pinfunction "DGND_F11") (pintype "bidirectional"))
      (node (ref "U1") (pin "F16") (pinfunction "DGND_F16") (pintype "bidirectional"))
      (node (ref "U1") (pin "F17") (pinfunction "DGND_F17") (pintype "bidirectional"))
      (node (ref "U1") (pin "F5") (pinfunction "DGND_F5") (pintype "bidirectional"))
      (node (ref "U1") (pin "G16") (pinfunction "DGND_G16") (pintype "bidirectional"))
      (node (ref "U1") (pin "G5") (pinfunction "DGND_G5") (pintype "bidirectional"))
      (node (ref "U1") (pin "H16") (pinfunction "DGND_H16") (pintype "bidirectional"))
      (node (ref "U1") (pin "H5") (pinfunction "DGND_H5") (pintype "bidirectional"))
      (node (ref "U1") (pin "J10") (pinfunction "DGND_J10") (pintype "bidirectional"))
      (node (ref "U1") (pin "J11") (pinfunction "DGND_J11") (pintype "bidirectional"))
      (node (ref "U1") (pin "J12") (pinfunction "DGND_J12") (pintype "bidirectional"))
      (node (ref "U1") (pin "J13") (pinfunction "DGND_J13") (pintype "bidirectional"))
      (node (ref "U1") (pin "J16") (pinfunction "DGND_J16") (pintype "bidirectional"))
      (node (ref "U1") (pin "J5") (pinfunction "DGND_J5") (pintype "bidirectional"))
      (node (ref "U1") (pin "J9") (pinfunction "DGND_J9") (pintype "bidirectional"))
      (node (ref "U1") (pin "K12") (pinfunction "DGND_K12") (pintype "bidirectional"))
      (node (ref "U1") (pin "K15") (pinfunction "DGND_K15") (pintype "bidirectional"))
      (node (ref "U1") (pin "K16") (pinfunction "DGND_K16") (pintype "bidirectional"))
      (node (ref "U1") (pin "K5") (pinfunction "DGND_K5") (pintype "bidirectional"))
      (node (ref "U1") (pin "K6") (pinfunction "DGND_K6") (pintype "bidirectional"))
      (node (ref "U1") (pin "K7") (pinfunction "DGND_K7") (pintype "bidirectional"))
      (node (ref "U1") (pin "K8") (pinfunction "DGND_K8") (pintype "bidirectional"))
      (node (ref "U1") (pin "K9") (pinfunction "DGND_K9") (pintype "bidirectional"))
      (node (ref "U1") (pin "L15") (pinfunction "DGND_L15") (pintype "bidirectional"))
      (node (ref "U1") (pin "L16") (pinfunction "DGND_L16") (pintype "bidirectional"))
      (node (ref "U1") (pin "L5") (pinfunction "DGND_L5") (pintype "bidirectional"))
      (node (ref "U1") (pin "L6") (pinfunction "DGND_L6") (pintype "bidirectional"))
      (node (ref "U1") (pin "M15") (pinfunction "DGND_M15") (pintype "bidirectional"))
      (node (ref "U1") (pin "M16") (pinfunction "DGND_M16") (pintype "bidirectional"))
      (node (ref "U1") (pin "M5") (pinfunction "DGND_M5") (pintype "bidirectional"))
      (node (ref "U1") (pin "N15") (pinfunction "DGND_N15") (pintype "bidirectional"))
      (node (ref "U1") (pin "N16") (pinfunction "DGND_N16") (pintype "bidirectional"))
      (node (ref "U1") (pin "N5") (pinfunction "DGND_N5") (pintype "bidirectional"))
      (node (ref "U1") (pin "N6") (pinfunction "DGND_N6") (pintype "bidirectional"))
      (node (ref "U1") (pin "P12") (pinfunction "DGND_P12") (pintype "bidirectional"))
      (node (ref "U1") (pin "P13") (pinfunction "DGND_P13") (pintype "bidirectional"))
      (node (ref "U1") (pin "P14") (pinfunction "DGND_P14") (pintype "bidirectional"))
      (node (ref "U1") (pin "P15") (pinfunction "DGND_P15") (pintype "bidirectional"))
      (node (ref "U1") (pin "P16") (pinfunction "DGND_P16") (pintype "bidirectional"))
      (node (ref "U1") (pin "P5") (pinfunction "DGND_P5") (pintype "bidirectional"))
      (node (ref "U1") (pin "P6") (pinfunction "DGND_P6") (pintype "bidirectional"))
      (node (ref "U1") (pin "P7") (pinfunction "DGND_P7") (pintype "bidirectional"))
      (node (ref "U1") (pin "P8") (pinfunction "DGND_P8") (pintype "bidirectional"))
      (node (ref "U1") (pin "P9") (pinfunction "DGND_P9") (pintype "bidirectional"))
      (node (ref "U1") (pin "R10") (pinfunction "DGND_R10") (pintype "bidirectional"))
      (node (ref "U1") (pin "R11") (pinfunction "DGND_R11") (pintype "bidirectional"))
      (node (ref "U1") (pin "R12") (pinfunction "DGND_R12") (pintype "bidirectional"))
      (node (ref "U1") (pin "R16") (pinfunction "DGND_R16") (pintype "bidirectional"))
      (node (ref "U1") (pin "R5") (pinfunction "DGND_R5") (pintype "bidirectional"))
      (node (ref "U1") (pin "R9") (pinfunction "DGND_R9") (pintype "bidirectional"))
      (node (ref "U1") (pin "T10") (pinfunction "DGND_T10") (pintype "bidirectional"))
      (node (ref "U1") (pin "T11") (pinfunction "DGND_T11") (pintype "bidirectional"))
      (node (ref "U1") (pin "T12") (pinfunction "DGND_T12") (pintype "bidirectional"))
      (node (ref "U1") (pin "T13") (pinfunction "DGND_T13") (pintype "bidirectional"))
      (node (ref "U1") (pin "T14") (pinfunction "DGND_T14") (pintype "bidirectional"))
      (node (ref "U1") (pin "T15") (pinfunction "DGND_T15") (pintype "bidirectional"))
      (node (ref "U1") (pin "T16") (pinfunction "DGND_T16") (pintype "bidirectional"))
      (node (ref "U1") (pin "T17") (pinfunction "DGND_T17") (pintype "bidirectional"))
      (node (ref "U1") (pin "T4") (pinfunction "DGND_T4") (pintype "bidirectional"))
      (node (ref "U1") (pin "T5") (pinfunction "DGND_T5") (pintype "bidirectional"))
      (node (ref "U1") (pin "T6") (pinfunction "DGND_T6") (pintype "bidirectional"))
      (node (ref "U1") (pin "T7") (pinfunction "DGND_T7") (pintype "bidirectional"))
      (node (ref "U1") (pin "T8") (pinfunction "DGND_T8") (pintype "bidirectional"))
      (node (ref "U1") (pin "T9") (pinfunction "DGND_T9") (pintype "bidirectional"))
      (node (ref "U1") (pin "U15") (pinfunction "RTC_KALDO_ENN_U15") (pintype "bidirectional"))
      (node (ref "U1") (pin "U16") (pinfunction "DGND_U16") (pintype "bidirectional"))
      (node (ref "U1") (pin "U17") (pinfunction "DGND_U17") (pintype "bidirectional"))
      (node (ref "U1") (pin "U4") (pinfunction "DGND_U4") (pintype "bidirectional"))
      (node (ref "U1") (pin "U5") (pinfunction "DGND_U5") (pintype "bidirectional"))
      (node (ref "U1") (pin "W13") (pinfunction "OSC1_GND_W13") (pintype "bidirectional"))
      (node (ref "U1") (pin "Y1") (pinfunction "DGND_Y1") (pintype "bidirectional"))
      (node (ref "U1") (pin "Y20") (pinfunction "DGND_Y20") (pintype "bidirectional"))
      (node (ref "U16") (pin "18") (pinfunction "PIRQ#_18") (pintype "bidirectional"))
      (node (ref "U16") (pin "19") (pinfunction "ATEST_19") (pintype "bidirectional"))
      (node (ref "U16") (pin "2") (pinfunction "GND_2") (pintype "bidirectional"))
      (node (ref "U16") (pin "20") (pinfunction "TWI_WAKEUP#_20") (pintype "bidirectional"))
      (node (ref "U16") (pin "21") (pinfunction "ATEST_21") (pintype "bidirectional"))
      (node (ref "U16") (pin "23") (pinfunction "GND_23") (pintype "bidirectional"))
      (node (ref "U16") (pin "24") (pinfunction "ATEST_24") (pintype "bidirectional"))
      (node (ref "U16") (pin "32") (pinfunction "GND_32") (pintype "bidirectional"))
      (node (ref "U16") (pin "5") (pinfunction "TESTL_5") (pintype "bidirectional"))
      (node (ref "U16") (pin "6") (pinfunction "XTAMPER_6") (pintype "bidirectional"))
      (node (ref "U16") (pin "9") (pinfunction "GND_9") (pintype "bidirectional"))
      (node (ref "U2") (pin "4") (pinfunction "GND_4") (pintype "power_in"))
      (node (ref "U27") (pin "33") (pinfunction "GND_EP_33") (pintype "power_in"))
      (node (ref "U28") (pin "2") (pinfunction "GND_2") (pintype "power_in"))
      (node (ref "U29") (pin "5") (pinfunction "GND_5") (pintype "power_in"))
      (node (ref "U4") (pin "1") (pinfunction "GND_1") (pintype "bidirectional"))
      (node (ref "U40") (pin "3") (pinfunction "GND1_3") (pintype "power_in"))
      (node (ref "U6") (pin "1") (pinfunction "*1OE_1") (pintype "input"))
      (node (ref "U6") (pin "4") (pinfunction "GND_4") (pintype "power_in"))
      (node (ref "VREG1") (pin "3") (pinfunction "GND_3") (pintype "power_in"))
      (node (ref "VREG1") (pin "5") (pinfunction "EN_5") (pintype "input"))
      (node (ref "VREG1") (pin "6") (pinfunction "GND_6") (pintype "power_in"))
      (node (ref "VREG2") (pin "GND") (pinfunction "GND_GND") (pintype "input"))
      (node (ref "X1") (pin "GND") (pinfunction "GND_GND") (pintype "input"))
      (node (ref "X2") (pin "8") (pinfunction "D_GND_8") (pintype "passive"))
      (node (ref "X21") (pin "11") (pinfunction "SK_11") (pintype "passive"))
      (node (ref "X24") (pin "2") (pinfunction "1_2") (pintype "passive"))
      (node (ref "X3") (pin "1") (pinfunction "SK_1") (pintype "passive"))
      (node (ref "X4") (pin "10") (pinfunction "GND2_10") (pintype "bidirectional"))
      (node (ref "X4") (pin "12") (pinfunction "GND3_12") (pintype "bidirectional"))
      (node (ref "X4") (pin "16") (pinfunction "GND4_16") (pintype "bidirectional"))
      (node (ref "X4") (pin "20") (pinfunction "GND5_20") (pintype "bidirectional"))
      (node (ref "X4") (pin "4") (pinfunction "TDIS_4") (pintype "bidirectional"))
      (node (ref "X4") (pin "8") (pinfunction "GND1_8") (pintype "bidirectional"))
      (node (ref "X5") (pin "6") (pinfunction "VSS_6") (pintype "bidirectional"))
      (node (ref "X6") (pin "1") (pinfunction "1_1") (pintype "bidirectional"))
      (node (ref "X8") (pin "1") (pinfunction "SK_1") (pintype "passive"))
    )
    (net (code "170") (name "ISO_GND") (class "Default")
      (node (ref "C402") (pin "2") (pinfunction "2_2") (pintype "passive"))
      (node (ref "C403") (pin "2") (pinfunction "2_2") (pintype "passive"))
      (node (ref "C405") (pin "2") (pinfunction "2_2") (pintype "passive"))
      (node (ref "C406") (pin "-") (pinfunction "-_-") (pintype "passive"))
      (node (ref "D405") (pin "3") (pinfunction "3_3") (pintype "passive"))
      (node (ref "GDT1") (pin "3") (pinfunction "3_3") (pintype "passive"))
      (node (ref "T4") (pin "P$6") (pinfunction "6_P$6") (pintype "passive"))
      (node (ref "T4") (pin "P$7") (pinfunction "7_P$7") (pintype "passive"))
      (node (ref "U40") (pin "15") (pinfunction "GND2_15") (pintype "power_in"))
      (node (ref "U40") (pin "9") (pinfunction "GND2_2_9") (pintype "power_in"))
      (node (ref "VREG4") (pin "2") (pinfunction "GND_2") (pintype "power_in"))
      (node (ref "X41") (pin "3") (pinfunction "1_3") (pintype "passive"))
    )
    (net (code "171") (name "Net-(C105-Pad1)") (class "Default")
      (node (ref "C105") (pin "1") (pinfunction "1_1") (pintype "passive"))
      (node (ref "J24") (pin "1") (pinfunction "1_1") (pintype "bidirectional"))
      (node (ref "VREG2") (pin "IN") (pinfunction "IN_IN") (pintype "input"))
    )
    (net (code "172") (name "Net-(D1-C)") (class "Default")
      (node (ref "D1") (pin "2") (pinfunction "C_2") (pintype "passive"))
      (node (ref "R26") (pin "1") (pinfunction "1_1") (pintype "passive"))
    )
    (net (code "173") (name "Net-(D4-C)") (class "Default")
      (node (ref "D4") (pin "2") (pinfunction "C_2") (pintype "passive"))
      (node (ref "R35") (pin "5") (pinfunction "5_5") (pintype "bidirectional"))
    )
    (net (code "174") (name "Net-(D5-C)") (class "Default")
      (node (ref "D5") (pin "2") (pinfunction "C_2") (pintype "passive"))
      (node (ref "R35") (pin "6") (pinfunction "6_6") (pintype "bidirectional"))
    )
    (net (code "175") (name "Net-(D6-C)") (class "Default")
      (node (ref "D6") (pin "2") (pinfunction "C_2") (pintype "passive"))
      (node (ref "R35") (pin "7") (pinfunction "7_7") (pintype "bidirectional"))
    )
    (net (code "176") (name "Net-(D7-C)") (class "Default")
      (node (ref "D7") (pin "2") (pinfunction "C_2") (pintype "passive"))
      (node (ref "R35") (pin "8") (pinfunction "8_8") (pintype "bidirectional"))
    )
    (net (code "177") (name "Net-(D19-C)") (class "Default")
      (node (ref "D19") (pin "2") (pinfunction "C_2") (pintype "passive"))
      (node (ref "R168") (pin "1") (pinfunction "1_1") (pintype "passive"))
    )
    (net (code "178") (name "Net-(D31-C)") (class "Default")
      (node (ref "D31") (pin "2") (pinfunction "C_2") (pintype "passive"))
      (node (ref "R171") (pin "1") (pinfunction "1_1") (pintype "passive"))
    )
    (net (code "179") (name "Net-(D32-C)") (class "Default")
      (node (ref "D32") (pin "2") (pinfunction "C_2") (pintype "passive"))
      (node (ref "R172") (pin "1") (pinfunction "1_1") (pintype "passive"))
    )
    (net (code "180") (name "Net-(D33-C)") (class "Default")
      (node (ref "D33") (pin "2") (pinfunction "C_2") (pintype "passive"))
      (node (ref "R173") (pin "1") (pinfunction "1_1") (pintype "passive"))
    )
    (net (code "181") (name "Net-(D34-C)") (class "Default")
      (node (ref "D34") (pin "2") (pinfunction "C_2") (pintype "passive"))
      (node (ref "R174") (pin "1") (pinfunction "1_1") (pintype "passive"))
    )
    (net (code "182") (name "Net-(D35-C)") (class "Default")
      (node (ref "D35") (pin "2") (pinfunction "C_2") (pintype "passive"))
      (node (ref "R175") (pin "1") (pinfunction "1_1") (pintype "passive"))
    )
    (net (code "183") (name "Net-(D301-C)") (class "Default")
      (node (ref "D301") (pin "2") (pinfunction "C_2") (pintype "passive"))
      (node (ref "R301") (pin "1") (pinfunction "1_1") (pintype "passive"))
    )
    (net (code "184") (name "Net-(D302-C)") (class "Default")
      (node (ref "D302") (pin "2") (pinfunction "C_2") (pintype "passive"))
      (node (ref "R302") (pin "1") (pinfunction "1_1") (pintype "passive"))
    )
    (net (code "185") (name "Net-(D401-C)") (class "Default")
      (node (ref "D401") (pin "2") (pinfunction "C_2") (pintype "passive"))
      (node (ref "R401") (pin "1") (pinfunction "1_1") (pintype "passive"))
    )
    (net (code "186") (name "Net-(D402-C)") (class "Default")
      (node (ref "D402") (pin "2") (pinfunction "C_2") (pintype "passive"))
      (node (ref "R402") (pin "1") (pinfunction "1_1") (pintype "passive"))
    )
    (net (code "187") (name "Net-(D801-C)") (class "Default")
      (node (ref "D801") (pin "2") (pinfunction "C_2") (pintype "passive"))
      (node (ref "R801") (pin "1") (pinfunction "1_1") (pintype "passive"))
    )
    (net (code "188") (name "Net-(D802-C)") (class "Default")
      (node (ref "D802") (pin "2") (pinfunction "C_2") (pintype "passive"))
      (node (ref "R802") (pin "1") (pinfunction "1_1") (pintype "passive"))
    )
    (net (code "189") (name "Net-(F1-1)") (class "Default")
      (node (ref "F1") (pin "P$1") (pinfunction "1_P$1") (pintype "bidirectional"))
      (node (ref "X24") (pin "1") (pinfunction "1_1") (pintype "passive"))
      (node (ref "X3") (pin "4") (pinfunction "SK_4") (pintype "passive"))
    )
    (net (code "190") (name "Net-(F1-2)") (class "Default")
      (node (ref "D3") (pin "A") (pinfunction "A_A") (pintype "passive"))
      (node (ref "F1") (pin "P$2") (pinfunction "2_P$2") (pintype "bidirectional"))
    )
    (net (code "191") (name "Net-(F401-Pad1)") (class "Default")
      (node (ref "F401") (pin "1") (pinfunction "1_1") (pintype "passive"))
      (node (ref "GDT1") (pin "2") (pinfunction "2_2") (pintype "passive"))
      (node (ref "X41") (pin "1") (pinfunction "1_1") (pintype "passive"))
    )
    (net (code "192") (name "Net-(IC2-O1)") (class "Default")
      (node (ref "IC2") (pin "16") (pinfunction "O1_16") (pintype "open_collector"))
      (node (ref "K1") (pin "2") (pinfunction "2_2") (pintype "passive"))
      (node (ref "R171") (pin "2") (pinfunction "2_2") (pintype "passive"))
    )
    (net (code "193") (name "Net-(IC2-O2)") (class "Default")
      (node (ref "IC2") (pin "15") (pinfunction "O2_15") (pintype "open_collector"))
      (node (ref "K2") (pin "2") (pinfunction "2_2") (pintype "passive"))
      (node (ref "R172") (pin "2") (pinfunction "2_2") (pintype "passive"))
    )
    (net (code "194") (name "Net-(IC2-O3)") (class "Default")
      (node (ref "IC2") (pin "14") (pinfunction "O3_14") (pintype "open_collector"))
      (node (ref "K3") (pin "2") (pinfunction "2_2") (pintype "passive"))
      (node (ref "R173") (pin "2") (pinfunction "2_2") (pintype "passive"))
    )
    (net (code "195") (name "Net-(IC2-O4)") (class "Default")
      (node (ref "IC2") (pin "13") (pinfunction "O4_13") (pintype "open_collector"))
      (node (ref "K4") (pin "2") (pinfunction "2_2") (pintype "passive"))
      (node (ref "R174") (pin "2") (pinfunction "2_2") (pintype "passive"))
    )
    (net (code "196") (name "Net-(IC2-O5)") (class "Default")
      (node (ref "IC2") (pin "12") (pinfunction "O5_12") (pintype "open_collector"))
      (node (ref "K5") (pin "2") (pinfunction "2_2") (pintype "passive"))
      (node (ref "R175") (pin "2") (pinfunction "2_2") (pintype "passive"))
    )
    (net (code "197") (name "Net-(IC4A-A)") (class "Default")
      (node (ref "IC4") (pin "11") (pinfunction "A_11") (pintype "input"))
      (node (ref "R281") (pin "8") (pinfunction "8_8") (pintype "bidirectional"))
      (node (ref "S11") (pin "1") (pinfunction "1_1") (pintype "passive"))
    )
    (net (code "198") (name "Net-(IC4A-B)") (class "Default")
      (node (ref "IC4") (pin "12") (pinfunction "B_12") (pintype "input"))
      (node (ref "R281") (pin "7") (pinfunction "7_7") (pintype "bidirectional"))
      (node (ref "S11") (pin "2") (pinfunction "2_2") (pintype "passive"))
    )
    (net (code "199") (name "Net-(IC4A-C)") (class "Default")
      (node (ref "IC4") (pin "13") (pinfunction "C_13") (pintype "input"))
      (node (ref "R281") (pin "6") (pinfunction "6_6") (pintype "bidirectional"))
      (node (ref "S11") (pin "4") (pinfunction "4_4") (pintype "passive"))
    )
    (net (code "200") (name "Net-(IC4A-D)") (class "Default")
      (node (ref "IC4") (pin "14") (pinfunction "D_14") (pintype "input"))
      (node (ref "R281") (pin "5") (pinfunction "5_5") (pintype "bidirectional"))
      (node (ref "S11") (pin "8") (pinfunction "8_8") (pintype "passive"))
    )
    (net (code "201") (name "Net-(IC4A-E)") (class "Default")
      (node (ref "IC4") (pin "3") (pinfunction "E_3") (pintype "input"))
      (node (ref "R282") (pin "8") (pinfunction "8_8") (pintype "bidirectional"))
      (node (ref "S12") (pin "1") (pinfunction "1_1") (pintype "passive"))
    )
    (net (code "202") (name "Net-(IC4A-F)") (class "Default")
      (node (ref "IC4") (pin "4") (pinfunction "F_4") (pintype "input"))
      (node (ref "R282") (pin "7") (pinfunction "7_7") (pintype "bidirectional"))
      (node (ref "S12") (pin "2") (pinfunction "2_2") (pintype "passive"))
    )
    (net (code "203") (name "Net-(IC4A-G)") (class "Default")
      (node (ref "IC4") (pin "5") (pinfunction "G_5") (pintype "input"))
      (node (ref "R282") (pin "6") (pinfunction "6_6") (pintype "bidirectional"))
      (node (ref "S12") (pin "4") (pinfunction "4_4") (pintype "passive"))
    )
    (net (code "204") (name "Net-(IC4A-H)") (class "Default")
      (node (ref "IC4") (pin "6") (pinfunction "H_6") (pintype "input"))
      (node (ref "R282") (pin "5") (pinfunction "5_5") (pintype "bidirectional"))
      (node (ref "S12") (pin "8") (pinfunction "8_8") (pintype "passive"))
    )
    (net (code "205") (name "Net-(IC4A-SER)") (class "Default")
      (node (ref "IC4") (pin "10") (pinfunction "SER_10") (pintype "input"))
      (node (ref "IC5") (pin "9") (pinfunction "QH_9") (pintype "output"))
    )
    (net (code "206") (name "Net-(IC5A-A)") (class "Default")
      (node (ref "IC5") (pin "11") (pinfunction "A_11") (pintype "input"))
      (node (ref "R291") (pin "8") (pinfunction "8_8") (pintype "bidirectional"))
      (node (ref "S13") (pin "8") (pinfunction "8_8") (pintype "passive"))
    )
    (net (code "207") (name "Net-(IC5A-B)") (class "Default")
      (node (ref "IC5") (pin "12") (pinfunction "B_12") (pintype "input"))
      (node (ref "R291") (pin "7") (pinfunction "7_7") (pintype "bidirectional"))
      (node (ref "S13") (pin "7") (pinfunction "7_7") (pintype "passive"))
    )
    (net (code "208") (name "Net-(IC5A-C)") (class "Default")
      (node (ref "IC5") (pin "13") (pinfunction "C_13") (pintype "input"))
      (node (ref "R291") (pin "6") (pinfunction "6_6") (pintype "bidirectional"))
      (node (ref "S13") (pin "6") (pinfunction "6_6") (pintype "passive"))
    )
    (net (code "209") (name "Net-(IC5A-D)") (class "Default")
      (node (ref "IC5") (pin "14") (pinfunction "D_14") (pintype "input"))
      (node (ref "R291") (pin "5") (pinfunction "5_5") (pintype "bidirectional"))
      (node (ref "S13") (pin "5") (pinfunction "5_5") (pintype "passive"))
    )
    (net (code "210") (name "Net-(IC10A-+IN)") (class "Default")
      (node (ref "C111") (pin "1") (pinfunction "1_1") (pintype "passive"))
      (node (ref "IC10") (pin "3") (pinfunction "+IN_3") (pintype "input"))
      (node (ref "J13") (pin "1") (pinfunction "1_1") (pintype "bidirectional"))
      (node (ref "R214") (pin "2") (pinfunction "2_2") (pintype "passive"))
    )
    (net (code "211") (name "Net-(IC10B-+IN)") (class "Default")
      (node (ref "C121") (pin "1") (pinfunction "1_1") (pintype "passive"))
      (node (ref "IC10") (pin "5") (pinfunction "+IN_5") (pintype "input"))
      (node (ref "J23") (pin "1") (pinfunction "1_1") (pintype "bidirectional"))
      (node (ref "R224") (pin "2") (pinfunction "2_2") (pintype "passive"))
    )
    (net (code "212") (name "Net-(IC11A-+IN)") (class "Default")
      (node (ref "C131") (pin "1") (pinfunction "1_1") (pintype "passive"))
      (node (ref "IC11") (pin "3") (pinfunction "+IN_3") (pintype "input"))
      (node (ref "J33") (pin "1") (pinfunction "1_1") (pintype "bidirectional"))
      (node (ref "R234") (pin "2") (pinfunction "2_2") (pintype "passive"))
    )
    (net (code "213") (name "Net-(IC11B-+IN)") (class "Default")
      (node (ref "C141") (pin "1") (pinfunction "1_1") (pintype "passive"))
      (node (ref "IC11") (pin "5") (pinfunction "+IN_5") (pintype "input"))
      (node (ref "J43") (pin "1") (pinfunction "1_1") (pintype "bidirectional"))
      (node (ref "R244") (pin "2") (pinfunction "2_2") (pintype "passive"))
    )
    (net (code "214") (name "Net-(IC12A-+IN)") (class "Default")
      (node (ref "C151") (pin "1") (pinfunction "1_1") (pintype "passive"))
      (node (ref "IC12") (pin "3") (pinfunction "+IN_3") (pintype "input"))
      (node (ref "J53") (pin "1") (pinfunction "1_1") (pintype "bidirectional"))
      (node (ref "R254") (pin "2") (pinfunction "2_2") (pintype "passive"))
    )
    (net (code "215") (name "Net-(IC12B-+IN)") (class "Default")
      (node (ref "C161") (pin "1") (pinfunction "1_1") (pintype "passive"))
      (node (ref "IC12") (pin "5") (pinfunction "+IN_5") (pintype "input"))
      (node (ref "J63") (pin "1") (pinfunction "1_1") (pintype "bidirectional"))
      (node (ref "R264") (pin "2") (pinfunction "2_2") (pintype "passive"))
    )
    (net (code "216") (name "Net-(J3-Pad1)") (class "Default")
      (node (ref "J3") (pin "1") (pinfunction "1_1") (pintype "bidirectional"))
      (node (ref "R69") (pin "2") (pinfunction "2_2") (pintype "passive"))
    )
    (net (code "217") (name "Net-(J11-Pad2)") (class "Default")
      (node (ref "J11") (pin "2") (pinfunction "2_2") (pintype "bidirectional"))
      (node (ref "R211") (pin "2") (pinfunction "2_2") (pintype "passive"))
    )
    (net (code "218") (name "Net-(J12-Pad2)") (class "Default")
      (node (ref "J12") (pin "2") (pinfunction "2_2") (pintype "bidirectional"))
      (node (ref "R212") (pin "1") (pinfunction "1_1") (pintype "passive"))
    )
    (net (code "219") (name "Net-(J13-Pad2)") (class "Default")
      (node (ref "J13") (pin "2") (pinfunction "2_2") (pintype "bidirectional"))
      (node (ref "R213") (pin "1") (pinfunction "1_1") (pintype "passive"))
    )
    (net (code "220") (name "Net-(J21-Pad2)") (class "Default")
      (node (ref "J21") (pin "2") (pinfunction "2_2") (pintype "bidirectional"))
      (node (ref "R221") (pin "2") (pinfunction "2_2") (pintype "passive"))
    )
    (net (code "221") (name "Net-(J22-Pad2)") (class "Default")
      (node (ref "J22") (pin "2") (pinfunction "2_2") (pintype "bidirectional"))
      (node (ref "R222") (pin "1") (pinfunction "1_1") (pintype "passive"))
    )
    (net (code "222") (name "Net-(J23-Pad2)") (class "Default")
      (node (ref "J23") (pin "2") (pinfunction "2_2") (pintype "bidirectional"))
      (node (ref "R223") (pin "1") (pinfunction "1_1") (pintype "passive"))
    )
    (net (code "223") (name "Net-(J31-Pad2)") (class "Default")
      (node (ref "J31") (pin "2") (pinfunction "2_2") (pintype "bidirectional"))
      (node (ref "R231") (pin "2") (pinfunction "2_2") (pintype "passive"))
    )
    (net (code "224") (name "Net-(J32-Pad2)") (class "Default")
      (node (ref "J32") (pin "2") (pinfunction "2_2") (pintype "bidirectional"))
      (node (ref "R232") (pin "1") (pinfunction "1_1") (pintype "passive"))
    )
    (net (code "225") (name "Net-(J33-Pad2)") (class "Default")
      (node (ref "J33") (pin "2") (pinfunction "2_2") (pintype "bidirectional"))
      (node (ref "R233") (pin "1") (pinfunction "1_1") (pintype "passive"))
    )
    (net (code "226") (name "Net-(J41-Pad2)") (class "Default")
      (node (ref "J41") (pin "2") (pinfunction "2_2") (pintype "bidirectional"))
      (node (ref "R241") (pin "2") (pinfunction "2_2") (pintype "passive"))
    )
    (net (code "227") (name "Net-(J42-Pad2)") (class "Default")
      (node (ref "J42") (pin "2") (pinfunction "2_2") (pintype "bidirectional"))
      (node (ref "R242") (pin "1") (pinfunction "1_1") (pintype "passive"))
    )
    (net (code "228") (name "Net-(J43-Pad2)") (class "Default")
      (node (ref "J43") (pin "2") (pinfunction "2_2") (pintype "bidirectional"))
      (node (ref "R243") (pin "1") (pinfunction "1_1") (pintype "passive"))
    )
    (net (code "229") (name "Net-(J51-Pad2)") (class "Default")
      (node (ref "J51") (pin "2") (pinfunction "2_2") (pintype "bidirectional"))
      (node (ref "R251") (pin "2") (pinfunction "2_2") (pintype "passive"))
    )
    (net (code "230") (name "Net-(J52-Pad2)") (class "Default")
      (node (ref "J52") (pin "2") (pinfunction "2_2") (pintype "bidirectional"))
      (node (ref "R252") (pin "1") (pinfunction "1_1") (pintype "passive"))
    )
    (net (code "231") (name "Net-(J53-Pad2)") (class "Default")
      (node (ref "J53") (pin "2") (pinfunction "2_2") (pintype "bidirectional"))
      (node (ref "R253") (pin "1") (pinfunction "1_1") (pintype "passive"))
    )
    (net (code "232") (name "Net-(J61-Pad2)") (class "Default")
      (node (ref "J61") (pin "2") (pinfunction "2_2") (pintype "bidirectional"))
      (node (ref "R261") (pin "2") (pinfunction "2_2") (pintype "passive"))
    )
    (net (code "233") (name "Net-(J62-Pad2)") (class "Default")
      (node (ref "J62") (pin "2") (pinfunction "2_2") (pintype "bidirectional"))
      (node (ref "R262") (pin "1") (pinfunction "1_1") (pintype "passive"))
    )
    (net (code "234") (name "Net-(J63-Pad2)") (class "Default")
      (node (ref "J63") (pin "2") (pinfunction "2_2") (pintype "bidirectional"))
      (node (ref "R263") (pin "1") (pinfunction "1_1") (pintype "passive"))
    )
    (net (code "235") (name "Net-(K5B-P)") (class "Default")
      (node (ref "K5") (pin "C") (pinfunction "P_C") (pintype "passive"))
      (node (ref "X21") (pin "1") (pinfunction "SK_1") (pintype "passive"))
    )
    (net (code "236") (name "Net-(K5B-S)") (class "Default")
      (node (ref "K5") (pin "NO") (pinfunction "S_NO") (pintype "passive"))
      (node (ref "X21") (pin "2") (pinfunction "SK_2") (pintype "passive"))
    )
    (net (code "237") (name "Net-(R10-Pad1)") (class "Default")
      (node (ref "R10") (pin "1") (pinfunction "1_1") (pintype "passive"))
      (node (ref "X1") (pin "VBUS") (pinfunction "VBUS_VBUS") (pintype "input"))
    )
    (net (code "238") (name "Net-(R11-Pad1)") (class "Default")
      (node (ref "R11") (pin "1") (pinfunction "1_1") (pintype "passive"))
      (node (ref "S1") (pin "1") (pinfunction "1_1") (pintype "bidirectional"))
      (node (ref "S1") (pin "3") (pinfunction "3_3") (pintype "bidirectional"))
    )
    (net (code "239") (name "Net-(RTC1-VBAT)") (class "Default")
      (node (ref "G1") (pin "+") (pinfunction "+_+") (pintype "passive"))
      (node (ref "RTC1") (pin "6") (pinfunction "VBAT_6") (pintype "power_in"))
    )
    (net (code "240") (name "Net-(T4-1)") (class "Default")
      (node (ref "T4") (pin "P$1") (pinfunction "1_P$1") (pintype "passive"))
      (node (ref "U40") (pin "1") (pinfunction "D1_1") (pintype "passive"))
    )
    (net (code "241") (name "Net-(T4-4)") (class "Default")
      (node (ref "T4") (pin "P$4") (pinfunction "4_P$4") (pintype "passive"))
      (node (ref "U40") (pin "2") (pinfunction "D2_2") (pintype "passive"))
    )
    (net (code "242") (name "Net-(T4-5)") (class "Default")
      (node (ref "D404") (pin "A") (pinfunction "A_A") (pintype "passive"))
      (node (ref "T4") (pin "P$5") (pinfunction "5_P$5") (pintype "passive"))
    )
    (net (code "243") (name "Net-(T4-8)") (class "Default")
      (node (ref "D403") (pin "A") (pinfunction "A_A") (pintype "passive"))
      (node (ref "T4") (pin "P$8") (pinfunction "8_P$8") (pintype "passive"))
    )
    (net (code "244") (name "Net-(U1A-EEPROM_WP)") (class "Default")
      (node (ref "J1") (pin "1") (pinfunction "1_1") (pintype "bidirectional"))
      (node (ref "U1") (pin "M2") (pinfunction "EEPROM_WP_M2") (pintype "bidirectional"))
    )
    (net (code "245") (name "Net-(U1A-PWRONRSTN_OD)") (class "Default")
      (node (ref "R5") (pin "1") (pinfunction "1_1") (pintype "passive"))
      (node (ref "U1") (pin "C17") (pinfunction "PWRONRSTN_OD_C17") (pintype "bidirectional"))
    )
    (net (code "246") (name "Net-(U1A-SYS_VDD1_CTL)") (class "Default")
      (node (ref "TP33") (pin "TP") (pinfunction "TP_TP") (pintype "input"))
      (node (ref "U1") (pin "F18") (pinfunction "SYS_VDD1_CTL_F18") (pintype "bidirectional"))
    )
    (net (code "247") (name "Net-(U1C-XDMA_EVENT_INTR0)") (class "Default")
      (node (ref "R4") (pin "1") (pinfunction "1_1") (pintype "passive"))
      (node (ref "U1") (pin "W14") (pinfunction "XDMA_EVENT_INTR0_W14") (pintype "bidirectional"))
    )
    (net (code "248") (name "Net-(U1C-XDMA_EVENT_INTR1)") (class "Default")
      (node (ref "R3") (pin "1") (pinfunction "1_1") (pintype "passive"))
      (node (ref "U1") (pin "V14") (pinfunction "XDMA_EVENT_INTR1_V14") (pintype "bidirectional"))
    )
    (net (code "249") (name "Net-(U1D-LCD_AC_BIAS_EN)") (class "Default")
      (node (ref "R28") (pin "1") (pinfunction "1_1") (pintype "passive"))
      (node (ref "U1") (pin "V20") (pinfunction "LCD_AC_BIAS_EN_V20") (pintype "bidirectional"))
    )
    (net (code "250") (name "Net-(U1D-LCD_HSYNC)") (class "Default")
      (node (ref "R29") (pin "1") (pinfunction "1_1") (pintype "passive"))
      (node (ref "U1") (pin "U19") (pinfunction "LCD_HSYNC_U19") (pintype "bidirectional"))
    )
    (net (code "251") (name "Net-(U1D-LCD_PCLK)") (class "Default")
      (node (ref "R31") (pin "1") (pinfunction "1_1") (pintype "passive"))
      (node (ref "U1") (pin "U20") (pinfunction "LCD_PCLK_U20") (pintype "bidirectional"))
    )
    (net (code "252") (name "Net-(U1D-LCD_VSYNC)") (class "Default")
      (node (ref "R30") (pin "1") (pinfunction "1_1") (pintype "passive"))
      (node (ref "U1") (pin "U18") (pinfunction "LCD_VSYNC_U18") (pintype "bidirectional"))
    )
    (net (code "253") (name "Net-(U4-MR#)") (class "Default")
      (node (ref "R11") (pin "2") (pinfunction "2_2") (pintype "passive"))
      (node (ref "R5") (pin "2") (pinfunction "2_2") (pintype "passive"))
      (node (ref "U4") (pin "3") (pinfunction "MR#_3") (pintype "bidirectional"))
    )
    (net (code "254") (name "Net-(U4-RESET#)") (class "Default")
      (node (ref "R8") (pin "2") (pinfunction "2_2") (pintype "passive"))
      (node (ref "U4") (pin "2") (pinfunction "RESET#_2") (pintype "bidirectional"))
    )
    (net (code "255") (name "Net-(U5-CATHODE)") (class "Default")
      (node (ref "Q1") (pin "B") (pinfunction "B_B") (pintype "passive"))
      (node (ref "R21") (pin "1") (pinfunction "1_1") (pintype "passive"))
      (node (ref "U5") (pin "2") (pinfunction "CATHODE_2") (pintype "bidirectional"))
    )
    (net (code "256") (name "Net-(U5-REF)") (class "Default")
      (node (ref "R15") (pin "2") (pinfunction "2_2") (pintype "passive"))
      (node (ref "R20") (pin "1") (pinfunction "1_1") (pintype "passive"))
      (node (ref "U5") (pin "1") (pinfunction "REF_1") (pintype "bidirectional"))
    )
    (net (code "257") (name "Net-(U27-NINT{slash}TXER{slash}TXD4)") (class "Default")
      (node (ref "ER129") (pin "1") (pinfunction "1_1") (pintype "passive"))
      (node (ref "U27") (pin "18") (pinfunction "NINT/TXER/TXD4_18") (pintype "bidirectional"))
    )
    (net (code "258") (name "Net-(U27-RBIAS)") (class "Default")
      (node (ref "ER128") (pin "2") (pinfunction "2_2") (pintype "passive"))
      (node (ref "U27") (pin "32") (pinfunction "RBIAS_32") (pintype "passive"))
    )
    (net (code "259") (name "Net-(U27-VDDCR)") (class "Default")
      (node (ref "EC33") (pin "1") (pinfunction "1_1") (pintype "passive"))
      (node (ref "EC35") (pin "1") (pinfunction "1_1") (pintype "passive"))
      (node (ref "U27") (pin "6") (pinfunction "VDDCR_6") (pintype "power_in"))
    )
    (net (code "260") (name "Net-(U27-XTAL1{slash}CLKIN)") (class "Default")
      (node (ref "ER126") (pin "1") (pinfunction "1_1") (pintype "passive"))
      (node (ref "U27") (pin "5") (pinfunction "XTAL1/CLKIN_5") (pintype "input"))
    )
    (net (code "261") (name "Net-(U27-XTAL2)") (class "Default")
      (node (ref "ER125") (pin "1") (pinfunction "1_1") (pintype "passive"))
      (node (ref "ER127") (pin "1") (pinfunction "1_1") (pintype "passive"))
      (node (ref "U27") (pin "4") (pinfunction "XTAL2_4") (pintype "input"))
    )
    (net (code "262") (name "Net-(VREG1-IN)") (class "Default")
      (node (ref "C100") (pin "1") (pinfunction "1_1") (pintype "passive"))
      (node (ref "C101") (pin "1") (pinfunction "1_1") (pintype "passive"))
      (node (ref "D3") (pin "C") (pinfunction "C_C") (pintype "passive"))
      (node (ref "J24") (pin "2") (pinfunction "2_2") (pintype "bidirectional"))
      (node (ref "VREG1") (pin "1") (pinfunction "IN_1") (pintype "input"))
    )
    (net (code "263") (name "Net-(X2-GRNC)") (class "Default")
      (node (ref "ER117") (pin "2") (pinfunction "2_2") (pintype "passive"))
      (node (ref "X2") (pin "10") (pinfunction "GRNC_10") (pintype "passive"))
    )
    (net (code "264") (name "Net-(X2-RCT)") (class "Default")
      (node (ref "EC40") (pin "1") (pinfunction "1_1") (pintype "passive"))
      (node (ref "ER122") (pin "2") (pinfunction "2_2") (pintype "passive"))
      (node (ref "X2") (pin "4") (pinfunction "TCT_4") (pintype "passive"))
      (node (ref "X2") (pin "5") (pinfunction "RCT_5") (pintype "passive"))
    )
    (net (code "265") (name "Net-(X2-YELC)") (class "Default")
      (node (ref "ER115") (pin "2") (pinfunction "2_2") (pintype "passive"))
      (node (ref "X2") (pin "11") (pinfunction "YELC_11") (pintype "passive"))
    )
    (net (code "266") (name "Net-(X10A-SK)") (class "Default")
      (node (ref "J11") (pin "1") (pinfunction "1_1") (pintype "bidirectional"))
      (node (ref "J12") (pin "1") (pinfunction "1_1") (pintype "bidirectional"))
      (node (ref "R181") (pin "1") (pinfunction "1_1") (pintype "passive"))
      (node (ref "R214") (pin "1") (pinfunction "1_1") (pintype "passive"))
      (node (ref "X10") (pin "1") (pinfunction "SK_1") (pintype "passive"))
    )
    (net (code "267") (name "Net-(X10C-SK)") (class "Default")
      (node (ref "J21") (pin "1") (pinfunction "1_1") (pintype "bidirectional"))
      (node (ref "J22") (pin "1") (pinfunction "1_1") (pintype "bidirectional"))
      (node (ref "R182") (pin "1") (pinfunction "1_1") (pintype "passive"))
      (node (ref "R224") (pin "1") (pinfunction "1_1") (pintype "passive"))
      (node (ref "X10") (pin "3") (pinfunction "SK_3") (pintype "passive"))
    )
    (net (code "268") (name "Net-(X11A-SK)") (class "Default")
      (node (ref "J31") (pin "1") (pinfunction "1_1") (pintype "bidirectional"))
      (node (ref "J32") (pin "1") (pinfunction "1_1") (pintype "bidirectional"))
      (node (ref "R183") (pin "1") (pinfunction "1_1") (pintype "passive"))
      (node (ref "R234") (pin "1") (pinfunction "1_1") (pintype "passive"))
      (node (ref "X11") (pin "1") (pinfunction "SK_1") (pintype "passive"))
    )
    (net (code "269") (name "Net-(X11C-SK)") (class "Default")
      (node (ref "J41") (pin "1") (pinfunction "1_1") (pintype "bidirectional"))
      (node (ref "J42") (pin "1") (pinfunction "1_1") (pintype "bidirectional"))
      (node (ref "R184") (pin "1") (pinfunction "1_1") (pintype "passive"))
      (node (ref "R244") (pin "1") (pinfunction "1_1") (pintype "passive"))
      (node (ref "X11") (pin "3") (pinfunction "SK_3") (pintype "passive"))
    )
    (net (code "270") (name "Net-(X12A-SK)") (class "Default")
      (node (ref "J51") (pin "1") (pinfunction "1_1") (pintype "bidirectional"))
      (node (ref "J52") (pin "1") (pinfunction "1_1") (pintype "bidirectional"))
      (node (ref "R185") (pin "1") (pinfunction "1_1") (pintype "passive"))
      (node (ref "R254") (pin "1") (pinfunction "1_1") (pintype "passive"))
      (node (ref "X12") (pin "1") (pinfunction "SK_1") (pintype "passive"))
    )
    (net (code "271") (name "Net-(X12C-SK)") (class "Default")
      (node (ref "J61") (pin "1") (pinfunction "1_1") (pintype "bidirectional"))
      (node (ref "J62") (pin "1") (pinfunction "1_1") (pintype "bidirectional"))
      (node (ref "R186") (pin "1") (pinfunction "1_1") (pintype "passive"))
      (node (ref "R264") (pin "1") (pinfunction "1_1") (pintype "passive"))
      (node (ref "X12") (pin "3") (pinfunction "SK_3") (pintype "passive"))
    )
    (net (code "272") (name "Net-(X41B-1)") (class "Default")
      (node (ref "F402") (pin "1") (pinfunction "1_1") (pintype "passive"))
      (node (ref "GDT1") (pin "1") (pinfunction "1_1") (pintype "passive"))
      (node (ref "X41") (pin "2") (pinfunction "1_2") (pintype "passive"))
    )
    (net (code "273") (name "Net-(Y7-1)") (class "Default")
      (node (ref "EC41") (pin "1") (pinfunction "1_1") (pintype "passive"))
      (node (ref "ER127") (pin "2") (pinfunction "2_2") (pintype "passive"))
      (node (ref "Y7") (pin "P$1") (pinfunction "1_P$1") (pintype "passive"))
    )
    (net (code "274") (name "Net-(Y7-2)") (class "Default")
      (node (ref "EC42") (pin "1") (pinfunction "1_1") (pintype "passive"))
      (node (ref "ER125") (pin "2") (pinfunction "2_2") (pintype "passive"))
      (node (ref "ER126") (pin "2") (pinfunction "2_2") (pintype "passive"))
      (node (ref "Y7") (pin "P$2") (pinfunction "2_P$2") (pintype "passive"))
    )
    (net (code "275") (name "SYS_ADC_1P8V") (class "Default")
      (node (ref "C10") (pin "1") (pinfunction "1_1") (pintype "passive"))
      (node (ref "IC14") (pin "3") (pinfunction "+IN_3") (pintype "input"))
      (node (ref "IC14") (pin "5") (pinfunction "+IN_5") (pintype "input"))
      (node (ref "R33") (pin "2") (pinfunction "2_2") (pintype "passive"))
      (node (ref "U1") (pin "Y12") (pinfunction "SYS_ADC_1P8V_Y12") (pintype "bidirectional"))
    )
    (net (code "276") (name "SYS_RTC_1P8V") (class "Default")
      (node (ref "Q1") (pin "C") (pinfunction "C_C") (pintype "passive"))
      (node (ref "R15") (pin "1") (pinfunction "1_1") (pintype "passive"))
      (node (ref "TP14") (pin "TP") (pinfunction "TP_TP") (pintype "input"))
      (node (ref "U1") (pin "K13") (pinfunction "SYS_RTC_1P8V_K13") (pintype "power_in"))
      (node (ref "U1") (pin "K14") (pinfunction "SYS_RTC_1P8V_K14") (pintype "power_in"))
      (node (ref "U1") (pin "L13") (pinfunction "SYS_RTC_1P8V_L13") (pintype "power_in"))
      (node (ref "U1") (pin "L14") (pinfunction "SYS_RTC_1P8V_L14") (pintype "power_in"))
      (node (ref "U1") (pin "M13") (pinfunction "VDDS_RTC_M13") (pintype "bidirectional"))
      (node (ref "U1") (pin "M14") (pinfunction "VDDS_M14") (pintype "bidirectional"))
      (node (ref "U5") (pin "3") (pinfunction "ANODE_3") (pintype "bidirectional"))
    )
    (net (code "277") (name "SYS_VDD1_3P3V") (class "Default")
      (node (ref "C104") (pin "1") (pinfunction "1_1") (pintype "passive"))
      (node (ref "C15") (pin "1") (pinfunction "1_1") (pintype "passive"))
      (node (ref "C21") (pin "1") (pinfunction "1_1") (pintype "passive"))
      (node (ref "C22") (pin "1") (pinfunction "1_1") (pintype "passive"))
      (node (ref "C301") (pin "1") (pinfunction "1_1") (pintype "passive"))
      (node (ref "C401") (pin "1") (pinfunction "1_1") (pintype "passive"))
      (node (ref "C404") (pin "1") (pinfunction "1_1") (pintype "passive"))
      (node (ref "C6") (pin "2") (pinfunction "2_2") (pintype "passive"))
      (node (ref "C79") (pin "1") (pinfunction "1_1") (pintype "passive"))
      (node (ref "C801") (pin "1") (pinfunction "1_1") (pintype "passive"))
      (node (ref "C85") (pin "1") (pinfunction "1_1") (pintype "passive"))
      (node (ref "C87") (pin "1") (pinfunction "1_1") (pintype "passive"))
      (node (ref "C88") (pin "1") (pinfunction "1_1") (pintype "passive"))
      (node (ref "EC34") (pin "1") (pinfunction "1_1") (pintype "passive"))
      (node (ref "ER100") (pin "1") (pinfunction "1_1") (pintype "passive"))
      (node (ref "ER105") (pin "1") (pinfunction "1_1") (pintype "passive"))
      (node (ref "ER98") (pin "1") (pinfunction "1_1") (pintype "passive"))
      (node (ref "ER99") (pin "1") (pinfunction "1_1") (pintype "passive"))
      (node (ref "FB7") (pin "1") (pinfunction "1_1") (pintype "passive"))
      (node (ref "IC14") (pin "8") (pinfunction "V+_8") (pintype "power_in"))
      (node (ref "R12") (pin "2") (pinfunction "2_2") (pintype "passive"))
      (node (ref "R13") (pin "2") (pinfunction "2_2") (pintype "passive"))
      (node (ref "R163") (pin "2") (pinfunction "2_2") (pintype "passive"))
      (node (ref "R164") (pin "1") (pinfunction "1_1") (pintype "passive"))
      (node (ref "R169") (pin "2") (pinfunction "2_2") (pintype "passive"))
      (node (ref "R170") (pin "2") (pinfunction "2_2") (pintype "passive"))
      (node (ref "R22") (pin "2") (pinfunction "2_2") (pintype "passive"))
      (node (ref "R303") (pin "2") (pinfunction "2_2") (pintype "passive"))
      (node (ref "R40") (pin "2") (pinfunction "2_2") (pintype "passive"))
      (node (ref "R41") (pin "2") (pinfunction "2_2") (pintype "passive"))
      (node (ref "R70") (pin "2") (pinfunction "2_2") (pintype "passive"))
      (node (ref "R71") (pin "2") (pinfunction "2_2") (pintype "passive"))
      (node (ref "R72") (pin "2") (pinfunction "2_2") (pintype "passive"))
      (node (ref "R73") (pin "2") (pinfunction "2_2") (pintype "passive"))
      (node (ref "R74") (pin "2") (pinfunction "2_2") (pintype "passive"))
      (node (ref "R75") (pin "2") (pinfunction "2_2") (pintype "passive"))
      (node (ref "R76") (pin "2") (pinfunction "2_2") (pintype "passive"))
      (node (ref "R77") (pin "2") (pinfunction "2_2") (pintype "passive"))
      (node (ref "R78") (pin "2") (pinfunction "2_2") (pintype "passive"))
      (node (ref "R79") (pin "2") (pinfunction "2_2") (pintype "passive"))
      (node (ref "R80") (pin "2") (pinfunction "2_2") (pintype "passive"))
      (node (ref "R81") (pin "2") (pinfunction "2_2") (pintype "passive"))
      (node (ref "R82") (pin "2") (pinfunction "2_2") (pintype "passive"))
      (node (ref "R83") (pin "2") (pinfunction "2_2") (pintype "passive"))
      (node (ref "R84") (pin "2") (pinfunction "2_2") (pintype "passive"))
      (node (ref "R85") (pin "2") (pinfunction "2_2") (pintype "passive"))
      (node (ref "R86") (pin "2") (pinfunction "2_2") (pintype "passive"))
      (node (ref "R87") (pin "2") (pinfunction "2_2") (pintype "passive"))
      (node (ref "R88") (pin "2") (pinfunction "2_2") (pintype "passive"))
      (node (ref "R89") (pin "2") (pinfunction "2_2") (pintype "passive"))
      (node (ref "R90") (pin "2") (pinfunction "2_2") (pintype "passive"))
      (node (ref "R91") (pin "2") (pinfunction "2_2") (pintype "passive"))
      (node (ref "R92") (pin "2") (pinfunction "2_2") (pintype "passive"))
      (node (ref "RTC1") (pin "2") (pinfunction "VCC_2") (pintype "power_in"))
      (node (ref "S11") (pin "C") (pinfunction "C_C") (pintype "passive"))
      (node (ref "S12") (pin "C") (pinfunction "C_C") (pintype "passive"))
      (node (ref "S13") (pin "1") (pinfunction "1_1") (pintype "passive"))
      (node (ref "S13") (pin "2") (pinfunction "2_2") (pintype "passive"))
      (node (ref "S13") (pin "3") (pinfunction "3_3") (pintype "passive"))
      (node (ref "S13") (pin "4") (pinfunction "4_4") (pintype "passive"))
      (node (ref "T4") (pin "P$2") (pinfunction "2_P$2") (pintype "passive"))
      (node (ref "T4") (pin "P$3") (pinfunction "3_P$3") (pintype "passive"))
      (node (ref "TP12") (pin "TP") (pinfunction "TP_TP") (pintype "input"))
      (node (ref "U1") (pin "F8") (pinfunction "EMMC_VCC_F8") (pintype "bidirectional"))
      (node (ref "U1") (pin "F9") (pinfunction "EMMC_VCC_F9") (pintype "bidirectional"))
      (node (ref "U1") (pin "G8") (pinfunction "EMMC_VCC_G8") (pintype "bidirectional"))
      (node (ref "U1") (pin "G9") (pinfunction "EMMC_VCC_G9") (pintype "bidirectional"))
      (node (ref "U1") (pin "H14") (pinfunction "SYS_VDD1_3P3V_H14") (pintype "power_in"))
      (node (ref "U1") (pin "H15") (pinfunction "SYS_VDD1_3P3V_H15") (pintype "power_in"))
      (node (ref "U1") (pin "H7") (pinfunction "EMMC_VCCQ_H7") (pintype "bidirectional"))
      (node (ref "U1") (pin "H8") (pinfunction "EMMC_VCCQ_H8") (pintype "bidirectional"))
      (node (ref "U1") (pin "J14") (pinfunction "SYS_VDD1_3P3V_J14") (pintype "power_in"))
      (node (ref "U1") (pin "J15") (pinfunction "SYS_VDD1_3P3V_J15") (pintype "power_in"))
      (node (ref "U1") (pin "J7") (pinfunction "EMMC_VCCQ_J7") (pintype "bidirectional"))
      (node (ref "U1") (pin "J8") (pinfunction "EMMC_VCCQ_J8") (pintype "bidirectional"))
      (node (ref "U16") (pin "1") (pinfunction "VCC_1") (pintype "bidirectional"))
      (node (ref "U16") (pin "22") (pinfunction "VCC_22") (pintype "bidirectional"))
      (node (ref "U16") (pin "8") (pinfunction "VCC_8") (pintype "bidirectional"))
      (node (ref "U27") (pin "12") (pinfunction "VDDIO_12") (pintype "power_in"))
      (node (ref "U28") (pin "3") (pinfunction "VCC_3") (pintype "power_in"))
      (node (ref "U29") (pin "8") (pinfunction "VCC_8") (pintype "power_in"))
      (node (ref "U4") (pin "4") (pinfunction "VCC_4") (pintype "bidirectional"))
      (node (ref "U40") (pin "4") (pinfunction "VCC1_4") (pintype "power_in"))
      (node (ref "U6") (pin "7") (pinfunction "2OE_7") (pintype "input"))
      (node (ref "U6") (pin "8") (pinfunction "VCC_8") (pintype "power_in"))
      (node (ref "X4") (pin "5") (pinfunction "TVDD_5") (pintype "bidirectional"))
      (node (ref "X5") (pin "4") (pinfunction "VDD_4") (pintype "bidirectional"))
    )
    (net (code "278") (name "SYS_VDD2_3P3V") (class "Default")
      (node (ref "D1") (pin "1") (pinfunction "A_1") (pintype "passive"))
      (node (ref "TP13") (pin "TP") (pinfunction "TP_TP") (pintype "input"))
      (node (ref "U1") (pin "F12") (pinfunction "SYS_VDD2_3P3V_F12") (pintype "power_in"))
      (node (ref "U1") (pin "F13") (pinfunction "SYS_VDD2_3P3V_F13") (pintype "power_in"))
      (node (ref "U1") (pin "G12") (pinfunction "SYS_VDD2_3P3V_G12") (pintype "power_in"))
      (node (ref "U1") (pin "G13") (pinfunction "SYS_VDD2_3P3V_G13") (pintype "power_in"))
    )
    (net (code "279") (name "SYS_VDD3_3P3V") (class "Default")
      (node (ref "Q1") (pin "E") (pinfunction "E_E") (pintype "passive"))
      (node (ref "R20") (pin "2") (pinfunction "2_2") (pintype "passive"))
      (node (ref "R21") (pin "2") (pinfunction "2_2") (pintype "passive"))
      (node (ref "TP16") (pin "TP") (pinfunction "TP_TP") (pintype "input"))
      (node (ref "U1") (pin "K10") (pinfunction "SYS_VDD3_3P3V_K10") (pintype "power_in"))
      (node (ref "U1") (pin "K11") (pinfunction "SYS_VDD3_3P3V_K11") (pintype "power_in"))
      (node (ref "U1") (pin "L10") (pinfunction "SYS_VDD3_3P3V_L10") (pintype "power_in"))
      (node (ref "U1") (pin "L11") (pinfunction "SYS_VDD3_3P3V_L11") (pintype "power_in"))
      (node (ref "U1") (pin "L12") (pinfunction "SYS_VDD3_3P3V_L12") (pintype "power_in"))
      (node (ref "U1") (pin "L7") (pinfunction "SYS_VDD3_3P3V_L7") (pintype "power_in"))
      (node (ref "U1") (pin "L8") (pinfunction "SYS_VDD3_3P3V_L8") (pintype "power_in"))
      (node (ref "U1") (pin "L9") (pinfunction "SYS_VDD3_3P3V_L9") (pintype "power_in"))
      (node (ref "U1") (pin "M10") (pinfunction "VDDSHV2_M10") (pintype "power_in"))
      (node (ref "U1") (pin "M11") (pinfunction "VDDSHV1_M11") (pintype "power_in"))
      (node (ref "U1") (pin "M12") (pinfunction "VDDSHV6_M12") (pintype "power_in"))
      (node (ref "U1") (pin "M7") (pinfunction "VDDSHV4_M7") (pintype "power_in"))
      (node (ref "U1") (pin "M8") (pinfunction "VDDSHV5_M8") (pintype "power_in"))
      (node (ref "U1") (pin "M9") (pinfunction "VDDSHV3_M9") (pintype "power_in"))
    )
    (net (code "280") (name "SYS_VDD_1P8V") (class "Default")
      (node (ref "TP15") (pin "TP") (pinfunction "TP_TP") (pintype "input"))
      (node (ref "U1") (pin "N10") (pinfunction "SYS_VDD_1P8V_N10") (pintype "power_in"))
      (node (ref "U1") (pin "N11") (pinfunction "SYS_VDD_1P8V_N11") (pintype "power_in"))
      (node (ref "U1") (pin "N12") (pinfunction "SYS_VDD_1P8V_N12") (pintype "power_in"))
      (node (ref "U1") (pin "N13") (pinfunction "SYS_VDD_1P8V_N13") (pintype "power_in"))
      (node (ref "U1") (pin "N14") (pinfunction "SYS_VDD_1P8V_N14") (pintype "power_in"))
      (node (ref "U1") (pin "N7") (pinfunction "SYS_VDD_1P8V_N7") (pintype "power_in"))
      (node (ref "U1") (pin "N8") (pinfunction "SYS_VDD_1P8V_N8") (pintype "power_in"))
      (node (ref "U1") (pin "N9") (pinfunction "SYS_VDD_1P8V_N9") (pintype "power_in"))
      (node (ref "U1") (pin "P10") (pinfunction "SYS_VDD_1P8V_P10") (pintype "power_in"))
      (node (ref "U1") (pin "P11") (pinfunction "SYS_VDD_1P8V_P11") (pintype "power_in"))
    )
    (net (code "281") (name "SYS_VOUT") (class "Default")
      (node (ref "C4") (pin "1") (pinfunction "1_1") (pintype "passive"))
      (node (ref "TP11") (pin "TP") (pinfunction "TP_TP") (pintype "input"))
      (node (ref "U1") (pin "F14") (pinfunction "SYS_VOUT_F14") (pintype "power_in"))
      (node (ref "U1") (pin "F15") (pinfunction "SYS_VOUT_F15") (pintype "power_in"))
      (node (ref "U1") (pin "G14") (pinfunction "SYS_VOUT_G14") (pintype "power_in"))
      (node (ref "U1") (pin "G15") (pinfunction "SYS_VOUT_G15") (pintype "power_in"))
    )
    (net (code "282") (name "VDD_5V") (class "Default")
      (node (ref "C102") (pin "1") (pinfunction "1_1") (pintype "passive"))
      (node (ref "C11") (pin "+") (pinfunction "+_+") (pintype "passive"))
      (node (ref "L2") (pin "2") (pinfunction "2_2") (pintype "passive"))
      (node (ref "U1") (pin "C18") (pinfunction "VIN_AC_C18") (pintype "power_in"))
      (node (ref "U1") (pin "C19") (pinfunction "VIN_AC_C19") (pintype "power_in"))
      (node (ref "U1") (pin "C20") (pinfunction "VIN_AC_C20") (pintype "power_in"))
      (node (ref "VREG1") (pin "4") (pinfunction "FB_4") (pintype "input"))
    )
    (net (code "283") (name "VDD_BAT") (class "Default")
      (node (ref "TP5") (pin "P$1") (pinfunction "TP_P$1") (pintype "bidirectional"))
      (node (ref "U1") (pin "D18") (pinfunction "VIN_BAT_D18") (pintype "power_in"))
      (node (ref "U1") (pin "D19") (pinfunction "VIN_BAT_D19") (pintype "power_in"))
      (node (ref "U1") (pin "D20") (pinfunction "VIN_BAT_D20") (pintype "power_in"))
    )
    (net (code "284") (name "VDD_ETH_PHY") (class "Default")
      (node (ref "EC30") (pin "1") (pinfunction "1_1") (pintype "passive"))
      (node (ref "EC31") (pin "1") (pinfunction "1_1") (pintype "passive"))
      (node (ref "EC32") (pin "1") (pinfunction "1_1") (pintype "passive"))
      (node (ref "ER106") (pin "1") (pinfunction "1_1") (pintype "passive"))
      (node (ref "ER107") (pin "1") (pinfunction "1_1") (pintype "passive"))
      (node (ref "ER108") (pin "1") (pinfunction "1_1") (pintype "passive"))
      (node (ref "ER109") (pin "1") (pinfunction "1_1") (pintype "passive"))
      (node (ref "ER122") (pin "1") (pinfunction "1_1") (pintype "passive"))
      (node (ref "FB7") (pin "2") (pinfunction "2_2") (pintype "passive"))
      (node (ref "U27") (pin "1") (pinfunction "VDD2A_1") (pintype "power_in"))
      (node (ref "U27") (pin "27") (pinfunction "VDD1A_27") (pintype "power_in"))
    )
    (net (code "285") (name "VDD_USB_5V") (class "Default")
      (node (ref "C3") (pin "1") (pinfunction "1_1") (pintype "passive"))
      (node (ref "R10") (pin "2") (pinfunction "2_2") (pintype "passive"))
      (node (ref "U1") (pin "B18") (pinfunction "VIN_USB_B18") (pintype "power_in"))
      (node (ref "U1") (pin "B19") (pinfunction "VIN_USB_B19") (pintype "power_in"))
      (node (ref "U1") (pin "B20") (pinfunction "VIN_USB_B20") (pintype "power_in"))
      (node (ref "U1") (pin "K1") (pinfunction "USB0_VBUS_K1") (pintype "bidirectional"))
      (node (ref "U2") (pin "6") (pinfunction "VBUS_6") (pintype "passive"))
    )
    (net (code "286") (name "unconnected-(F401-Pad2)") (class "Default")
      (node (ref "F401") (pin "2") (pinfunction "2_2") (pintype "passive"))
    )
    (net (code "287") (name "unconnected-(F402-Pad2)") (class "Default")
      (node (ref "F402") (pin "2") (pinfunction "2_2") (pintype "passive"))
    )
    (net (code "288") (name "unconnected-(FUD1-PadP$1)") (class "Default")
      (node (ref "FUD1") (pin "P$1") (pinfunction "P$1_P$1") (pintype "no_connect"))
    )
    (net (code "289") (name "unconnected-(FUD2-PadP$1)") (class "Default")
      (node (ref "FUD2") (pin "P$1") (pinfunction "P$1_P$1") (pintype "no_connect"))
    )
    (net (code "290") (name "unconnected-(FUD3-PadP$1)") (class "Default")
      (node (ref "FUD3") (pin "P$1") (pinfunction "P$1_P$1") (pintype "no_connect"))
    )
    (net (code "291") (name "unconnected-(FUD4-PadP$1)") (class "Default")
      (node (ref "FUD4") (pin "P$1") (pinfunction "P$1_P$1") (pintype "no_connect"))
    )
    (net (code "292") (name "unconnected-(FUD5-PadP$1)") (class "Default")
      (node (ref "FUD5") (pin "P$1") (pinfunction "P$1_P$1") (pintype "no_connect"))
    )
    (net (code "293") (name "unconnected-(FUD6-PadP$1)") (class "Default")
      (node (ref "FUD6") (pin "P$1") (pinfunction "P$1_P$1") (pintype "no_connect"))
    )
    (net (code "294") (name "unconnected-(G1-+-Pad+@1)") (class "Default")
      (node (ref "G1") (pin "+@1") (pinfunction "+_+@1") (pintype "passive"))
    )
    (net (code "295") (name "unconnected-(IC2-I6-Pad6)") (class "Default")
      (node (ref "IC2") (pin "6") (pinfunction "I6_6") (pintype "input"))
    )
    (net (code "296") (name "unconnected-(IC2-I7-Pad7)") (class "Default")
      (node (ref "IC2") (pin "7") (pinfunction "I7_7") (pintype "input"))
    )
    (net (code "297") (name "unconnected-(IC2-O6-Pad11)") (class "Default")
      (node (ref "IC2") (pin "11") (pinfunction "O6_11") (pintype "open_collector"))
    )
    (net (code "298") (name "unconnected-(IC2-O7-Pad10)") (class "Default")
      (node (ref "IC2") (pin "10") (pinfunction "O7_10") (pintype "open_collector"))
    )
    (net (code "299") (name "unconnected-(IC4A-~{QH}-Pad7)") (class "Default")
      (node (ref "IC4") (pin "7") (pinfunction "~{QH}_7") (pintype "output"))
    )
    (net (code "300") (name "unconnected-(IC5A-~{QH}-Pad7)") (class "Default")
      (node (ref "IC5") (pin "7") (pinfunction "~{QH}_7") (pintype "output"))
    )
    (net (code "301") (name "unconnected-(K1B-O-PadNC)") (class "Default")
      (node (ref "K1") (pin "NC") (pinfunction "O_NC") (pintype "passive"))
    )
    (net (code "302") (name "unconnected-(K2B-O-PadNC)") (class "Default")
      (node (ref "K2") (pin "NC") (pinfunction "O_NC") (pintype "passive"))
    )
    (net (code "303") (name "unconnected-(K3B-O-PadNC)") (class "Default")
      (node (ref "K3") (pin "NC") (pinfunction "O_NC") (pintype "passive"))
    )
    (net (code "304") (name "unconnected-(K4B-O-PadNC)") (class "Default")
      (node (ref "K4") (pin "NC") (pinfunction "O_NC") (pintype "passive"))
    )
    (net (code "305") (name "unconnected-(K5B-O-PadNC)") (class "Default")
      (node (ref "K5") (pin "NC") (pinfunction "O_NC") (pintype "passive"))
    )
    (net (code "306") (name "unconnected-(RTC1-SQW-Pad3)") (class "Default")
      (node (ref "RTC1") (pin "3") (pinfunction "SQW_3") (pintype "output"))
    )
    (net (code "307") (name "unconnected-(U1A-VDDS_RTC-PadU14)") (class "Default")
      (node (ref "U1") (pin "U14") (pinfunction "VDDS_RTC_U14") (pintype "bidirectional"))
    )
    (net (code "308") (name "unconnected-(U1B-USB0_CE-PadL3)") (class "Default")
      (node (ref "U1") (pin "L3") (pinfunction "USB0_CE_L3") (pintype "bidirectional"))
    )
    (net (code "309") (name "unconnected-(U1B-USB1_CE-PadJ3)") (class "Default")
      (node (ref "U1") (pin "J3") (pinfunction "USB1_CE_J3") (pintype "bidirectional"))
    )
    (net (code "310") (name "unconnected-(U1B-USB1_DM-PadH2)") (class "Default")
      (node (ref "U1") (pin "H2") (pinfunction "USB1_DM_H2") (pintype "bidirectional"))
    )
    (net (code "311") (name "unconnected-(U1B-USB1_DP-PadJ2)") (class "Default")
      (node (ref "U1") (pin "J2") (pinfunction "USB1_DP_J2") (pintype "bidirectional"))
    )
    (net (code "312") (name "unconnected-(U1B-USB1_DRVVBUS-PadH3)") (class "Default")
      (node (ref "U1") (pin "H3") (pinfunction "USB1_DRVVBUS_H3") (pintype "bidirectional"))
    )
    (net (code "313") (name "unconnected-(U1B-USB1_ID-PadJ1)") (class "Default")
      (node (ref "U1") (pin "J1") (pinfunction "USB1_ID_J1") (pintype "bidirectional"))
    )
    (net (code "314") (name "unconnected-(U1B-USB1_VBUS-PadH1)") (class "Default")
      (node (ref "U1") (pin "H1") (pinfunction "USB1_VBUS_H1") (pintype "bidirectional"))
    )
    (net (code "315") (name "unconnected-(U1C-EMMC_RSTN-PadA4)") (class "Default")
      (node (ref "U1") (pin "A4") (pinfunction "EMMC_RSTN_A4") (pintype "bidirectional"))
    )
    (net (code "316") (name "unconnected-(U1C-GPMC_A0-PadA13)") (class "Default")
      (node (ref "U1") (pin "A13") (pinfunction "GPMC_A0_A13") (pintype "bidirectional"))
    )
    (net (code "317") (name "unconnected-(U1C-GPMC_A4-PadB12)") (class "Default")
      (node (ref "U1") (pin "B12") (pinfunction "GPMC_A4_B12") (pintype "bidirectional"))
    )
    (net (code "318") (name "unconnected-(U1C-GPMC_A9-PadA10)") (class "Default")
      (node (ref "U1") (pin "A10") (pinfunction "GPMC_A9_A10") (pintype "bidirectional"))
    )
    (net (code "319") (name "unconnected-(U1C-GPMC_A10-PadB10)") (class "Default")
      (node (ref "U1") (pin "B10") (pinfunction "GPMC_A10_B10") (pintype "bidirectional"))
    )
    (net (code "320") (name "unconnected-(U1C-GPMC_A11-PadC10)") (class "Default")
      (node (ref "U1") (pin "C10") (pinfunction "GPMC_A11_C10") (pintype "bidirectional"))
    )
    (net (code "321") (name "unconnected-(U1C-GPMC_AD10-PadB16)") (class "Default")
      (node (ref "U1") (pin "B16") (pinfunction "GPMC_AD10_B16") (pintype "bidirectional"))
    )
    (net (code "322") (name "unconnected-(U1C-GPMC_AD11-PadA16)") (class "Default")
      (node (ref "U1") (pin "A16") (pinfunction "GPMC_AD11_A16") (pintype "bidirectional"))
    )
    (net (code "323") (name "unconnected-(U1C-GPMC_ADVN_ALE-PadL19)") (class "Default")
      (node (ref "U1") (pin "L19") (pinfunction "GPMC_ADVN_ALE_L19") (pintype "bidirectional"))
    )
    (net (code "324") (name "unconnected-(U1C-GPMC_BEN0_CLE-PadL20)") (class "Default")
      (node (ref "U1") (pin "L20") (pinfunction "GPMC_BEN0_CLE_L20") (pintype "bidirectional"))
    )
    (net (code "325") (name "unconnected-(U1C-GPMC_CLK-PadA14)") (class "Default")
      (node (ref "U1") (pin "A14") (pinfunction "GPMC_CLK_A14") (pintype "bidirectional"))
    )
    (net (code "326") (name "unconnected-(U1C-GPMC_OEN_REN-PadK19)") (class "Default")
      (node (ref "U1") (pin "K19") (pinfunction "GPMC_OEN_REN_K19") (pintype "bidirectional"))
    )
    (net (code "327") (name "unconnected-(U1C-GPMC_WEN-PadK18)") (class "Default")
      (node (ref "U1") (pin "K18") (pinfunction "GPMC_WEN_K18") (pintype "bidirectional"))
    )
    (net (code "328") (name "unconnected-(U1C-MCASP0_ACLKR-PadY15)") (class "Default")
      (node (ref "U1") (pin "Y15") (pinfunction "MCASP0_ACLKR_Y15") (pintype "bidirectional"))
    )
    (net (code "329") (name "unconnected-(U1D-RMII1_REF_CLK-PadM3)") (class "Default")
      (node (ref "U1") (pin "M3") (pinfunction "RMII1_REF_CLK_M3") (pintype "bidirectional"))
    )
    (net (code "330") (name "unconnected-(U1F-CAP_VDD_RTC-PadV13)") (class "Default")
      (node (ref "U1") (pin "V13") (pinfunction "CAP_VDD_RTC_V13") (pintype "bidirectional"))
    )
    (net (code "331") (name "unconnected-(U1G-NC-PadA2)") (class "Default")
      (node (ref "U1") (pin "A2") (pinfunction "NC_A2") (pintype "bidirectional"))
    )
    (net (code "332") (name "unconnected-(U1G-NC-PadA3)") (class "Default")
      (node (ref "U1") (pin "A3") (pinfunction "NC_A3") (pintype "bidirectional"))
    )
    (net (code "333") (name "unconnected-(U1G-NC-PadA5)") (class "Default")
      (node (ref "U1") (pin "A5") (pinfunction "NC_A5") (pintype "bidirectional"))
    )
    (net (code "334") (name "unconnected-(U1G-NC-PadA6)") (class "Default")
      (node (ref "U1") (pin "A6") (pinfunction "NC_A6") (pintype "bidirectional"))
    )
    (net (code "335") (name "unconnected-(U1G-NC-PadA7)") (class "Default")
      (node (ref "U1") (pin "A7") (pinfunction "NC_A7") (pintype "bidirectional"))
    )
    (net (code "336") (name "unconnected-(U1G-NC-PadA8)") (class "Default")
      (node (ref "U1") (pin "A8") (pinfunction "NC_A8") (pintype "bidirectional"))
    )
    (net (code "337") (name "unconnected-(U1G-NC-PadB1)") (class "Default")
      (node (ref "U1") (pin "B1") (pinfunction "NC_B1") (pintype "bidirectional"))
    )
    (net (code "338") (name "unconnected-(U1G-NC-PadB2)") (class "Default")
      (node (ref "U1") (pin "B2") (pinfunction "NC_B2") (pintype "bidirectional"))
    )
    (net (code "339") (name "unconnected-(U1G-NC-PadB3)") (class "Default")
      (node (ref "U1") (pin "B3") (pinfunction "NC_B3") (pintype "bidirectional"))
    )
    (net (code "340") (name "unconnected-(U1G-NC-PadB4)") (class "Default")
      (node (ref "U1") (pin "B4") (pinfunction "NC_B4") (pintype "bidirectional"))
    )
    (net (code "341") (name "unconnected-(U1G-NC-PadB5)") (class "Default")
      (node (ref "U1") (pin "B5") (pinfunction "NC_B5") (pintype "bidirectional"))
    )
    (net (code "342") (name "unconnected-(U1G-NC-PadB6)") (class "Default")
      (node (ref "U1") (pin "B6") (pinfunction "NC_B6") (pintype "bidirectional"))
    )
    (net (code "343") (name "unconnected-(U1G-NC-PadB7)") (class "Default")
      (node (ref "U1") (pin "B7") (pinfunction "NC_B7") (pintype "bidirectional"))
    )
    (net (code "344") (name "unconnected-(U1G-NC-PadB8)") (class "Default")
      (node (ref "U1") (pin "B8") (pinfunction "NC_B8") (pintype "bidirectional"))
    )
    (net (code "345") (name "unconnected-(U1G-NC-PadC1)") (class "Default")
      (node (ref "U1") (pin "C1") (pinfunction "NC_C1") (pintype "bidirectional"))
    )
    (net (code "346") (name "unconnected-(U1G-NC-PadC2)") (class "Default")
      (node (ref "U1") (pin "C2") (pinfunction "NC_C2") (pintype "bidirectional"))
    )
    (net (code "347") (name "unconnected-(U1G-NC-PadC3)") (class "Default")
      (node (ref "U1") (pin "C3") (pinfunction "NC_C3") (pintype "bidirectional"))
    )
    (net (code "348") (name "unconnected-(U1G-NC-PadC4)") (class "Default")
      (node (ref "U1") (pin "C4") (pinfunction "NC_C4") (pintype "bidirectional"))
    )
    (net (code "349") (name "unconnected-(U1G-NC-PadC5)") (class "Default")
      (node (ref "U1") (pin "C5") (pinfunction "NC_C5") (pintype "bidirectional"))
    )
    (net (code "350") (name "unconnected-(U1G-NC-PadC6)") (class "Default")
      (node (ref "U1") (pin "C6") (pinfunction "NC_C6") (pintype "bidirectional"))
    )
    (net (code "351") (name "unconnected-(U1G-NC-PadC7)") (class "Default")
      (node (ref "U1") (pin "C7") (pinfunction "NC_C7") (pintype "bidirectional"))
    )
    (net (code "352") (name "unconnected-(U1G-NC-PadC8)") (class "Default")
      (node (ref "U1") (pin "C8") (pinfunction "NC_C8") (pintype "bidirectional"))
    )
    (net (code "353") (name "unconnected-(U1G-NC-PadD1)") (class "Default")
      (node (ref "U1") (pin "D1") (pinfunction "NC_D1") (pintype "bidirectional"))
    )
    (net (code "354") (name "unconnected-(U1G-NC-PadD2)") (class "Default")
      (node (ref "U1") (pin "D2") (pinfunction "NC_D2") (pintype "bidirectional"))
    )
    (net (code "355") (name "unconnected-(U1G-NC-PadD3)") (class "Default")
      (node (ref "U1") (pin "D3") (pinfunction "NC_D3") (pintype "bidirectional"))
    )
    (net (code "356") (name "unconnected-(U1G-NC-PadD6)") (class "Default")
      (node (ref "U1") (pin "D6") (pinfunction "NC_D6") (pintype "bidirectional"))
    )
    (net (code "357") (name "unconnected-(U1G-NC-PadD7)") (class "Default")
      (node (ref "U1") (pin "D7") (pinfunction "NC_D7") (pintype "bidirectional"))
    )
    (net (code "358") (name "unconnected-(U1G-NC-PadD8)") (class "Default")
      (node (ref "U1") (pin "D8") (pinfunction "NC_D8") (pintype "bidirectional"))
    )
    (net (code "359") (name "unconnected-(U1G-NC-PadE1)") (class "Default")
      (node (ref "U1") (pin "E1") (pinfunction "NC_E1") (pintype "bidirectional"))
    )
    (net (code "360") (name "unconnected-(U1G-NC-PadE2)") (class "Default")
      (node (ref "U1") (pin "E2") (pinfunction "NC_E2") (pintype "bidirectional"))
    )
    (net (code "361") (name "unconnected-(U1G-NC-PadE3)") (class "Default")
      (node (ref "U1") (pin "E3") (pinfunction "NC_E3") (pintype "bidirectional"))
    )
    (net (code "362") (name "unconnected-(U1G-NC-PadE18)") (class "Default")
      (node (ref "U1") (pin "E18") (pinfunction "NC_E18") (pintype "bidirectional"))
    )
    (net (code "363") (name "unconnected-(U1G-NC-PadF1)") (class "Default")
      (node (ref "U1") (pin "F1") (pinfunction "NC_F1") (pintype "bidirectional"))
    )
    (net (code "364") (name "unconnected-(U1G-NC-PadF2)") (class "Default")
      (node (ref "U1") (pin "F2") (pinfunction "NC_F2") (pintype "bidirectional"))
    )
    (net (code "365") (name "unconnected-(U1G-NC-PadF3)") (class "Default")
      (node (ref "U1") (pin "F3") (pinfunction "NC_F3") (pintype "bidirectional"))
    )
    (net (code "366") (name "unconnected-(U1G-NC-PadF4)") (class "Default")
      (node (ref "U1") (pin "F4") (pinfunction "NC_F4") (pintype "bidirectional"))
    )
    (net (code "367") (name "unconnected-(U1G-NC-PadF6)") (class "Default")
      (node (ref "U1") (pin "F6") (pinfunction "NC_F6") (pintype "bidirectional"))
    )
    (net (code "368") (name "unconnected-(U1G-NC-PadF7)") (class "Default")
      (node (ref "U1") (pin "F7") (pinfunction "NC_F7") (pintype "bidirectional"))
    )
    (net (code "369") (name "unconnected-(U1G-NC-PadF20)") (class "Default")
      (node (ref "U1") (pin "F20") (pinfunction "NC_F20") (pintype "bidirectional"))
    )
    (net (code "370") (name "unconnected-(U1G-NC-PadG1)") (class "Default")
      (node (ref "U1") (pin "G1") (pinfunction "NC_G1") (pintype "bidirectional"))
    )
    (net (code "371") (name "unconnected-(U1G-NC-PadG2)") (class "Default")
      (node (ref "U1") (pin "G2") (pinfunction "NC_G2") (pintype "bidirectional"))
    )
    (net (code "372") (name "unconnected-(U1G-NC-PadG3)") (class "Default")
      (node (ref "U1") (pin "G3") (pinfunction "NC_G3") (pintype "bidirectional"))
    )
    (net (code "373") (name "unconnected-(U1G-NC-PadG4)") (class "Default")
      (node (ref "U1") (pin "G4") (pinfunction "NC_G4") (pintype "bidirectional"))
    )
    (net (code "374") (name "unconnected-(U1G-NC-PadG6)") (class "Default")
      (node (ref "U1") (pin "G6") (pinfunction "NC_G6") (pintype "bidirectional"))
    )
    (net (code "375") (name "unconnected-(U1G-NC-PadG7)") (class "Default")
      (node (ref "U1") (pin "G7") (pinfunction "NC_G7") (pintype "bidirectional"))
    )
    (net (code "376") (name "unconnected-(U1G-NC-PadG10)") (class "Default")
      (node (ref "U1") (pin "G10") (pinfunction "NC_G10") (pintype "bidirectional"))
    )
    (net (code "377") (name "unconnected-(U1G-NC-PadG11)") (class "Default")
      (node (ref "U1") (pin "G11") (pinfunction "NC_G11") (pintype "bidirectional"))
    )
    (net (code "378") (name "unconnected-(U1G-NC-PadG18)") (class "Default")
      (node (ref "U1") (pin "G18") (pinfunction "NC_G18") (pintype "bidirectional"))
    )
    (net (code "379") (name "unconnected-(U1G-NC-PadG19)") (class "Default")
      (node (ref "U1") (pin "G19") (pinfunction "NC_G19") (pintype "bidirectional"))
    )
    (net (code "380") (name "unconnected-(U1G-NC-PadG20)") (class "Default")
      (node (ref "U1") (pin "G20") (pinfunction "NC_G20") (pintype "bidirectional"))
    )
    (net (code "381") (name "unconnected-(U1G-NC-PadH4)") (class "Default")
      (node (ref "U1") (pin "H4") (pinfunction "NC_H4") (pintype "bidirectional"))
    )
    (net (code "382") (name "unconnected-(U1G-NC-PadH6)") (class "Default")
      (node (ref "U1") (pin "H6") (pinfunction "NC_H6") (pintype "bidirectional"))
    )
    (net (code "383") (name "unconnected-(U1G-NC-PadH9)") (class "Default")
      (node (ref "U1") (pin "H9") (pinfunction "NC_H9") (pintype "bidirectional"))
    )
    (net (code "384") (name "unconnected-(U1G-NC-PadH10)") (class "Default")
      (node (ref "U1") (pin "H10") (pinfunction "NC_H10") (pintype "bidirectional"))
    )
    (net (code "385") (name "unconnected-(U1G-NC-PadH11)") (class "Default")
      (node (ref "U1") (pin "H11") (pinfunction "NC_H11") (pintype "bidirectional"))
    )
    (net (code "386") (name "unconnected-(U1G-NC-PadH12)") (class "Default")
      (node (ref "U1") (pin "H12") (pinfunction "NC_H12") (pintype "bidirectional"))
    )
    (net (code "387") (name "unconnected-(U1G-NC-PadH13)") (class "Default")
      (node (ref "U1") (pin "H13") (pinfunction "NC_H13") (pintype "bidirectional"))
    )
    (net (code "388") (name "unconnected-(U1G-NC-PadH18)") (class "Default")
      (node (ref "U1") (pin "H18") (pinfunction "NC_H18") (pintype "bidirectional"))
    )
    (net (code "389") (name "unconnected-(U1G-NC-PadH19)") (class "Default")
      (node (ref "U1") (pin "H19") (pinfunction "NC_H19") (pintype "bidirectional"))
    )
    (net (code "390") (name "unconnected-(U1G-NC-PadH20)") (class "Default")
      (node (ref "U1") (pin "H20") (pinfunction "NC_H20") (pintype "bidirectional"))
    )
    (net (code "391") (name "unconnected-(U1G-NC-PadJ4)") (class "Default")
      (node (ref "U1") (pin "J4") (pinfunction "NC_J4") (pintype "bidirectional"))
    )
    (net (code "392") (name "unconnected-(U1G-NC-PadJ6)") (class "Default")
      (node (ref "U1") (pin "J6") (pinfunction "NC_J6") (pintype "bidirectional"))
    )
    (net (code "393") (name "unconnected-(U1G-NC-PadJ18)") (class "Default")
      (node (ref "U1") (pin "J18") (pinfunction "NC_J18") (pintype "bidirectional"))
    )
    (net (code "394") (name "unconnected-(U1G-NC-PadJ19)") (class "Default")
      (node (ref "U1") (pin "J19") (pinfunction "NC_J19") (pintype "bidirectional"))
    )
    (net (code "395") (name "unconnected-(U1G-NC-PadJ20)") (class "Default")
      (node (ref "U1") (pin "J20") (pinfunction "NC_J20") (pintype "bidirectional"))
    )
    (net (code "396") (name "unconnected-(U1G-NC-PadK4)") (class "Default")
      (node (ref "U1") (pin "K4") (pinfunction "NC_K4") (pintype "bidirectional"))
    )
    (net (code "397") (name "unconnected-(U1G-NC-PadL4)") (class "Default")
      (node (ref "U1") (pin "L4") (pinfunction "NC_L4") (pintype "bidirectional"))
    )
    (net (code "398") (name "unconnected-(U1G-NC-PadL17)") (class "Default")
      (node (ref "U1") (pin "L17") (pinfunction "NC_L17") (pintype "bidirectional"))
    )
    (net (code "399") (name "unconnected-(U1G-NC-PadM4)") (class "Default")
      (node (ref "U1") (pin "M4") (pinfunction "NC_M4") (pintype "bidirectional"))
    )
    (net (code "400") (name "unconnected-(U1G-NC-PadM6)") (class "Default")
      (node (ref "U1") (pin "M6") (pinfunction "NC_M6") (pintype "bidirectional"))
    )
    (net (code "401") (name "unconnected-(U1G-NC-PadM17)") (class "Default")
      (node (ref "U1") (pin "M17") (pinfunction "NC_M17") (pintype "bidirectional"))
    )
    (net (code "402") (name "unconnected-(U1G-NC-PadN4)") (class "Default")
      (node (ref "U1") (pin "N4") (pinfunction "NC_N4") (pintype "bidirectional"))
    )
    (net (code "403") (name "unconnected-(U1G-NC-PadN17)") (class "Default")
      (node (ref "U1") (pin "N17") (pinfunction "NC_N17") (pintype "bidirectional"))
    )
    (net (code "404") (name "unconnected-(U1G-NC-PadP4)") (class "Default")
      (node (ref "U1") (pin "P4") (pinfunction "NC_P4") (pintype "bidirectional"))
    )
    (net (code "405") (name "unconnected-(U1G-NC-PadP17)") (class "Default")
      (node (ref "U1") (pin "P17") (pinfunction "NC_P17") (pintype "bidirectional"))
    )
    (net (code "406") (name "unconnected-(U1G-NC-PadR4)") (class "Default")
      (node (ref "U1") (pin "R4") (pinfunction "NC_R4") (pintype "bidirectional"))
    )
    (net (code "407") (name "unconnected-(U1G-NC-PadR6)") (class "Default")
      (node (ref "U1") (pin "R6") (pinfunction "NC_R6") (pintype "bidirectional"))
    )
    (net (code "408") (name "unconnected-(U1G-NC-PadR7)") (class "Default")
      (node (ref "U1") (pin "R7") (pinfunction "NC_R7") (pintype "bidirectional"))
    )
    (net (code "409") (name "unconnected-(U1G-NC-PadR8)") (class "Default")
      (node (ref "U1") (pin "R8") (pinfunction "NC_R8") (pintype "bidirectional"))
    )
    (net (code "410") (name "unconnected-(U1G-NC-PadR13)") (class "Default")
      (node (ref "U1") (pin "R13") (pinfunction "NC_R13") (pintype "bidirectional"))
    )
    (net (code "411") (name "unconnected-(U1G-NC-PadR14)") (class "Default")
      (node (ref "U1") (pin "R14") (pinfunction "NC_R14") (pintype "bidirectional"))
    )
    (net (code "412") (name "unconnected-(U1G-NC-PadR15)") (class "Default")
      (node (ref "U1") (pin "R15") (pinfunction "NC_R15") (pintype "bidirectional"))
    )
    (net (code "413") (name "unconnected-(U1G-NC-PadR17)") (class "Default")
      (node (ref "U1") (pin "R17") (pinfunction "NC_R17") (pintype "bidirectional"))
    )
    (net (code "414") (name "unconnected-(U1G-NC-PadU11)") (class "Default")
      (node (ref "U1") (pin "U11") (pinfunction "NC_U11") (pintype "bidirectional"))
    )
    (net (code "415") (name "unconnected-(U2-N.C.-Pad5)") (class "Default")
      (node (ref "U2") (pin "5") (pinfunction "N.C._5") (pintype "no_connect"))
    )
    (net (code "416") (name "unconnected-(U16-NC-Pad7)") (class "Default")
      (node (ref "U16") (pin "7") (pinfunction "NC_7") (pintype "bidirectional"))
    )
    (net (code "417") (name "unconnected-(U16-NC-Pad10)") (class "Default")
      (node (ref "U16") (pin "10") (pinfunction "NC_10") (pintype "bidirectional"))
    )
    (net (code "418") (name "unconnected-(U16-NC-Pad11)") (class "Default")
      (node (ref "U16") (pin "11") (pinfunction "NC_11") (pintype "bidirectional"))
    )
    (net (code "419") (name "unconnected-(U16-NC-Pad13)") (class "Default")
      (node (ref "U16") (pin "13") (pinfunction "NC_13") (pintype "bidirectional"))
    )
    (net (code "420") (name "unconnected-(U16-NC-Pad14)") (class "Default")
      (node (ref "U16") (pin "14") (pinfunction "NC_14") (pintype "bidirectional"))
    )
    (net (code "421") (name "unconnected-(U16-NC-Pad15)") (class "Default")
      (node (ref "U16") (pin "15") (pinfunction "NC_15") (pintype "bidirectional"))
    )
    (net (code "422") (name "unconnected-(U16-NC-Pad16)") (class "Default")
      (node (ref "U16") (pin "16") (pinfunction "NC_16") (pintype "bidirectional"))
    )
    (net (code "423") (name "unconnected-(U16-NC-Pad25)") (class "Default")
      (node (ref "U16") (pin "25") (pinfunction "NC_25") (pintype "bidirectional"))
    )
    (net (code "424") (name "unconnected-(U16-NC-Pad26)") (class "Default")
      (node (ref "U16") (pin "26") (pinfunction "NC_26") (pintype "bidirectional"))
    )
    (net (code "425") (name "unconnected-(U16-NC-Pad27)") (class "Default")
      (node (ref "U16") (pin "27") (pinfunction "NC_27") (pintype "bidirectional"))
    )
    (net (code "426") (name "unconnected-(U16-NC-Pad28)") (class "Default")
      (node (ref "U16") (pin "28") (pinfunction "NC_28") (pintype "bidirectional"))
    )
    (net (code "427") (name "unconnected-(U16-NC-Pad31)") (class "Default")
      (node (ref "U16") (pin "31") (pinfunction "NC_31") (pintype "bidirectional"))
    )
    (net (code "428") (name "unconnected-(U16-PAD-Pad33)") (class "Default")
      (node (ref "U16") (pin "33") (pinfunction "PAD_33") (pintype "bidirectional"))
    )
    (net (code "429") (name "unconnected-(U28-S-Pad8)") (class "Default")
      (node (ref "U28") (pin "8") (pinfunction "S_8") (pintype "input"))
    )
    (net (code "430") (name "unconnected-(U40-NC-Pad10)") (class "Default")
      (node (ref "U40") (pin "10") (pinfunction "NC_10") (pintype "passive"))
    )
    (net (code "431") (name "unconnected-(VREG4-BYPASS-Pad4)") (class "Default")
      (node (ref "VREG4") (pin "4") (pinfunction "BYPASS_4") (pintype "passive"))
    )
    (net (code "432") (name "unconnected-(X2-NC-Pad7)") (class "Default")
      (node (ref "X2") (pin "7") (pinfunction "NC_7") (pintype "passive"))
    )
    (net (code "433") (name "unconnected-(X4-NC-Pad6)") (class "Default")
      (node (ref "X4") (pin "6") (pinfunction "NC_6") (pintype "bidirectional"))
    )
    (net (code "434") (name "unconnected-(X6-Pad2)") (class "Default")
      (node (ref "X6") (pin "2") (pinfunction "2_2") (pintype "bidirectional"))
    )
    (net (code "435") (name "unconnected-(X6-Pad3)") (class "Default")
      (node (ref "X6") (pin "3") (pinfunction "3_3") (pintype "bidirectional"))
    )
    (net (code "436") (name "unconnected-(X6-Pad6)") (class "Default")
      (node (ref "X6") (pin "6") (pinfunction "6_6") (pintype "bidirectional"))
    )
  )
)
